# PDNode_Devboard_v0_0_1.net
KiCad netlist of a schematic drawn in EAGLE
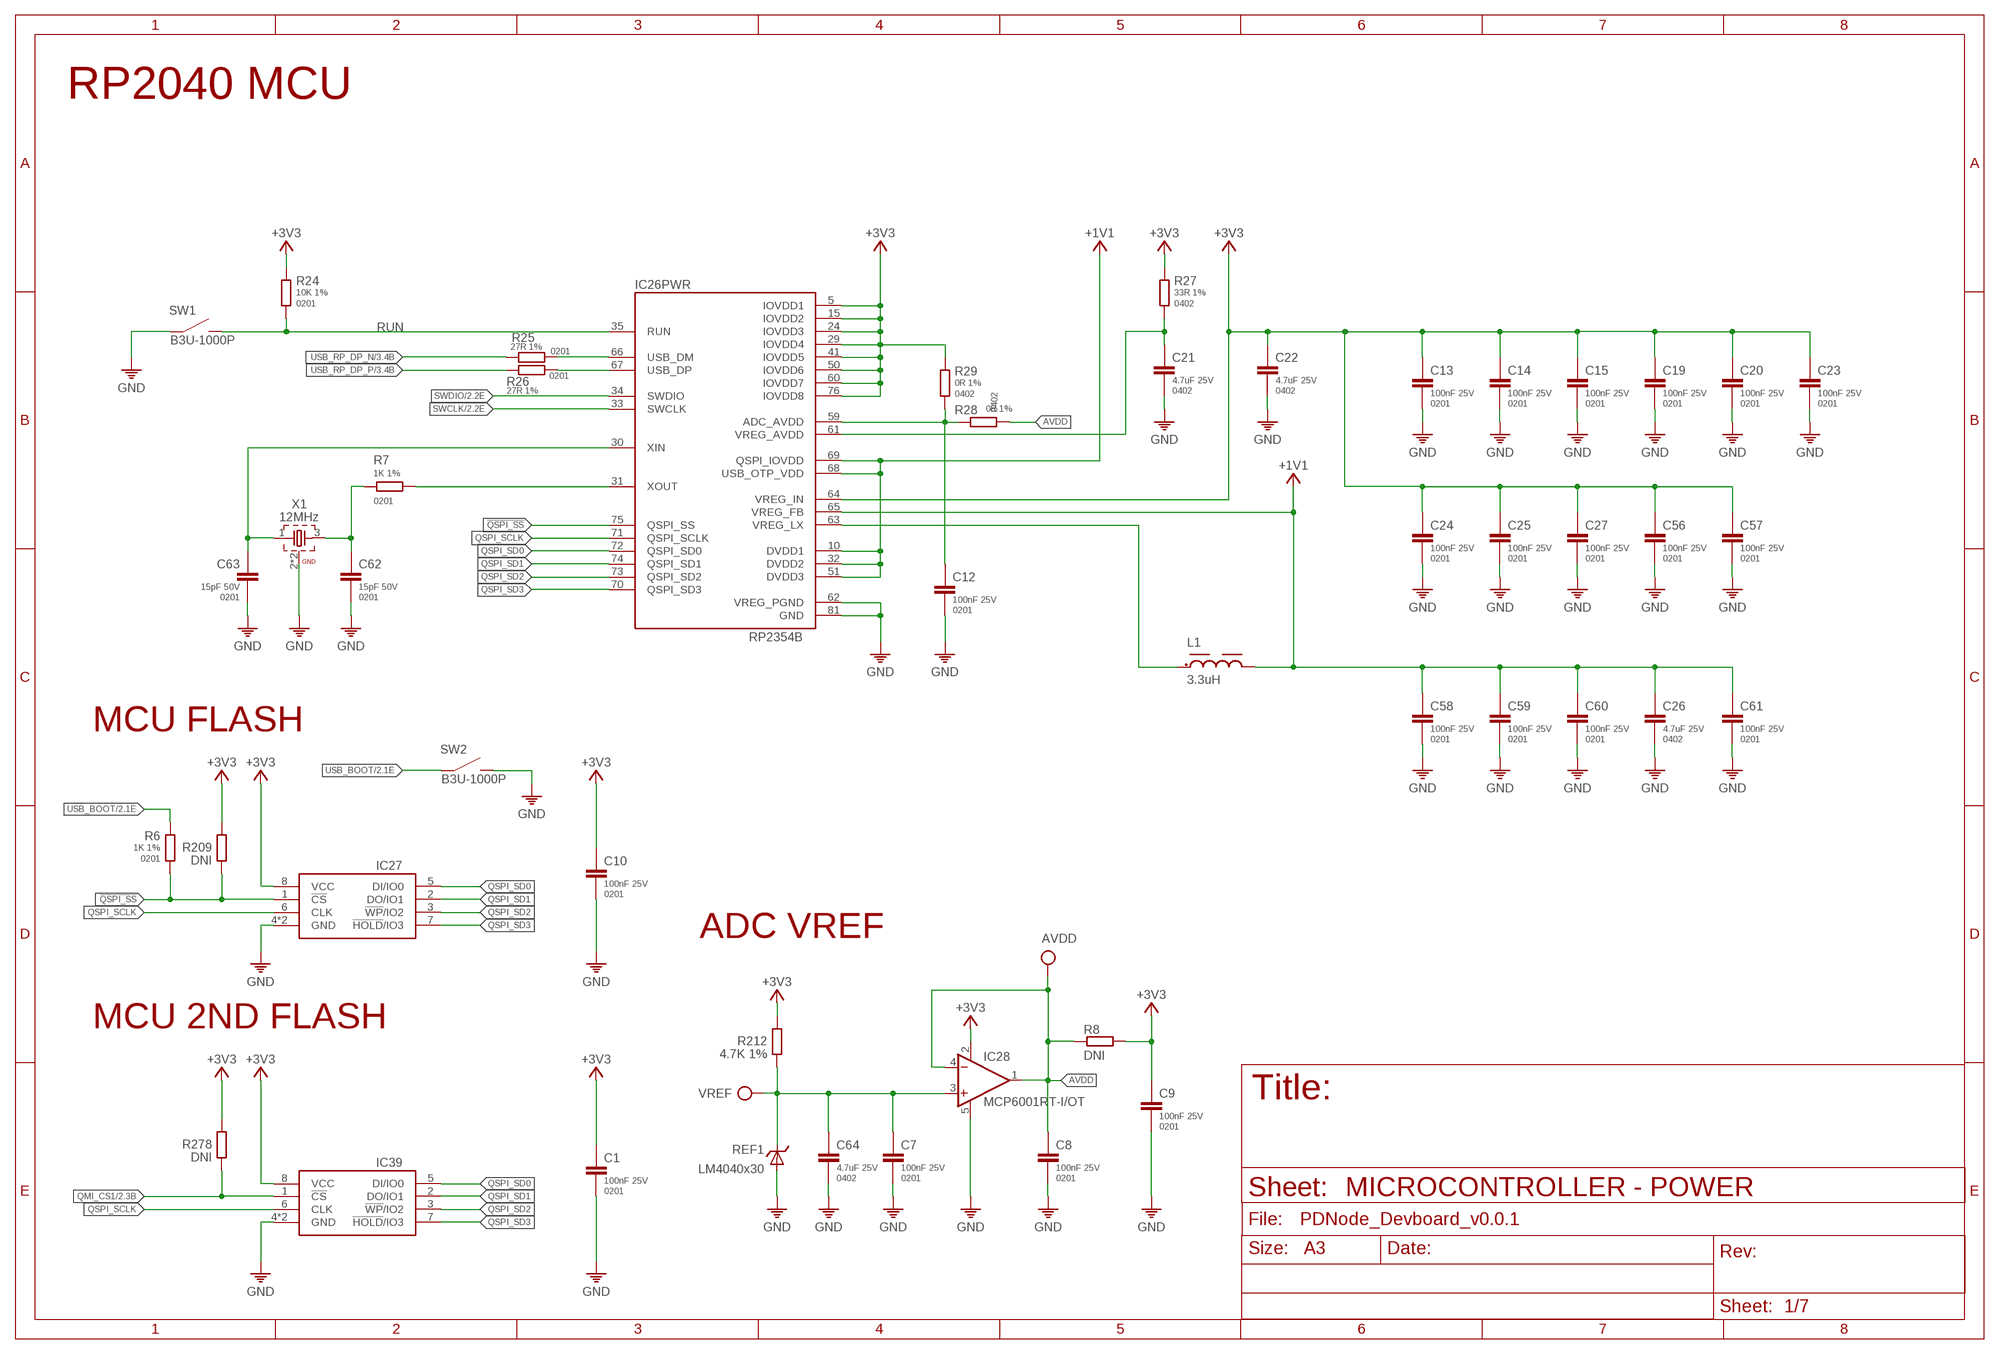
[diagram p0: schematic, sheet 1]
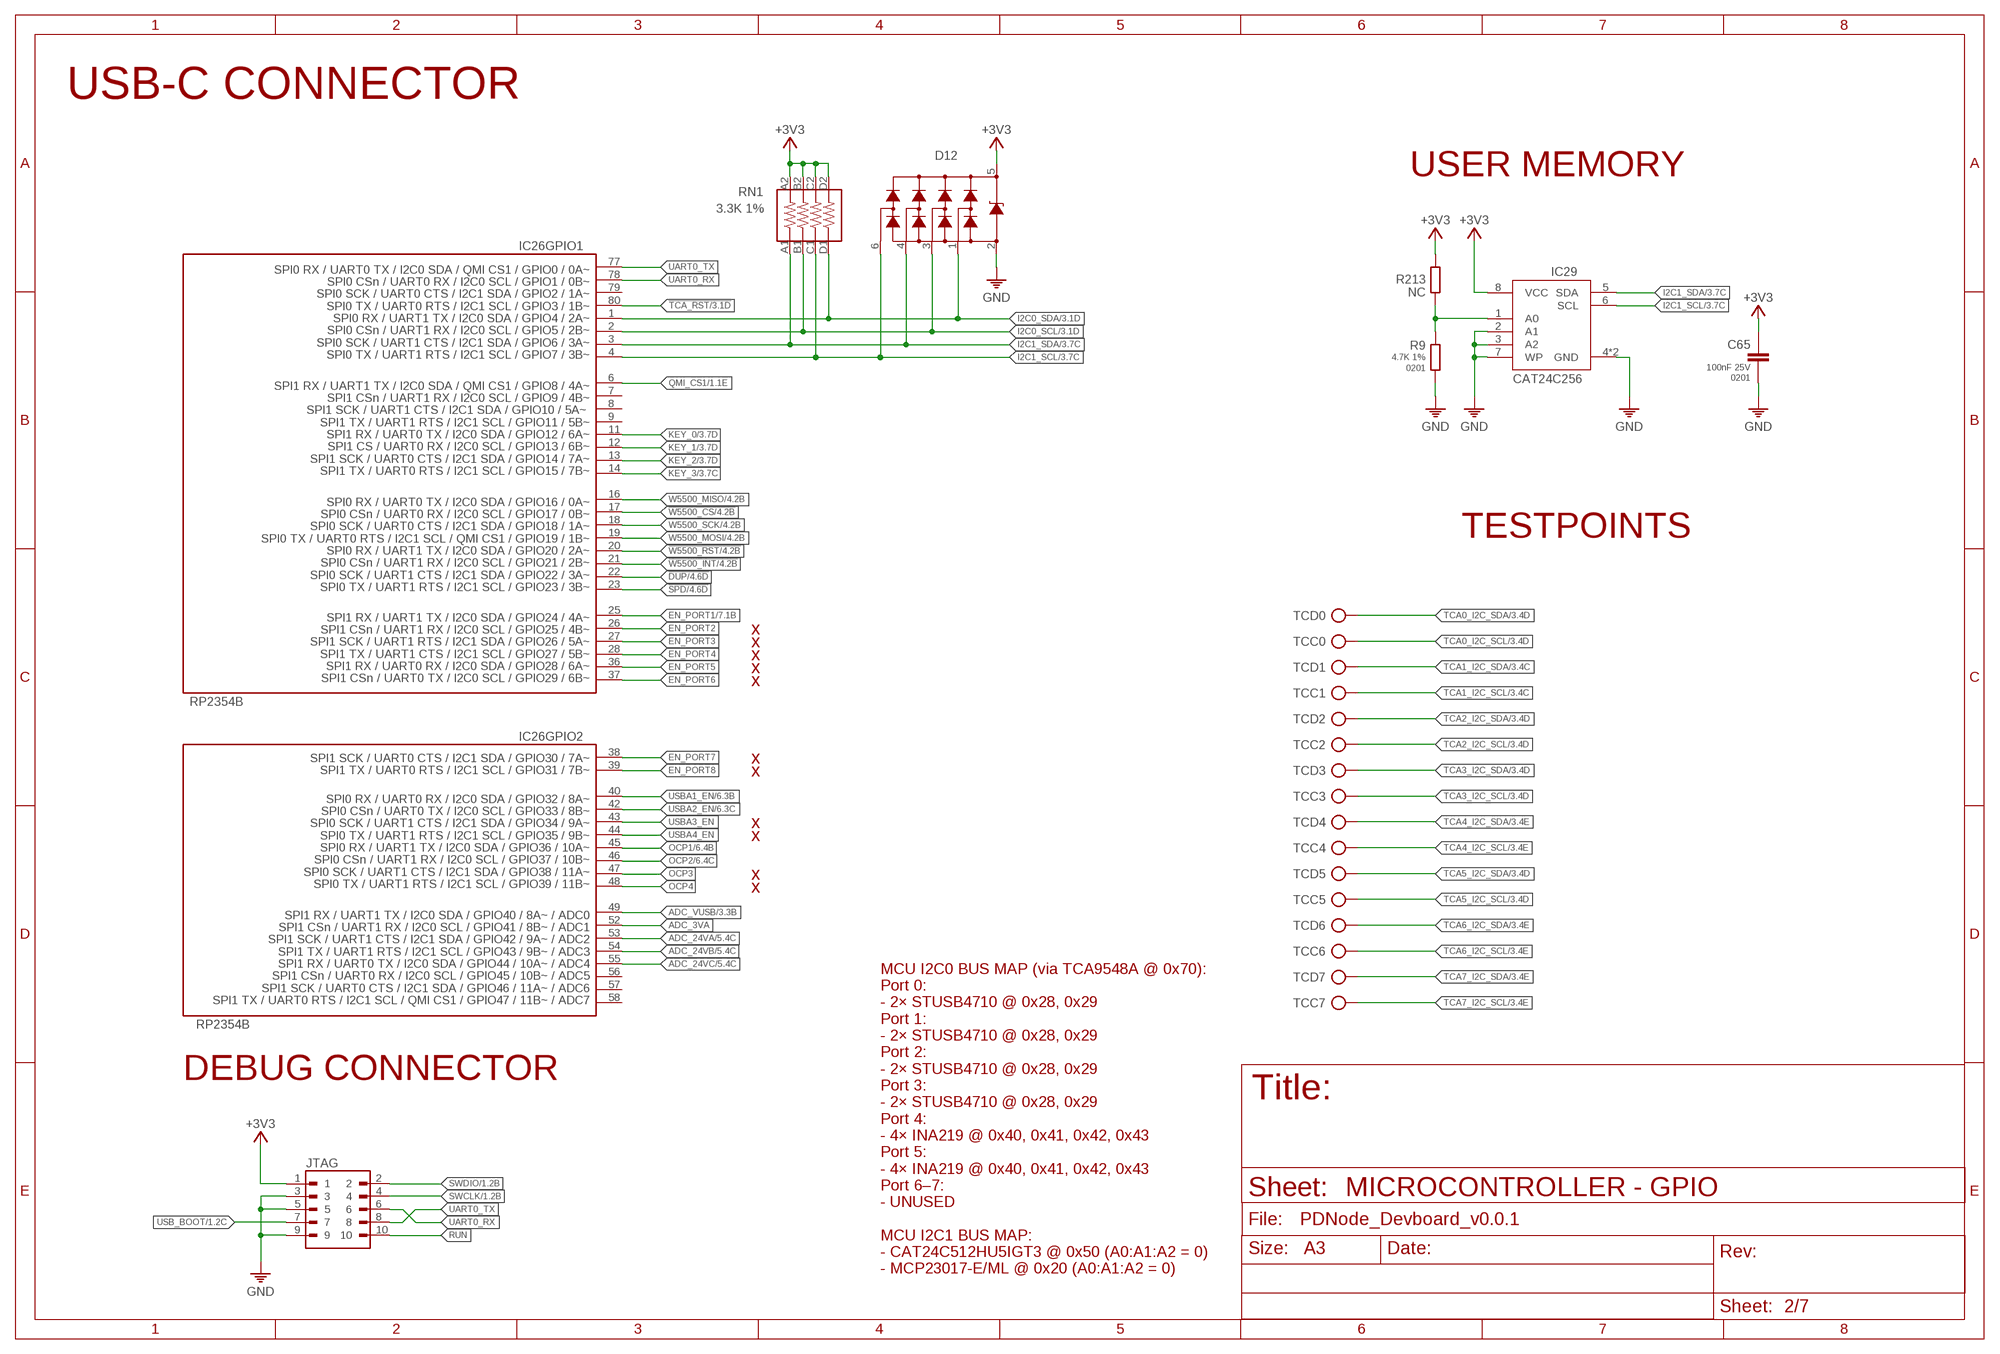
[diagram p1: schematic, sheet 2]
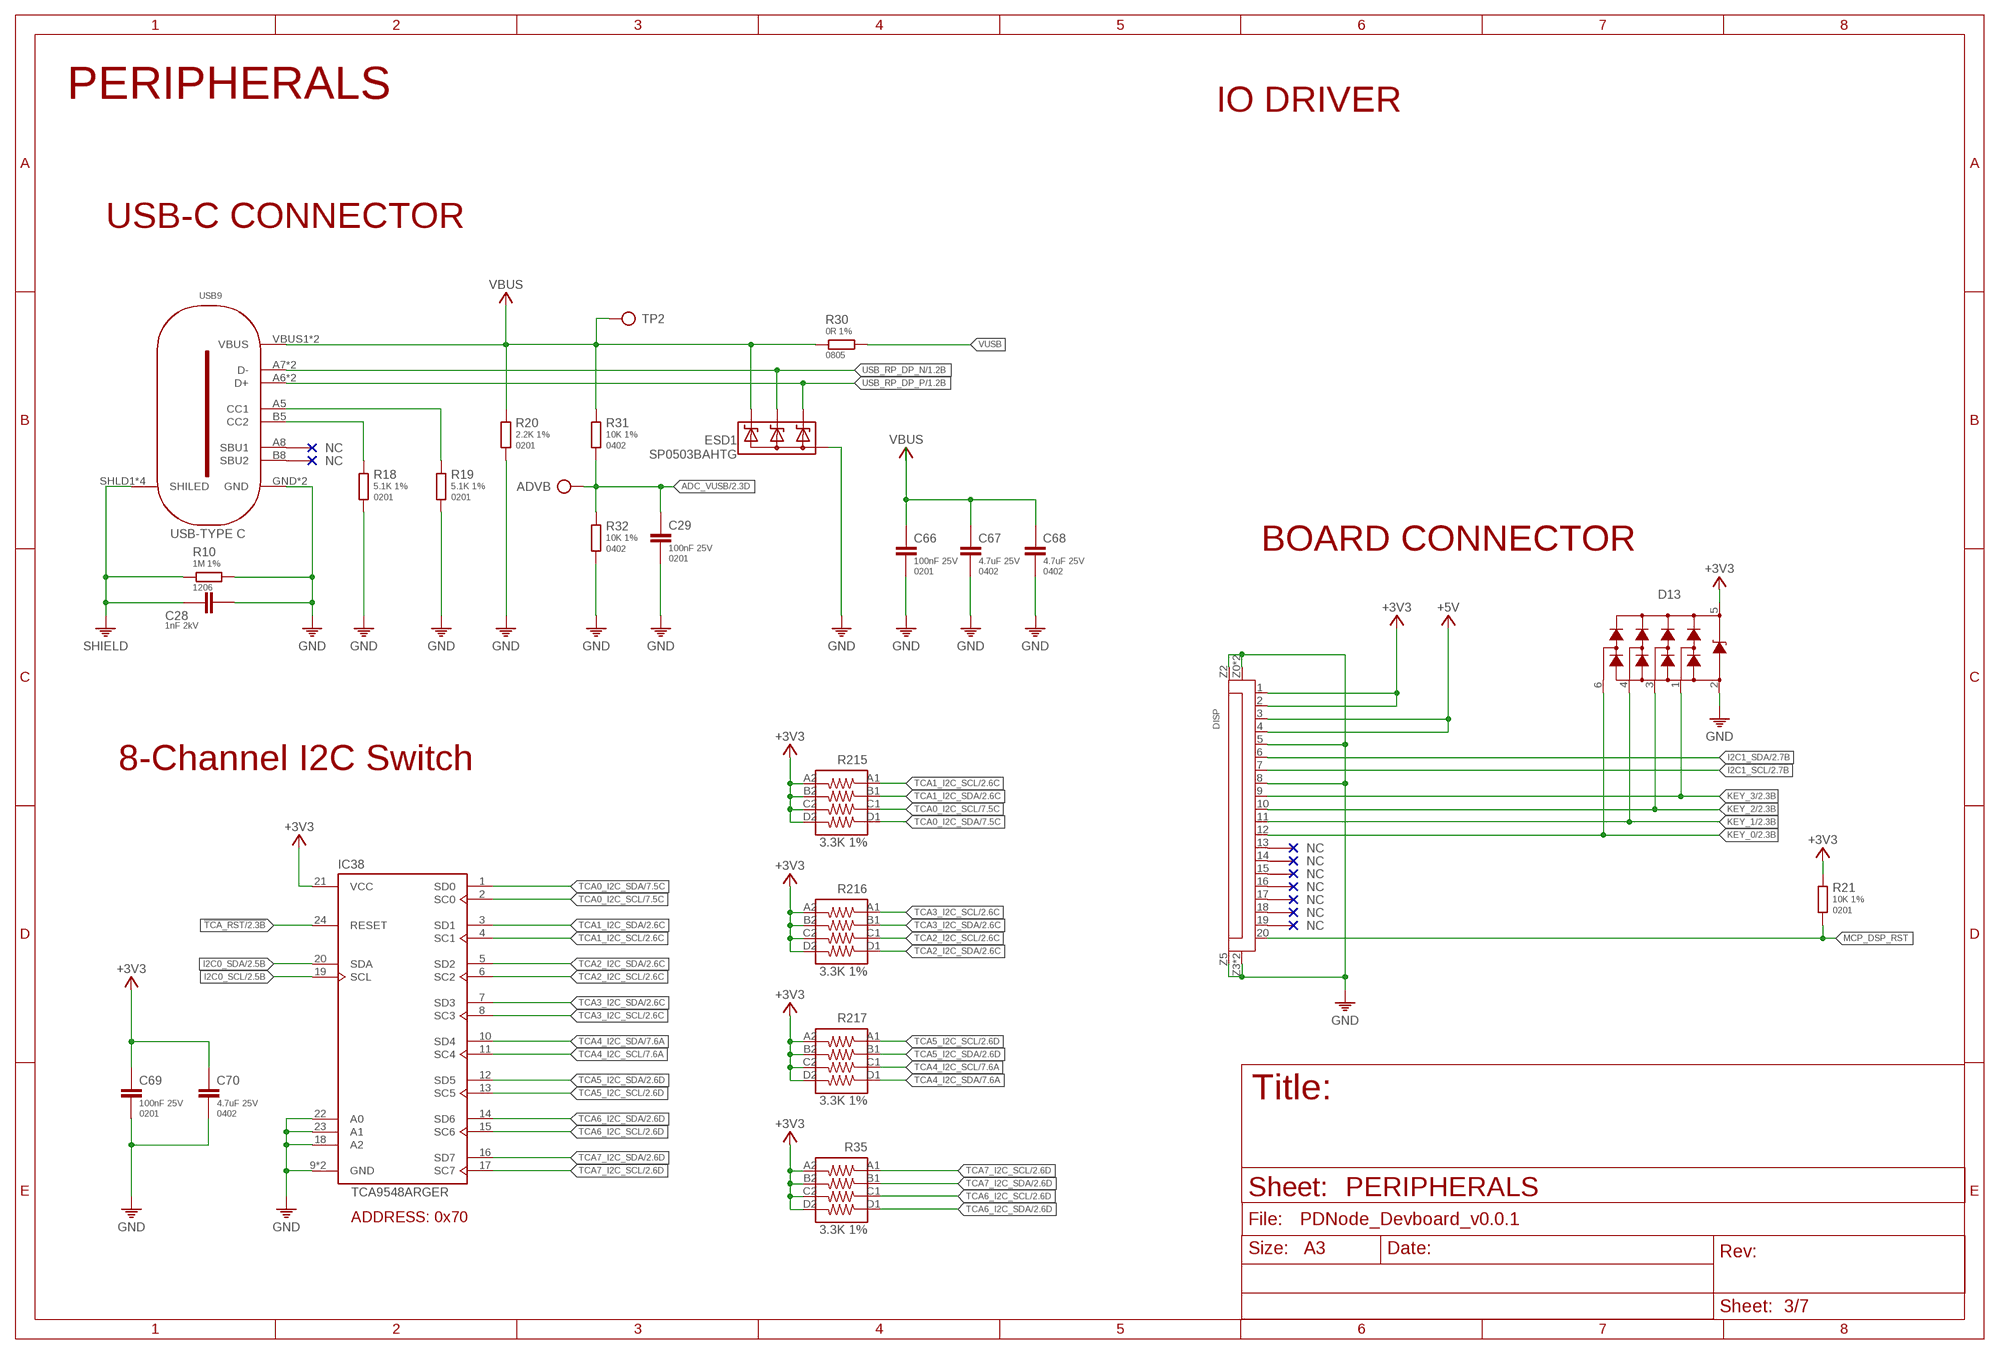
[diagram p2: schematic, sheet 3]
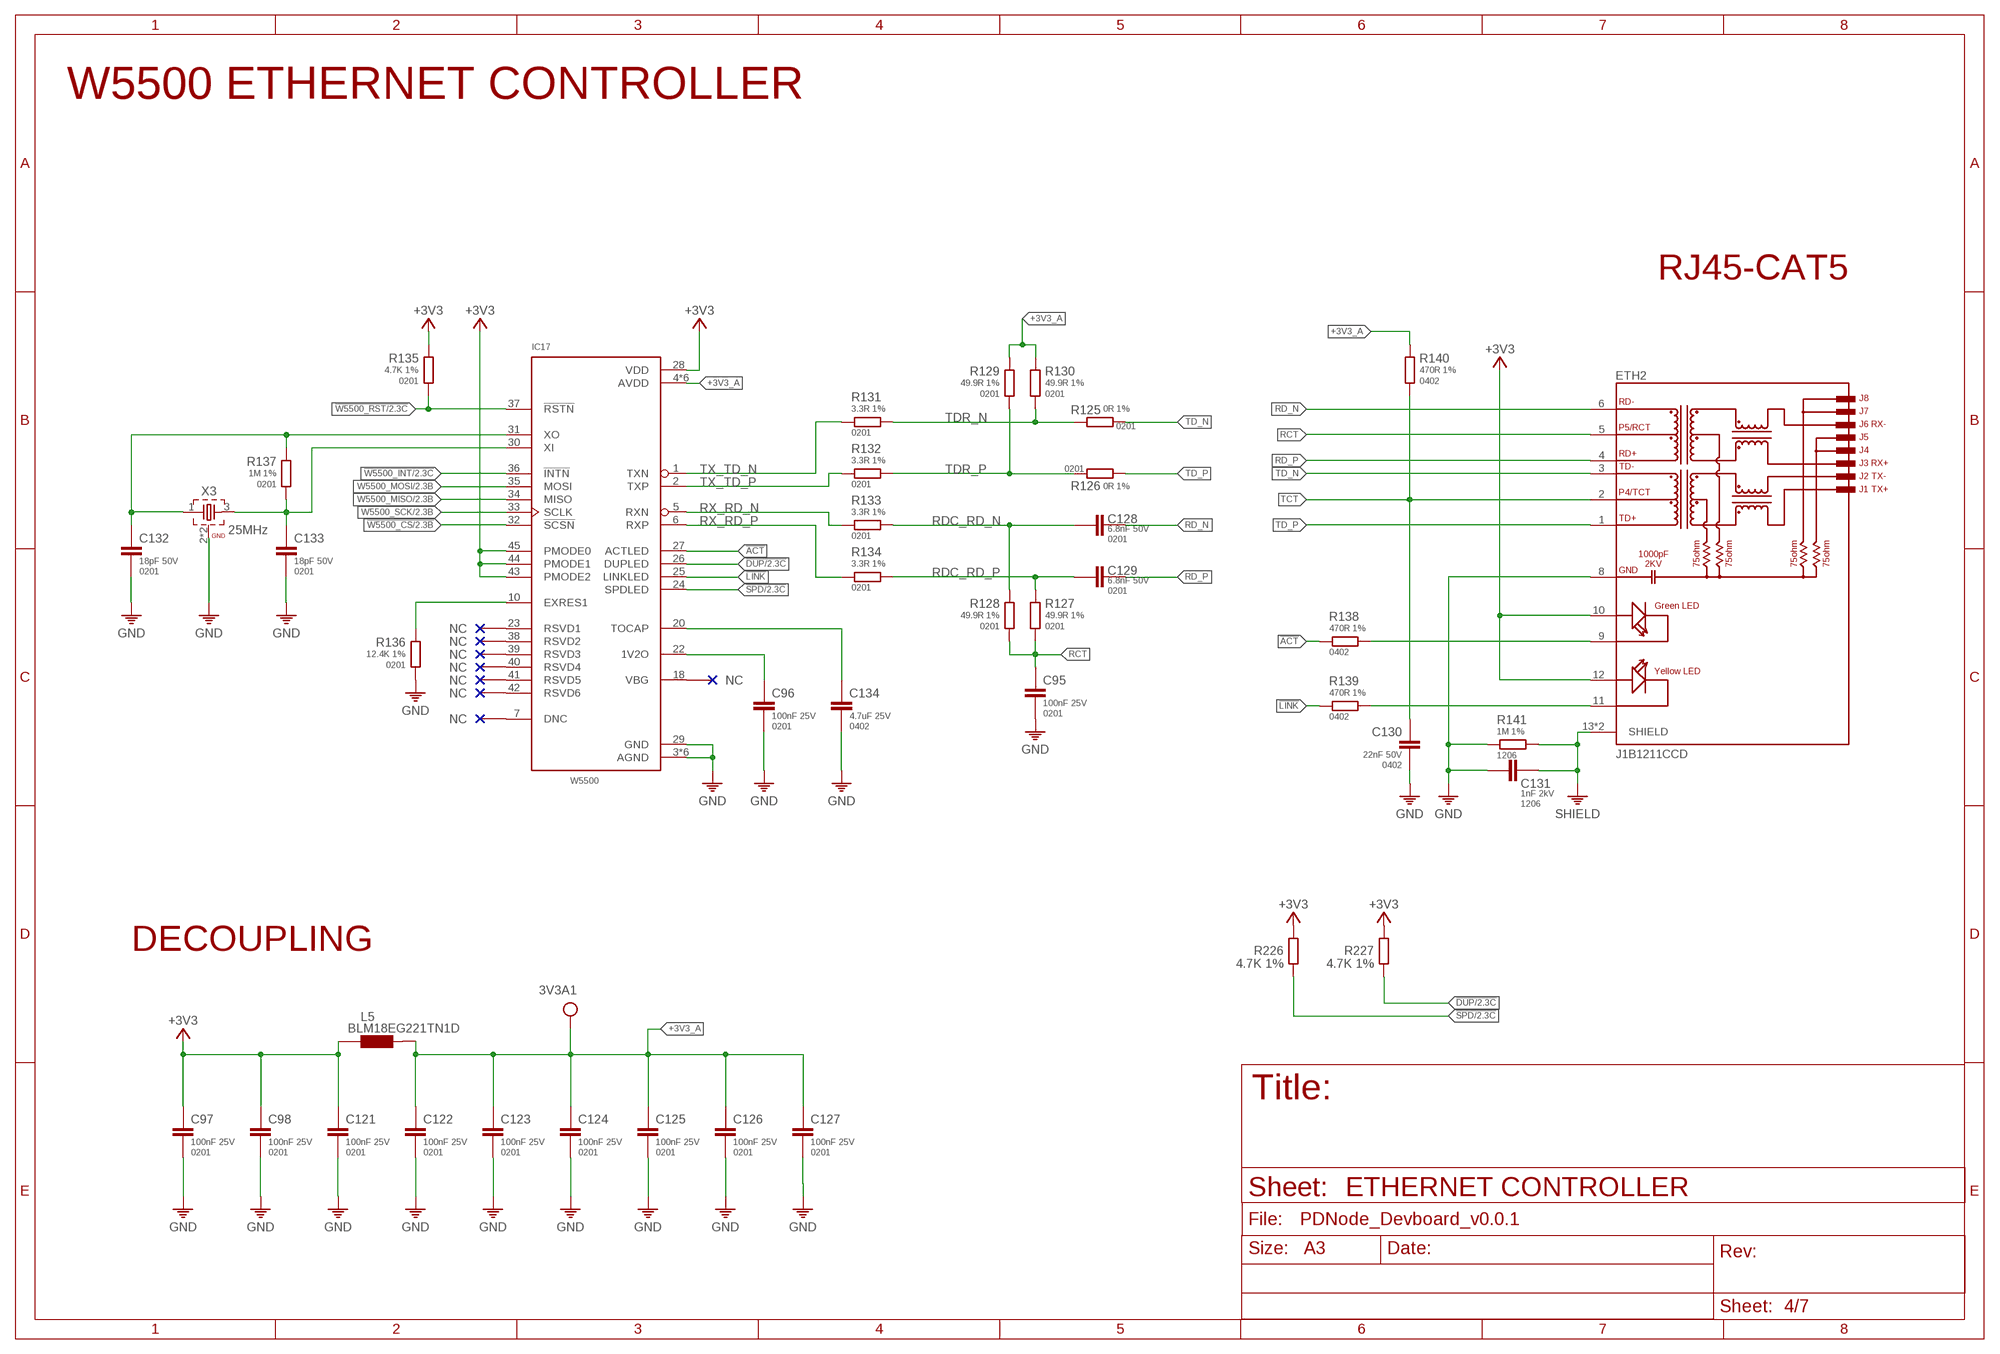
[diagram p3: schematic, sheet 4]
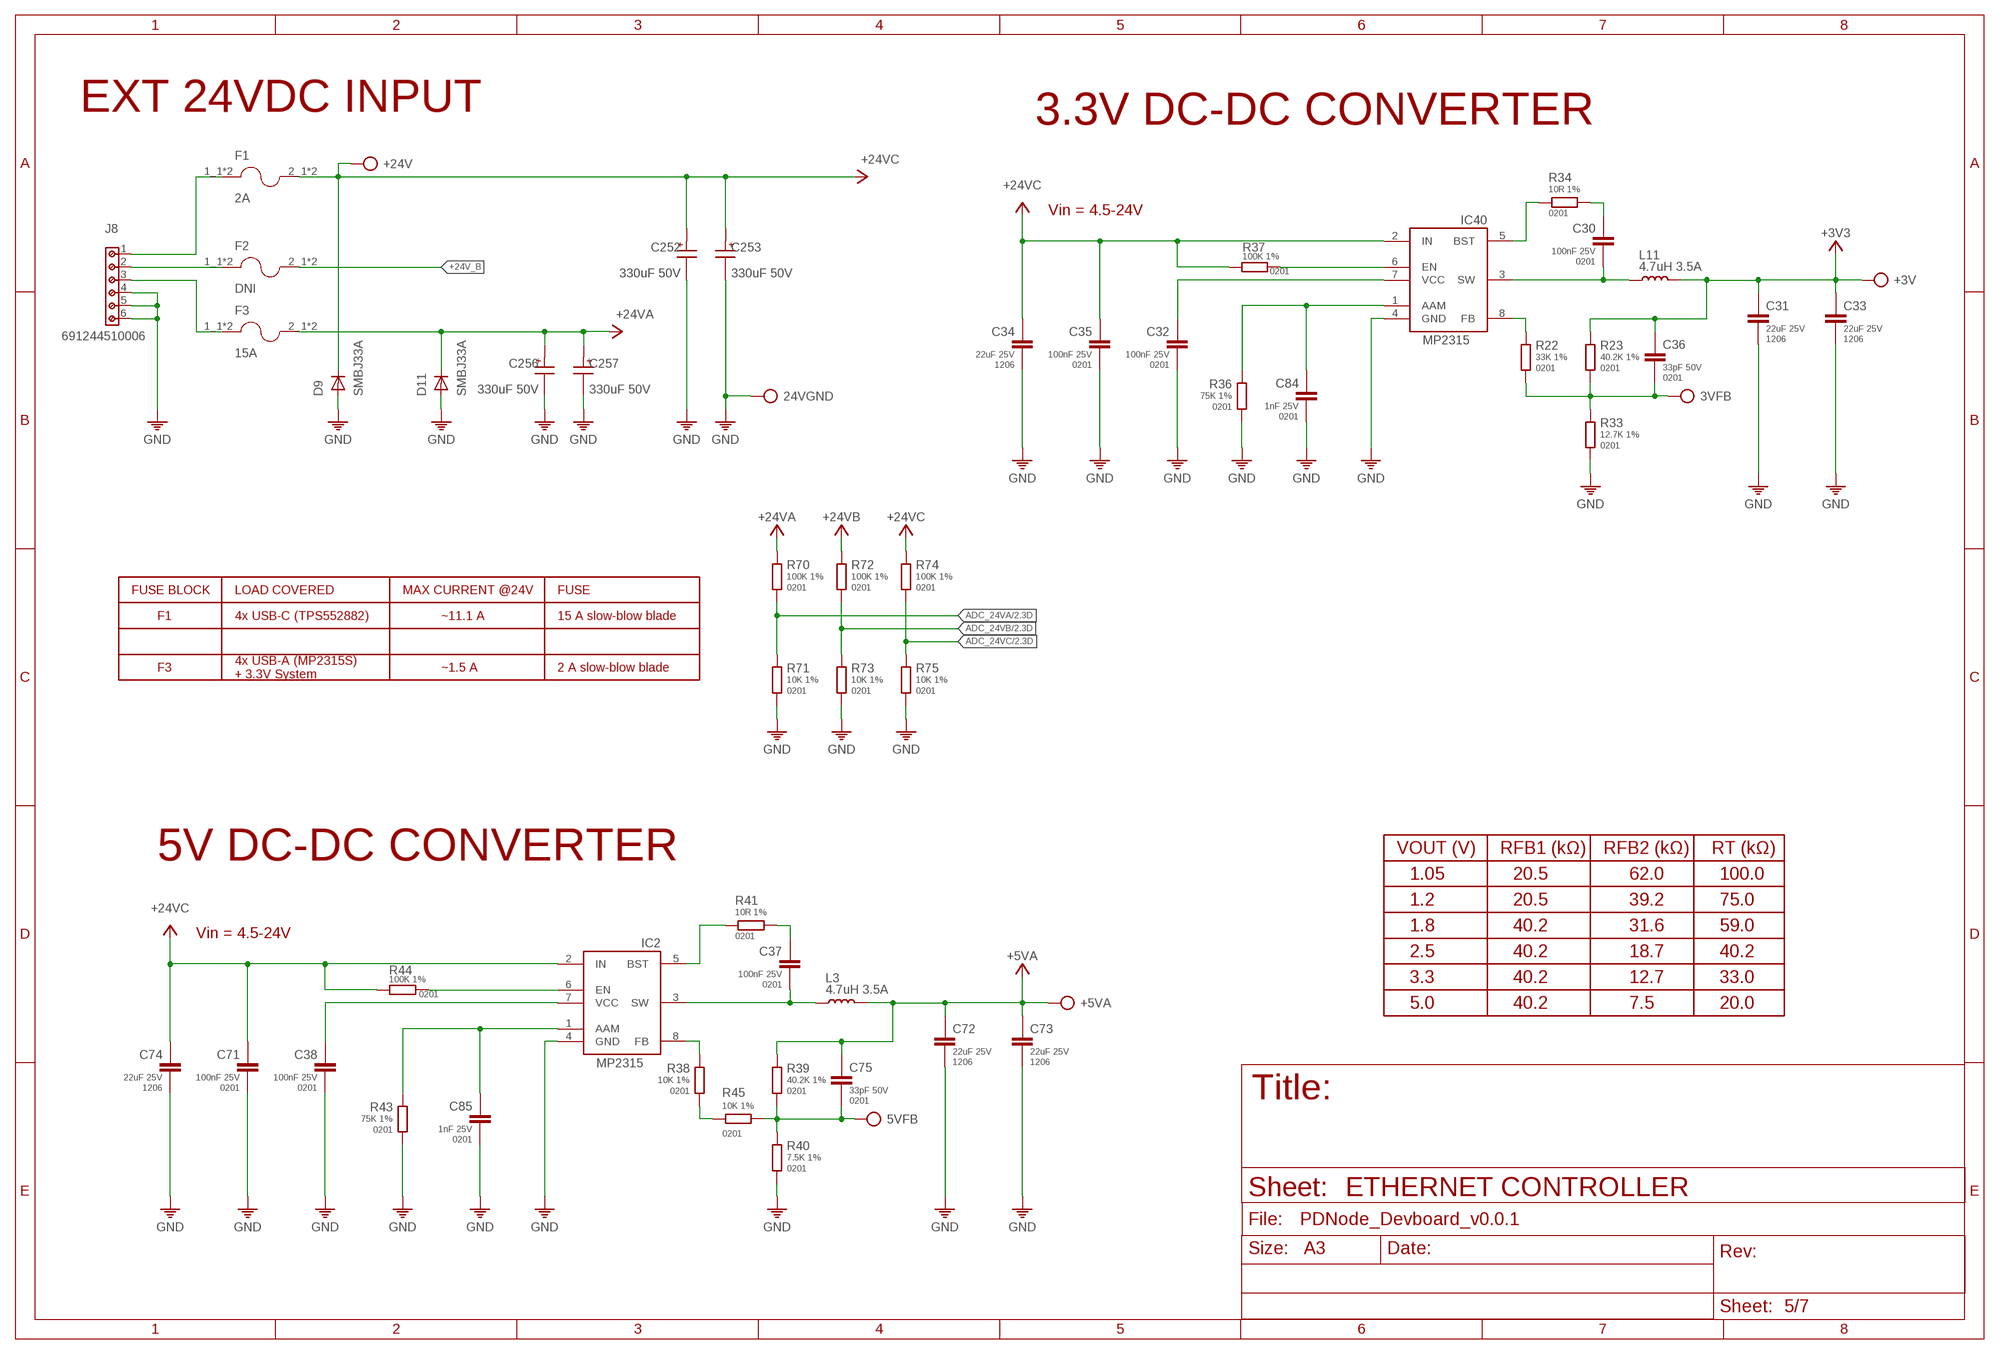
[diagram p4: schematic, sheet 5]
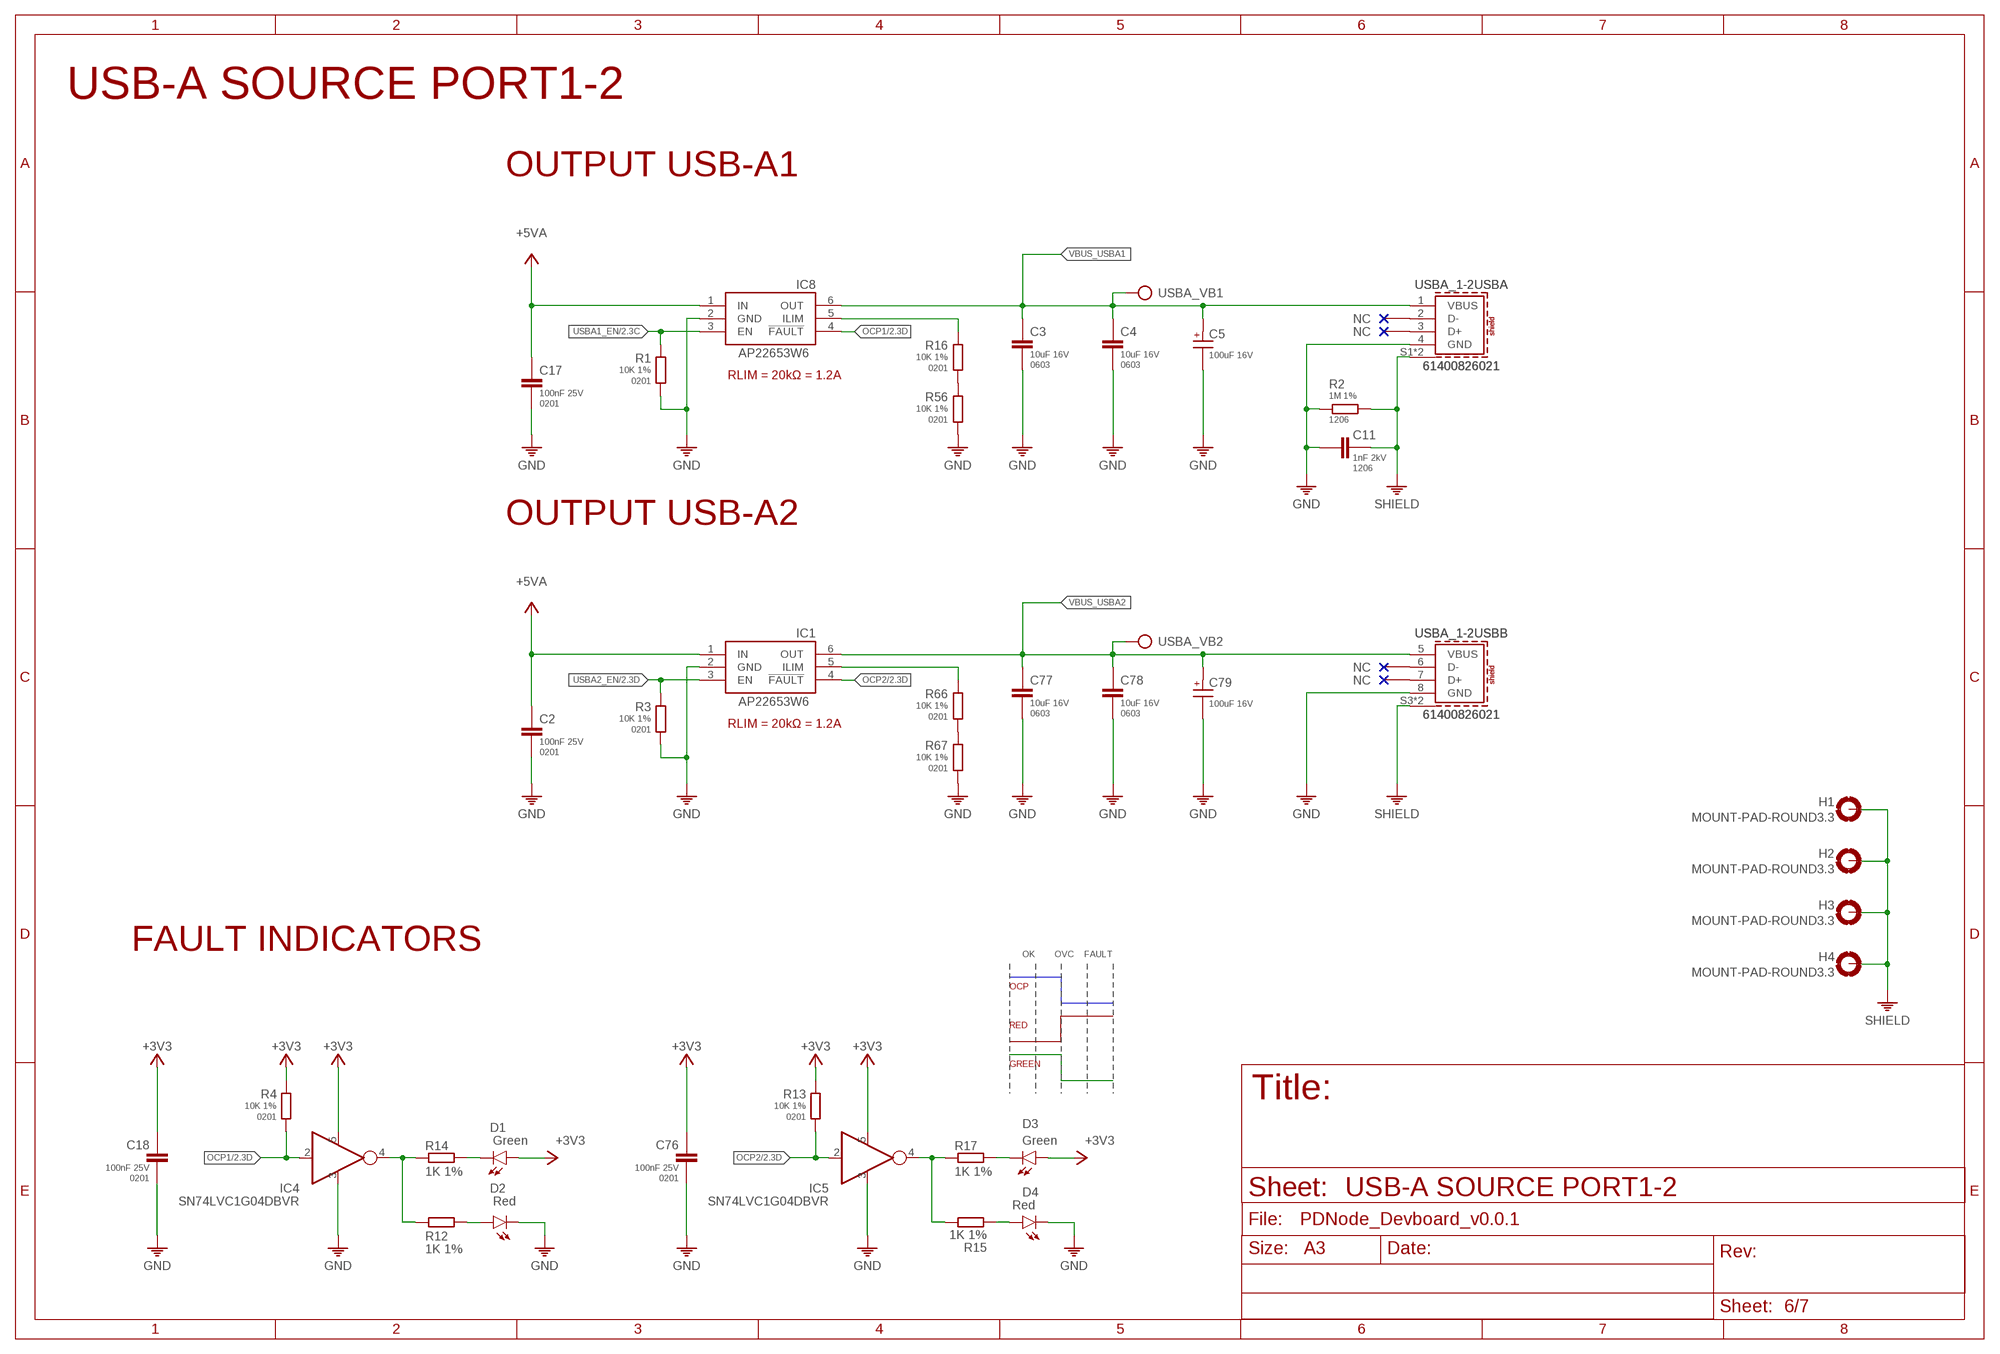
[diagram p5: schematic, sheet 6]
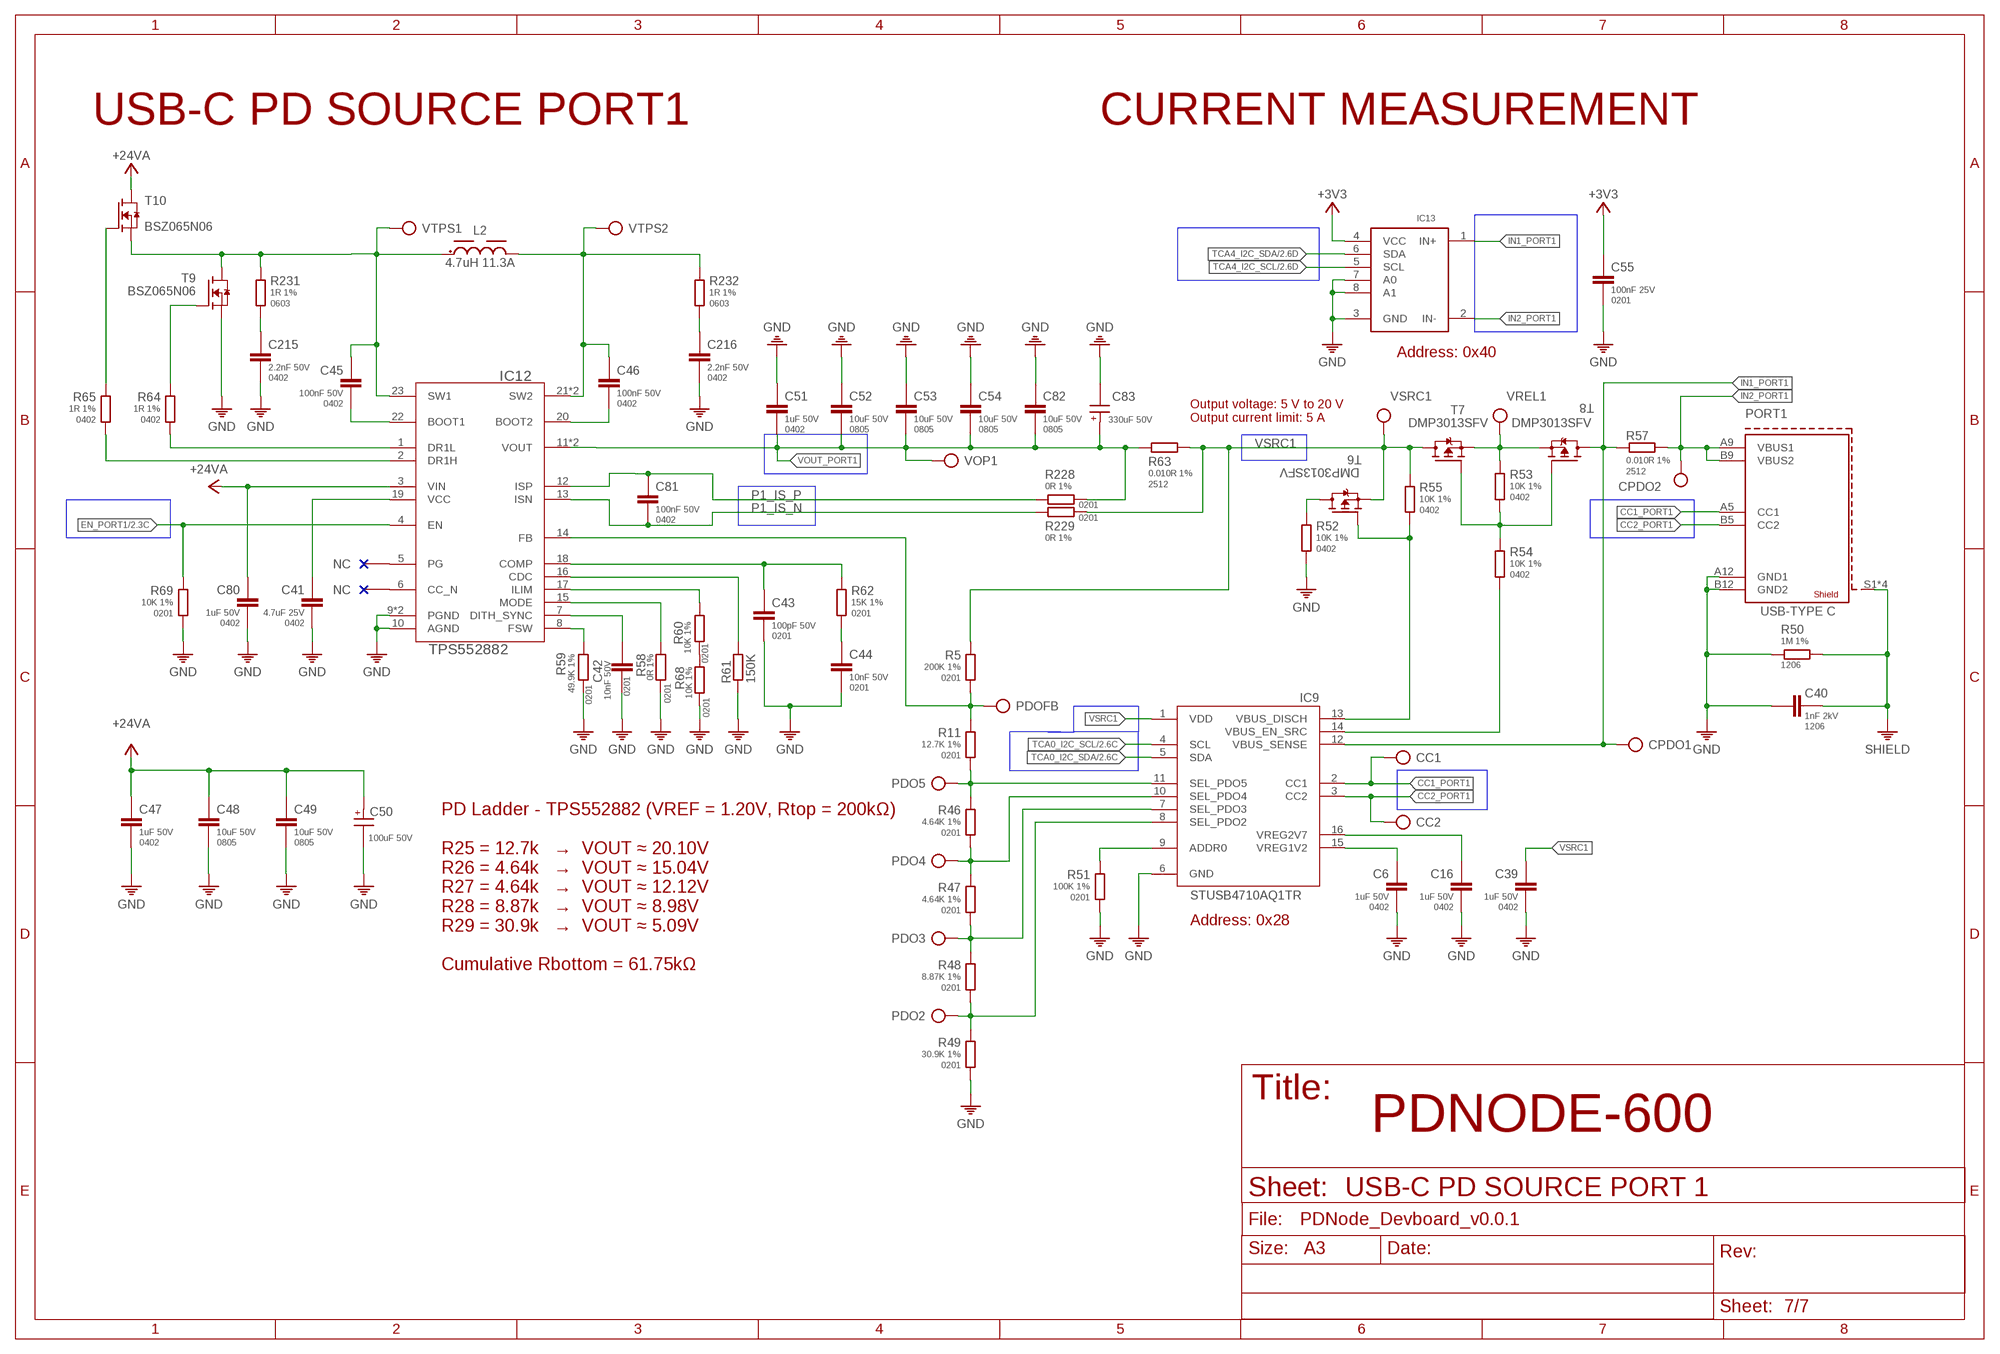
[diagram p6: schematic, sheet 7]

(export (version "E")
  (design (tool "Eeschema 10.0.6"))
  (components
    (comp (ref "C6")
      (value "1uF 50V")
      (footprint "eagle-import:0402")
      (fields (field (name "PACKAGE") "0402") (field (name "LCSC_PART") "C1518208"))
      (libsource (lib "eagle-import") (part "1UF-50V0402"))
    )
    (comp (ref "C16")
      (value "1uF 50V")
      (footprint "eagle-import:0402")
      (fields (field (name "PACKAGE") "0402") (field (name "LCSC_PART") "C1518208"))
      (libsource (lib "eagle-import") (part "1UF-50V0402"))
    )
    (comp (ref "C39")
      (value "1uF 50V")
      (footprint "eagle-import:0402")
      (fields (field (name "PACKAGE") "0402") (field (name "LCSC_PART") "C1518208"))
      (libsource (lib "eagle-import") (part "1UF-50V0402"))
    )
    (comp (ref "C40")
      (value "1nF 2kV")
      (footprint "eagle-import:1206")
      (fields
        (field (name "PACKAGE") "1206")
        (field (name "HQ_PART") "CA0134884")
        (field (name "LCSC_PART") "C173242")
        (field (name "MANUFACTURER") "Johanson Dielectrics ")
      )
      (libsource (lib "eagle-import") (part "1NF-2KV"))
    )
    (comp (ref "C41")
      (value "4.7uF 25V")
      (footprint "eagle-import:0402")
      (fields
        (field (name "PACKAGE") "0402")
        (field (name "HQ_PART") "ZHLM0023346")
        (field (name "LCSC_PART") "C22367824")
        (field (name "MANUFACTURER") "Murata")
      )
      (libsource (lib "eagle-import") (part "4.7UF-25V0402"))
    )
    (comp (ref "C42")
      (value "10nF 50V")
      (footprint "eagle-import:0201")
      (fields (field (name "PACKAGE") "0201") (field (name "LCSC_PART") "C5142551"))
      (libsource (lib "eagle-import") (part "10NF-50V-0201"))
    )
    (comp (ref "C43")
      (value "100pF 50V")
      (footprint "eagle-import:0201")
      (fields
        (field (name "PACKAGE") "0201")
        (field (name "HQ_PART") "CA0177921")
        (field (name "MANUFACTURER") "DARFON")
        (field (name "MPN") "C0603NP0101JGT")
      )
      (libsource (lib "eagle-import") (part "100PF-50V0201"))
    )
    (comp (ref "C44")
      (value "10nF 50V")
      (footprint "eagle-import:0201")
      (fields (field (name "PACKAGE") "0201") (field (name "LCSC_PART") "C5142551"))
      (libsource (lib "eagle-import") (part "10NF-50V-0201"))
    )
    (comp (ref "C45")
      (value "100nF 50V")
      (footprint "eagle-import:0402")
      (fields (field (name "PACKAGE") "0402") (field (name "LCSC_PART") "C307331"))
      (libsource (lib "eagle-import") (part "100NF-50V-0402"))
    )
    (comp (ref "C46")
      (value "100nF 50V")
      (footprint "eagle-import:0402")
      (fields (field (name "PACKAGE") "0402") (field (name "LCSC_PART") "C307331"))
      (libsource (lib "eagle-import") (part "100NF-50V-0402"))
    )
    (comp (ref "C47")
      (value "1uF 50V")
      (footprint "eagle-import:0402")
      (fields (field (name "PACKAGE") "0402") (field (name "LCSC_PART") "C1518208"))
      (libsource (lib "eagle-import") (part "1UF-50V0402"))
    )
    (comp (ref "C48")
      (value "10uF 50V")
      (footprint "eagle-import:0805")
      (fields (field (name "PACKAGE") "0805") (field (name "LCSC_PART") "C440198"))
      (libsource (lib "eagle-import") (part "10UF-50V-0805"))
    )
    (comp (ref "C49")
      (value "10uF 50V")
      (footprint "eagle-import:0805")
      (fields (field (name "PACKAGE") "0805") (field (name "LCSC_PART") "C440198"))
      (libsource (lib "eagle-import") (part "10UF-50V-0805"))
    )
    (comp (ref "C50")
      (value "100uF 50V")
      (footprint "eagle-import:6.3X7.7(DXL)")
      (fields
        (field (name "HQ_PART") "ZHLM0353527")
        (field (name "LCSC_PART") "C3151829")
        (field (name "MANUFACTURER") "ROQANG")
      )
      (libsource (lib "eagle-import") (part "100UF-50V6.3X7.7(DXL)"))
    )
    (comp (ref "C51")
      (value "1uF 50V")
      (footprint "eagle-import:0402")
      (fields (field (name "PACKAGE") "0402") (field (name "LCSC_PART") "C1518208"))
      (libsource (lib "eagle-import") (part "1UF-50V0402"))
    )
    (comp (ref "C52")
      (value "10uF 50V")
      (footprint "eagle-import:0805")
      (fields (field (name "PACKAGE") "0805") (field (name "LCSC_PART") "C440198"))
      (libsource (lib "eagle-import") (part "10UF-50V-0805"))
    )
    (comp (ref "C53")
      (value "10uF 50V")
      (footprint "eagle-import:0805")
      (fields (field (name "PACKAGE") "0805") (field (name "LCSC_PART") "C440198"))
      (libsource (lib "eagle-import") (part "10UF-50V-0805"))
    )
    (comp (ref "C54")
      (value "10uF 50V")
      (footprint "eagle-import:0805")
      (fields (field (name "PACKAGE") "0805") (field (name "LCSC_PART") "C440198"))
      (libsource (lib "eagle-import") (part "10UF-50V-0805"))
    )
    (comp (ref "C55")
      (value "100nF 25V")
      (footprint "eagle-import:0201")
      (fields
        (field (name "PACKAGE") "0201")
        (field (name "HQ_PART") "CA0183221")
        (field (name "LCSC_PART") "C76939")
        (field (name "MANUFACTURER") "Samsung")
      )
      (libsource (lib "eagle-import") (part "100NF-25V-0201"))
    )
    (comp (ref "C80")
      (value "1uF 50V")
      (footprint "eagle-import:0402")
      (fields (field (name "PACKAGE") "0402") (field (name "LCSC_PART") "C1518208"))
      (libsource (lib "eagle-import") (part "1UF-50V0402"))
    )
    (comp (ref "C81")
      (value "100nF 50V")
      (footprint "eagle-import:0402")
      (fields (field (name "PACKAGE") "0402") (field (name "LCSC_PART") "C307331"))
      (libsource (lib "eagle-import") (part "100NF-50V-0402"))
    )
    (comp (ref "C82")
      (value "10uF 50V")
      (footprint "eagle-import:0805")
      (fields (field (name "PACKAGE") "0805") (field (name "LCSC_PART") "C440198"))
      (libsource (lib "eagle-import") (part "10UF-50V-0805"))
    )
    (comp (ref "C83")
      (value "330uF 50V")
      (footprint "eagle-import:10X10.5(DXL)")
      (fields (field (name "LCSC_PART") "C2895745") (field (name "MPN") "EEE-FT1H331AP"))
      (libsource (lib "eagle-import") (part "330UF-50V10X10.5(DXL)"))
    )
    (comp (ref "C215")
      (value "2.2nF 50V")
      (footprint "eagle-import:0402")
      (fields
        (field (name "PACKAGE") "0402")
        (field (name "HQ_PART") "CA0176616")
        (field (name "MANUFACTURER") "WALSIN")
        (field (name "MPN") "0402B222K500CT")
      )
      (libsource (lib "eagle-import") (part "2.2NF-50V-0402"))
    )
    (comp (ref "C216")
      (value "2.2nF 50V")
      (footprint "eagle-import:0402")
      (fields
        (field (name "PACKAGE") "0402")
        (field (name "HQ_PART") "CA0176616")
        (field (name "MANUFACTURER") "WALSIN")
        (field (name "MPN") "0402B222K500CT")
      )
      (libsource (lib "eagle-import") (part "2.2NF-50V-0402"))
    )
    (comp (ref "CC1")
      (value "DNI")
      (footprint "eagle-import:TP-ROUND")
      (libsource (lib "eagle-import") (part "TP-ROUND"))
    )
    (comp (ref "CC2")
      (value "DNI")
      (footprint "eagle-import:TP-ROUND")
      (libsource (lib "eagle-import") (part "TP-ROUND"))
    )
    (comp (ref "CPDO1")
      (value "DNI")
      (footprint "eagle-import:TP-ROUND")
      (libsource (lib "eagle-import") (part "TP-ROUND"))
    )
    (comp (ref "CPDO2")
      (value "DNI")
      (footprint "eagle-import:TP-ROUND")
      (libsource (lib "eagle-import") (part "TP-ROUND"))
    )
    (comp (ref "IC9")
      (value "STUSB4710AQ1TR")
      (footprint "eagle-import:QFN50P300X300X55-16N")
      (libsource (lib "eagle-import") (part "STUSB4710AQ1TR"))
    )
    (comp (ref "IC12")
      (value "TPS552882")
      (footprint "eagle-import:RPM0026A-MFG")
      (fields
        (field (name "MANUFACTURER_PART_NUMBER") "TPS552882QRPMRQ1")
        (field (name "COPYRIGHT") "Copyright (C) 2025 Ultra Librarian. All rights reserved.")
      )
      (libsource (lib "eagle-import") (part "TPS552882"))
    )
    (comp (ref "IC13")
      (value "INA219BIDCNT")
      (footprint "eagle-import:SOT23-8")
      (fields
        (field (name "HQ_PART") "IC0063216")
        (field (name "LCSC_PART") "C2653868")
        (field (name "MANUFACTURER") "Texas Instruments")
      )
      (libsource (lib "eagle-import") (part "INA219BIDCNT"))
    )
    (comp (ref "L2")
      (value "4.7uH 11.3A")
      (footprint "eagle-import:WE-PDHV_1280")
      (fields
        (field (name "LCSC_PART") "C2998768")
        (field (name "MANUFACTURER") "Sumida")
        (field (name "MPN") "CDRH127NP-4R7NC")
      )
      (libsource (lib "eagle-import") (part "4.7UH-PWR"))
    )
    (comp (ref "PDO2")
      (value "DNI")
      (footprint "eagle-import:TP-ROUND")
      (libsource (lib "eagle-import") (part "TP-ROUND"))
    )
    (comp (ref "PDO3")
      (value "DNI")
      (footprint "eagle-import:TP-ROUND")
      (libsource (lib "eagle-import") (part "TP-ROUND"))
    )
    (comp (ref "PDO4")
      (value "DNI")
      (footprint "eagle-import:TP-ROUND")
      (libsource (lib "eagle-import") (part "TP-ROUND"))
    )
    (comp (ref "PDO5")
      (value "DNI")
      (footprint "eagle-import:TP-ROUND")
      (libsource (lib "eagle-import") (part "TP-ROUND"))
    )
    (comp (ref "PDOFB")
      (value "DNI")
      (footprint "eagle-import:TP-ROUND")
      (libsource (lib "eagle-import") (part "TP-ROUND"))
    )
    (comp (ref "PORT1")
      (value "632722100213")
      (footprint "eagle-import:632722100213")
      (fields
        (field (name "LCSC_PART") "C2927029")
        (field (name "MANUFACTURER") "DEALON")
        (field (name "MPN") "USB-TYPE-C-009 ")
      )
      (libsource (lib "eagle-import") (part "USB-C-POWERONLY"))
    )
    (comp (ref "R5")
      (value "200K 1%")
      (footprint "eagle-import:0201")
      (fields (field (name "PACKAGE") "0201") (field (name "LCSC_PART") "C270357"))
      (libsource (lib "eagle-import") (part "200K-1%0201"))
    )
    (comp (ref "R11")
      (value "12.7K 1%")
      (footprint "eagle-import:0201")
      (fields
        (field (name "PACKAGE") "0201")
        (field (name "LCSC_PART") "C423755")
        (field (name "MANUFACTURER") "UNI-ROYAL")
        (field (name "MPN") "0201WMF1272TEE")
      )
      (libsource (lib "eagle-import") (part "12.7K-1%0201"))
    )
    (comp (ref "R46")
      (value "4.64K 1%")
      (footprint "eagle-import:0201")
      (fields
        (field (name "PACKAGE") "0201")
        (field (name "LCSC_PART") "C166186")
        (field (name "MANUFACTURER") " RALEC")
        (field (name "MPN") "RTT014641FTH")
      )
      (libsource (lib "eagle-import") (part "4.64K-1%-0201"))
    )
    (comp (ref "R47")
      (value "4.64K 1%")
      (footprint "eagle-import:0201")
      (fields
        (field (name "PACKAGE") "0201")
        (field (name "LCSC_PART") "C166186")
        (field (name "MANUFACTURER") " RALEC")
        (field (name "MPN") "RTT014641FTH")
      )
      (libsource (lib "eagle-import") (part "4.64K-1%-0201"))
    )
    (comp (ref "R48")
      (value "8.87K 1%")
      (footprint "eagle-import:0201")
      (fields
        (field (name "PACKAGE") "0201")
        (field (name "LCSC_PART") "C423413")
        (field (name "MANUFACTURER") " UNI-ROYAL")
        (field (name "MPN") "0201WMF8871TEE")
      )
      (libsource (lib "eagle-import") (part "8.87K-1%-0201"))
    )
    (comp (ref "R49")
      (value "30.9K 1%")
      (footprint "eagle-import:0201")
      (fields (field (name "PACKAGE") "0201") (field (name "LCSC_PART") "C364366"))
      (libsource (lib "eagle-import") (part "30.9K-1%0201"))
    )
    (comp (ref "R50")
      (value "1M 1%")
      (footprint "eagle-import:1206")
      (fields
        (field (name "PACKAGE") "1206")
        (field (name "HQ_PART") "RE0188103")
        (field (name "LCSC_PART") "C17927")
        (field (name "MANUFACTURER") "Uniohm")
      )
      (libsource (lib "eagle-import") (part "1M-1%1206"))
    )
    (comp (ref "R51")
      (value "100K 1%")
      (footprint "eagle-import:0201")
      (fields (field (name "PACKAGE") "0201") (field (name "LCSC_PART") "C270364"))
      (libsource (lib "eagle-import") (part "100K-1%0201"))
    )
    (comp (ref "R52")
      (value "10K 1%")
      (footprint "eagle-import:0402")
      (fields
        (field (name "PACKAGE") "0402")
        (field (name "HQ_PART") "RE0207399")
        (field (name "LCSC_PART") "C25744")
        (field (name "MANUFACTURER") "ROHM")
      )
      (libsource (lib "eagle-import") (part "10K-1%0402"))
    )
    (comp (ref "R53")
      (value "10K 1%")
      (footprint "eagle-import:0402")
      (fields
        (field (name "PACKAGE") "0402")
        (field (name "HQ_PART") "RE0207399")
        (field (name "LCSC_PART") "C25744")
        (field (name "MANUFACTURER") "ROHM")
      )
      (libsource (lib "eagle-import") (part "10K-1%0402"))
    )
    (comp (ref "R54")
      (value "10K 1%")
      (footprint "eagle-import:0402")
      (fields
        (field (name "PACKAGE") "0402")
        (field (name "HQ_PART") "RE0207399")
        (field (name "LCSC_PART") "C25744")
        (field (name "MANUFACTURER") "ROHM")
      )
      (libsource (lib "eagle-import") (part "10K-1%0402"))
    )
    (comp (ref "R55")
      (value "10K 1%")
      (footprint "eagle-import:0402")
      (fields
        (field (name "PACKAGE") "0402")
        (field (name "HQ_PART") "RE0207399")
        (field (name "LCSC_PART") "C25744")
        (field (name "MANUFACTURER") "ROHM")
      )
      (libsource (lib "eagle-import") (part "10K-1%0402"))
    )
    (comp (ref "R57")
      (value "0.010R 1%")
      (footprint "eagle-import:2512")
      (fields
        (field (name "PACKAGE") "2512")
        (field (name "LCSC_PART") "C127692")
        (field (name "MANUFACTURER") " UNI-ROYAL")
        (field (name "MPN") "25121WF100MT4E")
      )
      (libsource (lib "eagle-import") (part "0.010R-1%-2512"))
    )
    (comp (ref "R58")
      (value "0R 1%")
      (footprint "eagle-import:0201")
      (fields
        (field (name "PACKAGE") "0201")
        (field (name "HA_PART") "RE0015349")
        (field (name "LCSC_PART") "C106227")
        (field (name "MANUFACTURER") "Yageo")
      )
      (libsource (lib "eagle-import") (part "0R0201"))
    )
    (comp (ref "R59")
      (value "49.9K 1%")
      (footprint "eagle-import:0201")
      (fields
        (field (name "PACKAGE") "0201")
        (field (name "HQ_PART") "RE0461584")
        (field (name "LCSC_PART") "C138136")
        (field (name "MANUFACTURER") "Yageo")
      )
      (libsource (lib "eagle-import") (part "49.9K-1%0201"))
    )
    (comp (ref "R60")
      (value "10K 1%")
      (footprint "eagle-import:0201")
      (fields
        (field (name "PACKAGE") "0201")
        (field (name "HQ_PART") "RE0208620")
        (field (name "LCSC_PART") "C473048")
        (field (name "MANUFACTURER") "FH")
      )
      (libsource (lib "eagle-import") (part "10K-1%0201"))
    )
    (comp (ref "R61")
      (value "150K")
      (footprint "eagle-import:R0201")
      (libsource (lib "eagle-import") (part "R0201"))
    )
    (comp (ref "R62")
      (value "15K 1%")
      (footprint "eagle-import:0201")
      (fields (field (name "PACKAGE") "0201") (field (name "LCSC_PART") "C295774"))
      (libsource (lib "eagle-import") (part "15K-1%0201"))
    )
    (comp (ref "R63")
      (value "0.010R 1%")
      (footprint "eagle-import:2512")
      (fields
        (field (name "PACKAGE") "2512")
        (field (name "LCSC_PART") "C127692")
        (field (name "MANUFACTURER") " UNI-ROYAL")
        (field (name "MPN") "25121WF100MT4E")
      )
      (libsource (lib "eagle-import") (part "0.010R-1%-2512"))
    )
    (comp (ref "R64")
      (value "1R 1%")
      (footprint "eagle-import:0402")
      (fields
        (field (name "PACKAGE") "0402")
        (field (name "HQ_PART") "RE0322446")
        (field (name "MANUFACTURER") "RALEC")
        (field (name "MPN") "RTT021R00FTH")
      )
      (libsource (lib "eagle-import") (part "1R-1%0402"))
    )
    (comp (ref "R65")
      (value "1R 1%")
      (footprint "eagle-import:0402")
      (fields
        (field (name "PACKAGE") "0402")
        (field (name "HQ_PART") "RE0322446")
        (field (name "MANUFACTURER") "RALEC")
        (field (name "MPN") "RTT021R00FTH")
      )
      (libsource (lib "eagle-import") (part "1R-1%0402"))
    )
    (comp (ref "R68")
      (value "10K 1%")
      (footprint "eagle-import:0201")
      (fields
        (field (name "PACKAGE") "0201")
        (field (name "HQ_PART") "RE0208620")
        (field (name "LCSC_PART") "C473048")
        (field (name "MANUFACTURER") "FH")
      )
      (libsource (lib "eagle-import") (part "10K-1%0201"))
    )
    (comp (ref "R69")
      (value "10K 1%")
      (footprint "eagle-import:0201")
      (fields
        (field (name "PACKAGE") "0201")
        (field (name "HQ_PART") "RE0208620")
        (field (name "LCSC_PART") "C473048")
        (field (name "MANUFACTURER") "FH")
      )
      (libsource (lib "eagle-import") (part "10K-1%0201"))
    )
    (comp (ref "R228")
      (value "0R 1%")
      (footprint "eagle-import:0201")
      (fields
        (field (name "PACKAGE") "0201")
        (field (name "HA_PART") "RE0015349")
        (field (name "LCSC_PART") "C106227")
        (field (name "MANUFACTURER") "Yageo")
      )
      (libsource (lib "eagle-import") (part "0R0201"))
    )
    (comp (ref "R229")
      (value "0R 1%")
      (footprint "eagle-import:0201")
      (fields
        (field (name "PACKAGE") "0201")
        (field (name "HA_PART") "RE0015349")
        (field (name "LCSC_PART") "C106227")
        (field (name "MANUFACTURER") "Yageo")
      )
      (libsource (lib "eagle-import") (part "0R0201"))
    )
    (comp (ref "R231")
      (value "1R 1%")
      (footprint "eagle-import:0603")
      (fields
        (field (name "PACKAGE") "0603")
        (field (name "HQ_PART") "RE0421839")
        (field (name "MANUFACTURER") "RALEC")
        (field (name "MPN") "RTT031R00FTP")
      )
      (libsource (lib "eagle-import") (part "1R-1%0603"))
    )
    (comp (ref "R232")
      (value "1R 1%")
      (footprint "eagle-import:0603")
      (fields
        (field (name "PACKAGE") "0603")
        (field (name "HQ_PART") "RE0421839")
        (field (name "MANUFACTURER") "RALEC")
        (field (name "MPN") "RTT031R00FTP")
      )
      (libsource (lib "eagle-import") (part "1R-1%0603"))
    )
    (comp (ref "T6")
      (value "DMP3013SFV")
      (footprint "eagle-import:POWERDI3333-8_UX_DIO-L")
      (fields (field (name "MANUFACTURER_PART_NUMBER") "DMP3013SFV-7"))
      (libsource (lib "eagle-import") (part "DMP3013SFV-7UX"))
    )
    (comp (ref "T7")
      (value "DMP3013SFV")
      (footprint "eagle-import:POWERDI3333-8_UX_DIO-L")
      (fields (field (name "MANUFACTURER_PART_NUMBER") "DMP3013SFV-7"))
      (libsource (lib "eagle-import") (part "DMP3013SFV-7UX"))
    )
    (comp (ref "T8")
      (value "DMP3013SFV")
      (footprint "eagle-import:POWERDI3333-8_UX_DIO-L")
      (fields (field (name "MANUFACTURER_PART_NUMBER") "DMP3013SFV-7"))
      (libsource (lib "eagle-import") (part "DMP3013SFV-7UX"))
    )
    (comp (ref "T9")
      (value "BSZ065N06")
      (footprint "eagle-import:POWERDI3333-8_UX_DIO-L")
      (fields
        (field (name "MANUFACTURER_PART_NUMBER") "IPZ40N04S5L7R4ATMA1")
        (field (name "COPYRIGHT") "Copyright (C) 2025 Ultra Librarian. All rights reserved.")
      )
      (libsource (lib "eagle-import") (part "IPZ40N04S5L7R4ATMA1"))
    )
    (comp (ref "T10")
      (value "BSZ065N06")
      (footprint "eagle-import:POWERDI3333-8_UX_DIO-L")
      (fields
        (field (name "MANUFACTURER_PART_NUMBER") "IPZ40N04S5L7R4ATMA1")
        (field (name "COPYRIGHT") "Copyright (C) 2025 Ultra Librarian. All rights reserved.")
      )
      (libsource (lib "eagle-import") (part "IPZ40N04S5L7R4ATMA1"))
    )
    (comp (ref "VOP1")
      (value "DNI")
      (footprint "eagle-import:TP-ROUND")
      (libsource (lib "eagle-import") (part "TP-ROUND"))
    )
    (comp (ref "VREL1")
      (value "DNI")
      (footprint "eagle-import:TP-ROUND")
      (libsource (lib "eagle-import") (part "TP-ROUND"))
    )
    (comp (ref "VSRC1")
      (value "DNI")
      (footprint "eagle-import:TP-ROUND")
      (libsource (lib "eagle-import") (part "TP-ROUND"))
    )
    (comp (ref "VTPS1")
      (value "DNI")
      (footprint "eagle-import:TP-ROUND")
      (libsource (lib "eagle-import") (part "TP-ROUND"))
    )
    (comp (ref "VTPS2")
      (value "DNI")
      (footprint "eagle-import:TP-ROUND")
      (libsource (lib "eagle-import") (part "TP-ROUND"))
    )
    (comp (ref "C2")
      (value "100nF 25V")
      (footprint "eagle-import:0201")
      (fields
        (field (name "PACKAGE") "0201")
        (field (name "HQ_PART") "CA0183221")
        (field (name "LCSC_PART") "C76939")
        (field (name "MANUFACTURER") "Samsung")
      )
      (libsource (lib "eagle-import") (part "100NF-25V-0201"))
    )
    (comp (ref "C3")
      (value "10uF 16V")
      (footprint "eagle-import:0603")
      (fields
        (field (name "PACKAGE") "0603")
        (field (name "HQ_PART") "CA0149236")
        (field (name "LCSC_PART") "C92487")
        (field (name "MANUFACTURER") "Murata")
      )
      (libsource (lib "eagle-import") (part "10UF-16V-0603"))
    )
    (comp (ref "C4")
      (value "10uF 16V")
      (footprint "eagle-import:0603")
      (fields
        (field (name "PACKAGE") "0603")
        (field (name "HQ_PART") "CA0149236")
        (field (name "LCSC_PART") "C92487")
        (field (name "MANUFACTURER") "Murata")
      )
      (libsource (lib "eagle-import") (part "10UF-16V-0603"))
    )
    (comp (ref "C5")
      (value "100uF 16V")
      (footprint "eagle-import:5X5.5(DXL)")
      (fields (field (name "LCSC_PART") "C2977550"))
      (libsource (lib "eagle-import") (part "100UF-16V5X5.5(DXL)"))
    )
    (comp (ref "C11")
      (value "1nF 2kV")
      (footprint "eagle-import:1206")
      (fields
        (field (name "PACKAGE") "1206")
        (field (name "HQ_PART") "CA0134884")
        (field (name "LCSC_PART") "C173242")
        (field (name "MANUFACTURER") "Johanson Dielectrics ")
      )
      (libsource (lib "eagle-import") (part "1NF-2KV"))
    )
    (comp (ref "C17")
      (value "100nF 25V")
      (footprint "eagle-import:0201")
      (fields
        (field (name "PACKAGE") "0201")
        (field (name "HQ_PART") "CA0183221")
        (field (name "LCSC_PART") "C76939")
        (field (name "MANUFACTURER") "Samsung")
      )
      (libsource (lib "eagle-import") (part "100NF-25V-0201"))
    )
    (comp (ref "C18")
      (value "100nF 25V")
      (footprint "eagle-import:0201")
      (fields
        (field (name "PACKAGE") "0201")
        (field (name "HQ_PART") "CA0183221")
        (field (name "LCSC_PART") "C76939")
        (field (name "MANUFACTURER") "Samsung")
      )
      (libsource (lib "eagle-import") (part "100NF-25V-0201"))
    )
    (comp (ref "C76")
      (value "100nF 25V")
      (footprint "eagle-import:0201")
      (fields
        (field (name "PACKAGE") "0201")
        (field (name "HQ_PART") "CA0183221")
        (field (name "LCSC_PART") "C76939")
        (field (name "MANUFACTURER") "Samsung")
      )
      (libsource (lib "eagle-import") (part "100NF-25V-0201"))
    )
    (comp (ref "C77")
      (value "10uF 16V")
      (footprint "eagle-import:0603")
      (fields
        (field (name "PACKAGE") "0603")
        (field (name "HQ_PART") "CA0149236")
        (field (name "LCSC_PART") "C92487")
        (field (name "MANUFACTURER") "Murata")
      )
      (libsource (lib "eagle-import") (part "10UF-16V-0603"))
    )
    (comp (ref "C78")
      (value "10uF 16V")
      (footprint "eagle-import:0603")
      (fields
        (field (name "PACKAGE") "0603")
        (field (name "HQ_PART") "CA0149236")
        (field (name "LCSC_PART") "C92487")
        (field (name "MANUFACTURER") "Murata")
      )
      (libsource (lib "eagle-import") (part "10UF-16V-0603"))
    )
    (comp (ref "C79")
      (value "100uF 16V")
      (footprint "eagle-import:5X5.5(DXL)")
      (fields (field (name "LCSC_PART") "C2977550"))
      (libsource (lib "eagle-import") (part "100UF-16V5X5.5(DXL)"))
    )
    (comp (ref "D1")
      (value "Green")
      (footprint "eagle-import:LED-0603")
      (fields
        (field (name "HQ_PART") "PH0010430")
        (field (name "LCSC_PART") "C965804")
        (field (name "MANUFACTURER") "Wurth")
      )
      (libsource (lib "eagle-import") (part "LED-GREENLED-0603"))
    )
    (comp (ref "D2")
      (value "Red")
      (footprint "eagle-import:LED-0603")
      (fields (field (name "LCSC_PART") "C2286"))
      (libsource (lib "eagle-import") (part "LED-REDLED-0603"))
    )
    (comp (ref "D3")
      (value "Green")
      (footprint "eagle-import:LED-0603")
      (fields
        (field (name "HQ_PART") "PH0010430")
        (field (name "LCSC_PART") "C965804")
        (field (name "MANUFACTURER") "Wurth")
      )
      (libsource (lib "eagle-import") (part "LED-GREENLED-0603"))
    )
    (comp (ref "D4")
      (value "Red")
      (footprint "eagle-import:LED-0603")
      (fields (field (name "LCSC_PART") "C2286"))
      (libsource (lib "eagle-import") (part "LED-REDLED-0603"))
    )
    (comp (ref "H1")
      (value "MOUNT-PAD-ROUND3.3")
      (footprint "eagle-import:3,3-PAD")
      (libsource (lib "eagle-import") (part "MOUNT-PAD-ROUND3.3"))
    )
    (comp (ref "H2")
      (value "MOUNT-PAD-ROUND3.3")
      (footprint "eagle-import:3,3-PAD")
      (libsource (lib "eagle-import") (part "MOUNT-PAD-ROUND3.3"))
    )
    (comp (ref "H3")
      (value "MOUNT-PAD-ROUND3.3")
      (footprint "eagle-import:3,3-PAD")
      (libsource (lib "eagle-import") (part "MOUNT-PAD-ROUND3.3"))
    )
    (comp (ref "H4")
      (value "MOUNT-PAD-ROUND3.3")
      (footprint "eagle-import:3,3-PAD")
      (libsource (lib "eagle-import") (part "MOUNT-PAD-ROUND3.3"))
    )
    (comp (ref "IC1")
      (value "AP22653W6")
      (footprint "eagle-import:SOT23-6")
      (fields
        (field (name "HQ_PART") "PM0174903")
        (field (name "LCSC_PART") "C2158037")
        (field (name "MANUFACTURER") "Diodes Incorporated")
      )
      (libsource (lib "eagle-import") (part "AP22653W6"))
    )
    (comp (ref "IC4")
      (value "SN74LVC1G04DBVR")
      (footprint "eagle-import:SOT95P280X145-5N")
      (libsource (lib "eagle-import") (part "74LVC1G04"))
    )
    (comp (ref "IC5")
      (value "SN74LVC1G04DBVR")
      (footprint "eagle-import:SOT95P280X145-5N")
      (libsource (lib "eagle-import") (part "74LVC1G04"))
    )
    (comp (ref "IC8")
      (value "AP22653W6")
      (footprint "eagle-import:SOT23-6")
      (fields
        (field (name "HQ_PART") "PM0174903")
        (field (name "LCSC_PART") "C2158037")
        (field (name "MANUFACTURER") "Diodes Incorporated")
      )
      (libsource (lib "eagle-import") (part "AP22653W6"))
    )
    (comp (ref "R1")
      (value "10K 1%")
      (footprint "eagle-import:0201")
      (fields
        (field (name "PACKAGE") "0201")
        (field (name "HQ_PART") "RE0208620")
        (field (name "LCSC_PART") "C473048")
        (field (name "MANUFACTURER") "FH")
      )
      (libsource (lib "eagle-import") (part "10K-1%0201"))
    )
    (comp (ref "R2")
      (value "1M 1%")
      (footprint "eagle-import:1206")
      (fields
        (field (name "PACKAGE") "1206")
        (field (name "HQ_PART") "RE0188103")
        (field (name "LCSC_PART") "C17927")
        (field (name "MANUFACTURER") "Uniohm")
      )
      (libsource (lib "eagle-import") (part "1M-1%1206"))
    )
    (comp (ref "R3")
      (value "10K 1%")
      (footprint "eagle-import:0201")
      (fields
        (field (name "PACKAGE") "0201")
        (field (name "HQ_PART") "RE0208620")
        (field (name "LCSC_PART") "C473048")
        (field (name "MANUFACTURER") "FH")
      )
      (libsource (lib "eagle-import") (part "10K-1%0201"))
    )
    (comp (ref "R4")
      (value "10K 1%")
      (footprint "eagle-import:0201")
      (fields
        (field (name "PACKAGE") "0201")
        (field (name "HQ_PART") "RE0208620")
        (field (name "LCSC_PART") "C473048")
        (field (name "MANUFACTURER") "FH")
      )
      (libsource (lib "eagle-import") (part "10K-1%0201"))
    )
    (comp (ref "R12")
      (value "1K 1%")
      (footprint "eagle-import:0402")
      (fields
        (field (name "HQ_PART") "RE0208724")
        (field (name "LCSC_PART") "C11702")
        (field (name "MANUFACTURER") "FH")
      )
      (libsource (lib "eagle-import") (part "1K-1%0402"))
    )
    (comp (ref "R13")
      (value "10K 1%")
      (footprint "eagle-import:0201")
      (fields
        (field (name "PACKAGE") "0201")
        (field (name "HQ_PART") "RE0208620")
        (field (name "LCSC_PART") "C473048")
        (field (name "MANUFACTURER") "FH")
      )
      (libsource (lib "eagle-import") (part "10K-1%0201"))
    )
    (comp (ref "R14")
      (value "1K 1%")
      (footprint "eagle-import:0402")
      (fields
        (field (name "HQ_PART") "RE0208724")
        (field (name "LCSC_PART") "C11702")
        (field (name "MANUFACTURER") "FH")
      )
      (libsource (lib "eagle-import") (part "1K-1%0402"))
    )
    (comp (ref "R15")
      (value "1K 1%")
      (footprint "eagle-import:0402")
      (fields
        (field (name "HQ_PART") "RE0208724")
        (field (name "LCSC_PART") "C11702")
        (field (name "MANUFACTURER") "FH")
      )
      (libsource (lib "eagle-import") (part "1K-1%0402"))
    )
    (comp (ref "R16")
      (value "10K 1%")
      (footprint "eagle-import:0201")
      (fields
        (field (name "PACKAGE") "0201")
        (field (name "HQ_PART") "RE0208620")
        (field (name "LCSC_PART") "C473048")
        (field (name "MANUFACTURER") "FH")
      )
      (libsource (lib "eagle-import") (part "10K-1%0201"))
    )
    (comp (ref "R17")
      (value "1K 1%")
      (footprint "eagle-import:0402")
      (fields
        (field (name "HQ_PART") "RE0208724")
        (field (name "LCSC_PART") "C11702")
        (field (name "MANUFACTURER") "FH")
      )
      (libsource (lib "eagle-import") (part "1K-1%0402"))
    )
    (comp (ref "R56")
      (value "10K 1%")
      (footprint "eagle-import:0201")
      (fields
        (field (name "PACKAGE") "0201")
        (field (name "HQ_PART") "RE0208620")
        (field (name "LCSC_PART") "C473048")
        (field (name "MANUFACTURER") "FH")
      )
      (libsource (lib "eagle-import") (part "10K-1%0201"))
    )
    (comp (ref "R66")
      (value "10K 1%")
      (footprint "eagle-import:0201")
      (fields
        (field (name "PACKAGE") "0201")
        (field (name "HQ_PART") "RE0208620")
        (field (name "LCSC_PART") "C473048")
        (field (name "MANUFACTURER") "FH")
      )
      (libsource (lib "eagle-import") (part "10K-1%0201"))
    )
    (comp (ref "R67")
      (value "10K 1%")
      (footprint "eagle-import:0201")
      (fields
        (field (name "PACKAGE") "0201")
        (field (name "HQ_PART") "RE0208620")
        (field (name "LCSC_PART") "C473048")
        (field (name "MANUFACTURER") "FH")
      )
      (libsource (lib "eagle-import") (part "10K-1%0201"))
    )
    (comp (ref "USBA_1-2")
      (value "61400826021")
      (footprint "eagle-import:61400826021")
      (libsource (lib "eagle-import") (part "61400826021"))
    )
    (comp (ref "USBA_VB1")
      (value "DNI")
      (footprint "eagle-import:TP-ROUND")
      (libsource (lib "eagle-import") (part "TP-ROUND"))
    )
    (comp (ref "USBA_VB2")
      (value "DNI")
      (footprint "eagle-import:TP-ROUND")
      (libsource (lib "eagle-import") (part "TP-ROUND"))
    )
    (comp (ref "3V3A1")
      (value "DNI")
      (footprint "eagle-import:TP-ROUND")
      (libsource (lib "eagle-import") (part "TP-ROUND"))
    )
    (comp (ref "C95")
      (value "100nF 25V")
      (footprint "eagle-import:0201")
      (fields
        (field (name "PACKAGE") "0201")
        (field (name "HQ_PART") "CA0183221")
        (field (name "LCSC_PART") "C76939")
        (field (name "MANUFACTURER") "Samsung")
      )
      (libsource (lib "eagle-import") (part "100NF-25V-0201"))
    )
    (comp (ref "C96")
      (value "100nF 25V")
      (footprint "eagle-import:0201")
      (fields
        (field (name "PACKAGE") "0201")
        (field (name "HQ_PART") "CA0183221")
        (field (name "LCSC_PART") "C76939")
        (field (name "MANUFACTURER") "Samsung")
      )
      (libsource (lib "eagle-import") (part "100NF-25V-0201"))
    )
    (comp (ref "C97")
      (value "100nF 25V")
      (footprint "eagle-import:0201")
      (fields
        (field (name "PACKAGE") "0201")
        (field (name "HQ_PART") "CA0183221")
        (field (name "LCSC_PART") "C76939")
        (field (name "MANUFACTURER") "Samsung")
      )
      (libsource (lib "eagle-import") (part "100NF-25V-0201"))
    )
    (comp (ref "C98")
      (value "100nF 25V")
      (footprint "eagle-import:0201")
      (fields
        (field (name "PACKAGE") "0201")
        (field (name "HQ_PART") "CA0183221")
        (field (name "LCSC_PART") "C76939")
        (field (name "MANUFACTURER") "Samsung")
      )
      (libsource (lib "eagle-import") (part "100NF-25V-0201"))
    )
    (comp (ref "C121")
      (value "100nF 25V")
      (footprint "eagle-import:0201")
      (fields
        (field (name "PACKAGE") "0201")
        (field (name "HQ_PART") "CA0183221")
        (field (name "LCSC_PART") "C76939")
        (field (name "MANUFACTURER") "Samsung")
      )
      (libsource (lib "eagle-import") (part "100NF-25V-0201"))
    )
    (comp (ref "C122")
      (value "100nF 25V")
      (footprint "eagle-import:0201")
      (fields
        (field (name "PACKAGE") "0201")
        (field (name "HQ_PART") "CA0183221")
        (field (name "LCSC_PART") "C76939")
        (field (name "MANUFACTURER") "Samsung")
      )
      (libsource (lib "eagle-import") (part "100NF-25V-0201"))
    )
    (comp (ref "C123")
      (value "100nF 25V")
      (footprint "eagle-import:0201")
      (fields
        (field (name "PACKAGE") "0201")
        (field (name "HQ_PART") "CA0183221")
        (field (name "LCSC_PART") "C76939")
        (field (name "MANUFACTURER") "Samsung")
      )
      (libsource (lib "eagle-import") (part "100NF-25V-0201"))
    )
    (comp (ref "C124")
      (value "100nF 25V")
      (footprint "eagle-import:0201")
      (fields
        (field (name "PACKAGE") "0201")
        (field (name "HQ_PART") "CA0183221")
        (field (name "LCSC_PART") "C76939")
        (field (name "MANUFACTURER") "Samsung")
      )
      (libsource (lib "eagle-import") (part "100NF-25V-0201"))
    )
    (comp (ref "C125")
      (value "100nF 25V")
      (footprint "eagle-import:0201")
      (fields
        (field (name "PACKAGE") "0201")
        (field (name "HQ_PART") "CA0183221")
        (field (name "LCSC_PART") "C76939")
        (field (name "MANUFACTURER") "Samsung")
      )
      (libsource (lib "eagle-import") (part "100NF-25V-0201"))
    )
    (comp (ref "C126")
      (value "100nF 25V")
      (footprint "eagle-import:0201")
      (fields
        (field (name "PACKAGE") "0201")
        (field (name "HQ_PART") "CA0183221")
        (field (name "LCSC_PART") "C76939")
        (field (name "MANUFACTURER") "Samsung")
      )
      (libsource (lib "eagle-import") (part "100NF-25V-0201"))
    )
    (comp (ref "C127")
      (value "100nF 25V")
      (footprint "eagle-import:0201")
      (fields
        (field (name "PACKAGE") "0201")
        (field (name "HQ_PART") "CA0183221")
        (field (name "LCSC_PART") "C76939")
        (field (name "MANUFACTURER") "Samsung")
      )
      (libsource (lib "eagle-import") (part "100NF-25V-0201"))
    )
    (comp (ref "C128")
      (value "6.8nF 50V")
      (footprint "eagle-import:0201")
      (fields
        (field (name "PACKAGE") "0201")
        (field (name "HQ_PART") "CA0363038")
        (field (name "LCSC_PART") "C285015")
        (field (name "MANUFACTURER") "FH")
      )
      (libsource (lib "eagle-import") (part "6.8NF-50V0201"))
    )
    (comp (ref "C129")
      (value "6.8nF 50V")
      (footprint "eagle-import:0201")
      (fields
        (field (name "PACKAGE") "0201")
        (field (name "HQ_PART") "CA0363038")
        (field (name "LCSC_PART") "C285015")
        (field (name "MANUFACTURER") "FH")
      )
      (libsource (lib "eagle-import") (part "6.8NF-50V0201"))
    )
    (comp (ref "C130")
      (value "22nF 50V")
      (footprint "eagle-import:0402")
      (fields
        (field (name "PACKAGE") "0402")
        (field (name "HQ_PART") "CA0171190")
        (field (name "LCSC_PART") "C1532")
        (field (name "MANUFACTURER") "Samsung")
      )
      (libsource (lib "eagle-import") (part "22NF-50V0402"))
    )
    (comp (ref "C131")
      (value "1nF 2kV")
      (footprint "eagle-import:1206")
      (fields
        (field (name "PACKAGE") "1206")
        (field (name "HQ_PART") "CA0134884")
        (field (name "LCSC_PART") "C173242")
        (field (name "MANUFACTURER") "Johanson Dielectrics ")
      )
      (libsource (lib "eagle-import") (part "1NF-2KV"))
    )
    (comp (ref "C132")
      (value "18pF 50V")
      (footprint "eagle-import:0201")
      (fields
        (field (name "PACKAGE") "0201")
        (field (name "HQ_PART") "CA0486739")
        (field (name "LCSC_PART") "C62164")
        (field (name "MANUFACTURER") "Yageo")
      )
      (libsource (lib "eagle-import") (part "18PF-50V-0201"))
    )
    (comp (ref "C133")
      (value "18pF 50V")
      (footprint "eagle-import:0201")
      (fields
        (field (name "PACKAGE") "0201")
        (field (name "HQ_PART") "CA0486739")
        (field (name "LCSC_PART") "C62164")
        (field (name "MANUFACTURER") "Yageo")
      )
      (libsource (lib "eagle-import") (part "18PF-50V-0201"))
    )
    (comp (ref "C134")
      (value "4.7uF 25V")
      (footprint "eagle-import:0402")
      (fields
        (field (name "PACKAGE") "0402")
        (field (name "HQ_PART") "ZHLM0023346")
        (field (name "LCSC_PART") "C22367824")
        (field (name "MANUFACTURER") "Murata")
      )
      (libsource (lib "eagle-import") (part "4.7UF-25V0402"))
    )
    (comp (ref "ETH2")
      (value "J1B1211CCD")
      (footprint "eagle-import:J1B1211CCD")
      (fields
        (field (name "HQ_PART") "UN0002907")
        (field (name "LCSC_PART") "C910371")
        (field (name "MANUFACTURER") "WIZnet")
      )
      (libsource (lib "eagle-import") (part "J1B1211CCD"))
    )
    (comp (ref "IC17")
      (value "W5500")
      (footprint "eagle-import:LQFP48")
      (fields
        (field (name "HQ_PART") "IC0084426")
        (field (name "LCSC_PART") "C32843")
        (field (name "MANUFACTURER") "WIZNET")
      )
      (libsource (lib "eagle-import") (part "W5500"))
    )
    (comp (ref "L5")
      (value "BLM18EG221TN1D")
      (footprint "eagle-import:0603")
      (fields
        (field (name "HQ_PART") "WF0012312")
        (field (name "LCSC_PART") "C113025")
        (field (name "MANUFACTURER") "Murata")
      )
      (libsource (lib "eagle-import") (part "BLM18EG221TN1D"))
    )
    (comp (ref "R125")
      (value "0R 1%")
      (footprint "eagle-import:0201")
      (fields
        (field (name "PACKAGE") "0201")
        (field (name "HA_PART") "RE0015349")
        (field (name "LCSC_PART") "C106227")
        (field (name "MANUFACTURER") "Yageo")
      )
      (libsource (lib "eagle-import") (part "0R0201"))
    )
    (comp (ref "R126")
      (value "0R 1%")
      (footprint "eagle-import:0201")
      (fields
        (field (name "PACKAGE") "0201")
        (field (name "HA_PART") "RE0015349")
        (field (name "LCSC_PART") "C106227")
        (field (name "MANUFACTURER") "Yageo")
      )
      (libsource (lib "eagle-import") (part "0R0201"))
    )
    (comp (ref "R127")
      (value "49.9R 1%")
      (footprint "eagle-import:0201")
      (fields
        (field (name "PACKAGE") "0201")
        (field (name "HQ_PART") "RE0721921")
        (field (name "LCSC_PART") "C155744")
        (field (name "MANUFACTURER") "FH")
      )
      (libsource (lib "eagle-import") (part "49.9R-1%0201"))
    )
    (comp (ref "R128")
      (value "49.9R 1%")
      (footprint "eagle-import:0201")
      (fields
        (field (name "PACKAGE") "0201")
        (field (name "HQ_PART") "RE0721921")
        (field (name "LCSC_PART") "C155744")
        (field (name "MANUFACTURER") "FH")
      )
      (libsource (lib "eagle-import") (part "49.9R-1%0201"))
    )
    (comp (ref "R129")
      (value "49.9R 1%")
      (footprint "eagle-import:0201")
      (fields
        (field (name "PACKAGE") "0201")
        (field (name "HQ_PART") "RE0721921")
        (field (name "LCSC_PART") "C155744")
        (field (name "MANUFACTURER") "FH")
      )
      (libsource (lib "eagle-import") (part "49.9R-1%0201"))
    )
    (comp (ref "R130")
      (value "49.9R 1%")
      (footprint "eagle-import:0201")
      (fields
        (field (name "PACKAGE") "0201")
        (field (name "HQ_PART") "RE0721921")
        (field (name "LCSC_PART") "C155744")
        (field (name "MANUFACTURER") "FH")
      )
      (libsource (lib "eagle-import") (part "49.9R-1%0201"))
    )
    (comp (ref "R131")
      (value "3.3R 1%")
      (footprint "eagle-import:0201")
      (fields
        (field (name "PACKAGE") "0201")
        (field (name "HQ_PART") "RE0422979")
        (field (name "LCSC_PART") "C158547")
        (field (name "MANUFACTURER") "Uniohm")
      )
      (libsource (lib "eagle-import") (part "3.3R-1%0201"))
    )
    (comp (ref "R132")
      (value "3.3R 1%")
      (footprint "eagle-import:0201")
      (fields
        (field (name "PACKAGE") "0201")
        (field (name "HQ_PART") "RE0422979")
        (field (name "LCSC_PART") "C158547")
        (field (name "MANUFACTURER") "Uniohm")
      )
      (libsource (lib "eagle-import") (part "3.3R-1%0201"))
    )
    (comp (ref "R133")
      (value "3.3R 1%")
      (footprint "eagle-import:0201")
      (fields
        (field (name "PACKAGE") "0201")
        (field (name "HQ_PART") "RE0422979")
        (field (name "LCSC_PART") "C158547")
        (field (name "MANUFACTURER") "Uniohm")
      )
      (libsource (lib "eagle-import") (part "3.3R-1%0201"))
    )
    (comp (ref "R134")
      (value "3.3R 1%")
      (footprint "eagle-import:0201")
      (fields
        (field (name "PACKAGE") "0201")
        (field (name "HQ_PART") "RE0422979")
        (field (name "LCSC_PART") "C158547")
        (field (name "MANUFACTURER") "Uniohm")
      )
      (libsource (lib "eagle-import") (part "3.3R-1%0201"))
    )
    (comp (ref "R135")
      (value "4.7K 1%")
      (footprint "eagle-import:0201")
      (fields
        (field (name "PACKAGE") "0201")
        (field (name "HQ_PART") "RE0208670")
        (field (name "LCSC_PART") "C270346")
        (field (name "MANUFACTURER") "RALEC")
      )
      (libsource (lib "eagle-import") (part "4.7K-1%0201"))
    )
    (comp (ref "R136")
      (value "12.4K 1%")
      (footprint "eagle-import:0201")
      (fields
        (field (name "PACKAGE") "0201")
        (field (name "HQ_PART") "RE0186667")
        (field (name "LCSC_PART") "C423760")
        (field (name "MANUFACTURER") "Yageo")
      )
      (libsource (lib "eagle-import") (part "12.4K-1%0201"))
    )
    (comp (ref "R137")
      (value "1M 1%")
      (footprint "eagle-import:0201")
      (fields
        (field (name "PACKAGE") "0201")
        (field (name "HQ_PART") "RE0422946")
        (field (name "LCSC_PART") "C295786")
        (field (name "MANUFACTURER") "Yageo")
      )
      (libsource (lib "eagle-import") (part "1M-1%0201"))
    )
    (comp (ref "R138")
      (value "470R 1%")
      (footprint "eagle-import:0402")
      (fields
        (field (name "PACKAGE") "0402")
        (field (name "HQ_PART") "RE0205922")
        (field (name "LCSC_PART") "C25117")
        (field (name "MANUFACTURER") "Panasonic")
      )
      (libsource (lib "eagle-import") (part "470R-1%0402"))
    )
    (comp (ref "R139")
      (value "470R 1%")
      (footprint "eagle-import:0402")
      (fields
        (field (name "PACKAGE") "0402")
        (field (name "HQ_PART") "RE0205922")
        (field (name "LCSC_PART") "C25117")
        (field (name "MANUFACTURER") "Panasonic")
      )
      (libsource (lib "eagle-import") (part "470R-1%0402"))
    )
    (comp (ref "R140")
      (value "470R 1%")
      (footprint "eagle-import:0402")
      (fields
        (field (name "PACKAGE") "0402")
        (field (name "HQ_PART") "RE0205922")
        (field (name "LCSC_PART") "C25117")
        (field (name "MANUFACTURER") "Panasonic")
      )
      (libsource (lib "eagle-import") (part "470R-1%0402"))
    )
    (comp (ref "R141")
      (value "1M 1%")
      (footprint "eagle-import:1206")
      (fields
        (field (name "PACKAGE") "1206")
        (field (name "HQ_PART") "RE0188103")
        (field (name "LCSC_PART") "C17927")
        (field (name "MANUFACTURER") "Uniohm")
      )
      (libsource (lib "eagle-import") (part "1M-1%1206"))
    )
    (comp (ref "R226")
      (value "4.7K 1%")
      (footprint "eagle-import:0201")
      (fields
        (field (name "HQ_PART") "RE0208670")
        (field (name "LCSC_PART") "C270346")
        (field (name "MANUFACTURER") "RALEC")
      )
      (libsource (lib "eagle-import") (part "4.7K-1%0201"))
    )
    (comp (ref "R227")
      (value "4.7K 1%")
      (footprint "eagle-import:0201")
      (fields
        (field (name "HQ_PART") "RE0208670")
        (field (name "LCSC_PART") "C270346")
        (field (name "MANUFACTURER") "RALEC")
      )
      (libsource (lib "eagle-import") (part "4.7K-1%0201"))
    )
    (comp (ref "X3")
      (value "25MHz")
      (footprint "eagle-import:WE-XTAL_CFPX-180")
      (fields
        (field (name "HQ_PART") "CR0250343")
        (field (name "LCSC_PART") "C13740")
        (field (name "MANUFACTURER") "Epson")
      )
      (libsource (lib "eagle-import") (part "CRYSTAL-3225X322525MOB4SI"))
    )
    (comp (ref "+3V")
      (value "DNI")
      (footprint "eagle-import:TP-ROUND")
      (libsource (lib "eagle-import") (part "TP-ROUND"))
    )
    (comp (ref "+5VA")
      (value "DNI")
      (footprint "eagle-import:TP-ROUND")
      (libsource (lib "eagle-import") (part "TP-ROUND"))
    )
    (comp (ref "+24V")
      (value "DNI")
      (footprint "eagle-import:TP-ROUND")
      (libsource (lib "eagle-import") (part "TP-ROUND"))
    )
    (comp (ref "3VFB")
      (value "DNI")
      (footprint "eagle-import:TP-ROUND")
      (libsource (lib "eagle-import") (part "TP-ROUND"))
    )
    (comp (ref "5VFB")
      (value "DNI")
      (footprint "eagle-import:TP-ROUND")
      (libsource (lib "eagle-import") (part "TP-ROUND"))
    )
    (comp (ref "24VGND")
      (value "DNI")
      (footprint "eagle-import:TP-ROUND")
      (libsource (lib "eagle-import") (part "TP-ROUND"))
    )
    (comp (ref "C30")
      (value "100nF 25V")
      (footprint "eagle-import:0201")
      (fields
        (field (name "PACKAGE") "0201")
        (field (name "HQ_PART") "CA0183221")
        (field (name "LCSC_PART") "C76939")
        (field (name "MANUFACTURER") "Samsung")
      )
      (libsource (lib "eagle-import") (part "100NF-25V-0201"))
    )
    (comp (ref "C31")
      (value "22uF 25V")
      (footprint "eagle-import:1206")
      (fields
        (field (name "PACKAGE") "1206")
        (field (name "HQ_PART") "CA0182777")
        (field (name "LCSC_PART") "C12891")
        (field (name "MANUFACTURER") "FH")
      )
      (libsource (lib "eagle-import") (part "22UF-25V-1206"))
    )
    (comp (ref "C32")
      (value "100nF 25V")
      (footprint "eagle-import:0201")
      (fields
        (field (name "PACKAGE") "0201")
        (field (name "HQ_PART") "CA0183221")
        (field (name "LCSC_PART") "C76939")
        (field (name "MANUFACTURER") "Samsung")
      )
      (libsource (lib "eagle-import") (part "100NF-25V-0201"))
    )
    (comp (ref "C33")
      (value "22uF 25V")
      (footprint "eagle-import:1206")
      (fields
        (field (name "PACKAGE") "1206")
        (field (name "HQ_PART") "CA0182777")
        (field (name "LCSC_PART") "C12891")
        (field (name "MANUFACTURER") "FH")
      )
      (libsource (lib "eagle-import") (part "22UF-25V-1206"))
    )
    (comp (ref "C34")
      (value "22uF 25V")
      (footprint "eagle-import:1206")
      (fields
        (field (name "PACKAGE") "1206")
        (field (name "HQ_PART") "CA0182777")
        (field (name "LCSC_PART") "C12891")
        (field (name "MANUFACTURER") "FH")
      )
      (libsource (lib "eagle-import") (part "22UF-25V-1206"))
    )
    (comp (ref "C35")
      (value "100nF 25V")
      (footprint "eagle-import:0201")
      (fields
        (field (name "PACKAGE") "0201")
        (field (name "HQ_PART") "CA0183221")
        (field (name "LCSC_PART") "C76939")
        (field (name "MANUFACTURER") "Samsung")
      )
      (libsource (lib "eagle-import") (part "100NF-25V-0201"))
    )
    (comp (ref "C36")
      (value "33pF 50V")
      (footprint "eagle-import:0201")
      (fields (field (name "PACKAGE") "0201") (field (name "LCSC_PART") "C56903"))
      (libsource (lib "eagle-import") (part "33PF-50V0201"))
    )
    (comp (ref "C37")
      (value "100nF 25V")
      (footprint "eagle-import:0201")
      (fields
        (field (name "PACKAGE") "0201")
        (field (name "HQ_PART") "CA0183221")
        (field (name "LCSC_PART") "C76939")
        (field (name "MANUFACTURER") "Samsung")
      )
      (libsource (lib "eagle-import") (part "100NF-25V-0201"))
    )
    (comp (ref "C38")
      (value "100nF 25V")
      (footprint "eagle-import:0201")
      (fields
        (field (name "PACKAGE") "0201")
        (field (name "HQ_PART") "CA0183221")
        (field (name "LCSC_PART") "C76939")
        (field (name "MANUFACTURER") "Samsung")
      )
      (libsource (lib "eagle-import") (part "100NF-25V-0201"))
    )
    (comp (ref "C71")
      (value "100nF 25V")
      (footprint "eagle-import:0201")
      (fields
        (field (name "PACKAGE") "0201")
        (field (name "HQ_PART") "CA0183221")
        (field (name "LCSC_PART") "C76939")
        (field (name "MANUFACTURER") "Samsung")
      )
      (libsource (lib "eagle-import") (part "100NF-25V-0201"))
    )
    (comp (ref "C72")
      (value "22uF 25V")
      (footprint "eagle-import:1206")
      (fields
        (field (name "PACKAGE") "1206")
        (field (name "HQ_PART") "CA0182777")
        (field (name "LCSC_PART") "C12891")
        (field (name "MANUFACTURER") "FH")
      )
      (libsource (lib "eagle-import") (part "22UF-25V-1206"))
    )
    (comp (ref "C73")
      (value "22uF 25V")
      (footprint "eagle-import:1206")
      (fields
        (field (name "PACKAGE") "1206")
        (field (name "HQ_PART") "CA0182777")
        (field (name "LCSC_PART") "C12891")
        (field (name "MANUFACTURER") "FH")
      )
      (libsource (lib "eagle-import") (part "22UF-25V-1206"))
    )
    (comp (ref "C74")
      (value "22uF 25V")
      (footprint "eagle-import:1206")
      (fields
        (field (name "PACKAGE") "1206")
        (field (name "HQ_PART") "CA0182777")
        (field (name "LCSC_PART") "C12891")
        (field (name "MANUFACTURER") "FH")
      )
      (libsource (lib "eagle-import") (part "22UF-25V-1206"))
    )
    (comp (ref "C75")
      (value "33pF 50V")
      (footprint "eagle-import:0201")
      (fields (field (name "PACKAGE") "0201") (field (name "LCSC_PART") "C56903"))
      (libsource (lib "eagle-import") (part "33PF-50V0201"))
    )
    (comp (ref "C84")
      (value "1nF 25V")
      (footprint "eagle-import:0201")
      (fields
        (field (name "PACKAGE") "0201")
        (field (name "HQ_PART") "CA0136821")
        (field (name "LCSC_PART") "C7694325V")
        (field (name "MANUFACTURER") "Samsung")
      )
      (libsource (lib "eagle-import") (part "1NF-25V-0201"))
    )
    (comp (ref "C85")
      (value "1nF 25V")
      (footprint "eagle-import:0201")
      (fields
        (field (name "PACKAGE") "0201")
        (field (name "HQ_PART") "CA0136821")
        (field (name "LCSC_PART") "C7694325V")
        (field (name "MANUFACTURER") "Samsung")
      )
      (libsource (lib "eagle-import") (part "1NF-25V-0201"))
    )
    (comp (ref "C252")
      (value "330uF 50V")
      (footprint "eagle-import:10X10.5(DXL)")
      (fields (field (name "LCSC_PART") "C2895745") (field (name "MPN") "EEE-FT1H331AP"))
      (libsource (lib "eagle-import") (part "330UF-50V10X10.5(DXL)"))
    )
    (comp (ref "C253")
      (value "330uF 50V")
      (footprint "eagle-import:10X10.5(DXL)")
      (fields (field (name "LCSC_PART") "C2895745") (field (name "MPN") "EEE-FT1H331AP"))
      (libsource (lib "eagle-import") (part "330UF-50V10X10.5(DXL)"))
    )
    (comp (ref "C256")
      (value "330uF 50V")
      (footprint "eagle-import:10X10.5(DXL)")
      (fields (field (name "LCSC_PART") "C2895745") (field (name "MPN") "EEE-FT1H331AP"))
      (libsource (lib "eagle-import") (part "330UF-50V10X10.5(DXL)"))
    )
    (comp (ref "C257")
      (value "330uF 50V")
      (footprint "eagle-import:10X10.5(DXL)")
      (fields (field (name "LCSC_PART") "C2895745") (field (name "MPN") "EEE-FT1H331AP"))
      (libsource (lib "eagle-import") (part "330UF-50V10X10.5(DXL)"))
    )
    (comp (ref "D9")
      (value "SMBJ33A")
      (footprint "eagle-import:SMB")
      (libsource (lib "eagle-import") (part "DIODE-SMB"))
    )
    (comp (ref "D11")
      (value "SMBJ33A")
      (footprint "eagle-import:SMB")
      (libsource (lib "eagle-import") (part "DIODE-SMB"))
    )
    (comp (ref "F1")
      (value "2A")
      (footprint "eagle-import:FUSE_3544-2")
      (fields (field (name "MANUFACTURER") "Keystone") (field (name "MPN") "3544-2"))
      (libsource (lib "eagle-import") (part "BLADE-FUSE"))
    )
    (comp (ref "F2")
      (value "DNI")
      (footprint "eagle-import:FUSE_3544-2")
      (fields (field (name "MANUFACTURER") "Keystone") (field (name "MPN") "3544-2"))
      (libsource (lib "eagle-import") (part "BLADE-FUSE"))
    )
    (comp (ref "F3")
      (value "15A")
      (footprint "eagle-import:FUSE_3544-2")
      (fields (field (name "MANUFACTURER") "Keystone") (field (name "MPN") "3544-2"))
      (libsource (lib "eagle-import") (part "BLADE-FUSE"))
    )
    (comp (ref "IC2")
      (value "MP2315GJ-Z")
      (footprint "eagle-import:SOT65P280X110-8N")
      (fields
        (field (name "HQ_PART") "IC0339027")
        (field (name "LCSC_PART") "C45889")
        (field (name "MANUFACTURER") "MPS")
      )
      (libsource (lib "eagle-import") (part "MP2315TSOT23-8"))
    )
    (comp (ref "IC40")
      (value "MP2315GJ-Z")
      (footprint "eagle-import:SOT65P280X110-8N")
      (fields
        (field (name "HQ_PART") "IC0339027")
        (field (name "LCSC_PART") "C45889")
        (field (name "MANUFACTURER") "MPS")
      )
      (libsource (lib "eagle-import") (part "MP2315TSOT23-8"))
    )
    (comp (ref "J8")
      (value "691244510006")
      (footprint "eagle-import:691244510006")
      (libsource (lib "eagle-import") (part "691244510006"))
    )
    (comp (ref "L3")
      (value "4.7uH 3.5A")
      (footprint "eagle-import:SRR5228A")
      (fields
        (field (name "LCSC_PART") "C14258")
        (field (name "MANUFACTURER") "SXN")
        (field (name "MPN") "YP0503-4R7M")
      )
      (libsource (lib "eagle-import") (part "4.2UH"))
    )
    (comp (ref "L11")
      (value "4.7uH 3.5A")
      (footprint "eagle-import:SRR5228A")
      (fields
        (field (name "LCSC_PART") "C14258")
        (field (name "MANUFACTURER") "SXN")
        (field (name "MPN") "YP0503-4R7M")
      )
      (libsource (lib "eagle-import") (part "4.2UH"))
    )
    (comp (ref "R22")
      (value "33K 1%")
      (footprint "eagle-import:0201")
      (fields (field (name "PACKAGE") "0201") (field (name "LCSC_PART") "C473534"))
      (libsource (lib "eagle-import") (part "33K-1%0201"))
    )
    (comp (ref "R23")
      (value "40.2K 1%")
      (footprint "eagle-import:0201")
      (fields (field (name "PACKAGE") "0201") (field (name "LCSC_PART") "C274875"))
      (libsource (lib "eagle-import") (part "40.2K-1%0201"))
    )
    (comp (ref "R33")
      (value "12.7K 1%")
      (footprint "eagle-import:0201")
      (fields
        (field (name "PACKAGE") "0201")
        (field (name "LCSC_PART") "C423755")
        (field (name "MANUFACTURER") "UNI-ROYAL")
        (field (name "MPN") "0201WMF1272TEE")
      )
      (libsource (lib "eagle-import") (part "12.7K-1%0201"))
    )
    (comp (ref "R34")
      (value "10R 1%")
      (footprint "eagle-import:0201")
      (fields
        (field (name "PACKAGE") "0201")
        (field (name "HQ_PART") "RE0210247")
        (field (name "LCSC_PART") "C270817")
        (field (name "MANUFACTURER") "Yageo")
      )
      (libsource (lib "eagle-import") (part "10R-1%0201"))
    )
    (comp (ref "R36")
      (value "75K 1%")
      (footprint "eagle-import:0201")
      (fields
        (field (name "PACKAGE") "0201")
        (field (name "LCSC_PART") "C270339")
        (field (name "MANUFACTURER") "UNI-ROYAL")
        (field (name "MPN") "0201WMF7502TEE")
      )
      (libsource (lib "eagle-import") (part "75K-1%-0201"))
    )
    (comp (ref "R37")
      (value "100K 1%")
      (footprint "eagle-import:0201")
      (fields (field (name "PACKAGE") "0201") (field (name "LCSC_PART") "C270364"))
      (libsource (lib "eagle-import") (part "100K-1%0201"))
    )
    (comp (ref "R38")
      (value "10K 1%")
      (footprint "eagle-import:0201")
      (fields
        (field (name "PACKAGE") "0201")
        (field (name "HQ_PART") "RE0208620")
        (field (name "LCSC_PART") "C473048")
        (field (name "MANUFACTURER") "FH")
      )
      (libsource (lib "eagle-import") (part "10K-1%0201"))
    )
    (comp (ref "R39")
      (value "40.2K 1%")
      (footprint "eagle-import:0201")
      (fields (field (name "PACKAGE") "0201") (field (name "LCSC_PART") "C274875"))
      (libsource (lib "eagle-import") (part "40.2K-1%0201"))
    )
    (comp (ref "R40")
      (value "7.5K 1%")
      (footprint "eagle-import:0201")
      (fields (field (name "PACKAGE") "0201") (field (name "LCSC_PART") "C473504"))
      (libsource (lib "eagle-import") (part "7.5K-1%0201"))
    )
    (comp (ref "R41")
      (value "10R 1%")
      (footprint "eagle-import:0201")
      (fields
        (field (name "PACKAGE") "0201")
        (field (name "HQ_PART") "RE0210247")
        (field (name "LCSC_PART") "C270817")
        (field (name "MANUFACTURER") "Yageo")
      )
      (libsource (lib "eagle-import") (part "10R-1%0201"))
    )
    (comp (ref "R43")
      (value "75K 1%")
      (footprint "eagle-import:0201")
      (fields
        (field (name "PACKAGE") "0201")
        (field (name "LCSC_PART") "C270339")
        (field (name "MANUFACTURER") "UNI-ROYAL")
        (field (name "MPN") "0201WMF7502TEE")
      )
      (libsource (lib "eagle-import") (part "75K-1%-0201"))
    )
    (comp (ref "R44")
      (value "100K 1%")
      (footprint "eagle-import:0201")
      (fields (field (name "PACKAGE") "0201") (field (name "LCSC_PART") "C270364"))
      (libsource (lib "eagle-import") (part "100K-1%0201"))
    )
    (comp (ref "R45")
      (value "10K 1%")
      (footprint "eagle-import:0201")
      (fields
        (field (name "PACKAGE") "0201")
        (field (name "HQ_PART") "RE0208620")
        (field (name "LCSC_PART") "C473048")
        (field (name "MANUFACTURER") "FH")
      )
      (libsource (lib "eagle-import") (part "10K-1%0201"))
    )
    (comp (ref "R70")
      (value "100K 1%")
      (footprint "eagle-import:0201")
      (fields (field (name "PACKAGE") "0201") (field (name "LCSC_PART") "C270364"))
      (libsource (lib "eagle-import") (part "100K-1%0201"))
    )
    (comp (ref "R71")
      (value "10K 1%")
      (footprint "eagle-import:0201")
      (fields
        (field (name "PACKAGE") "0201")
        (field (name "HQ_PART") "RE0208620")
        (field (name "LCSC_PART") "C473048")
        (field (name "MANUFACTURER") "FH")
      )
      (libsource (lib "eagle-import") (part "10K-1%0201"))
    )
    (comp (ref "R72")
      (value "100K 1%")
      (footprint "eagle-import:0201")
      (fields (field (name "PACKAGE") "0201") (field (name "LCSC_PART") "C270364"))
      (libsource (lib "eagle-import") (part "100K-1%0201"))
    )
    (comp (ref "R73")
      (value "10K 1%")
      (footprint "eagle-import:0201")
      (fields
        (field (name "PACKAGE") "0201")
        (field (name "HQ_PART") "RE0208620")
        (field (name "LCSC_PART") "C473048")
        (field (name "MANUFACTURER") "FH")
      )
      (libsource (lib "eagle-import") (part "10K-1%0201"))
    )
    (comp (ref "R74")
      (value "100K 1%")
      (footprint "eagle-import:0201")
      (fields (field (name "PACKAGE") "0201") (field (name "LCSC_PART") "C270364"))
      (libsource (lib "eagle-import") (part "100K-1%0201"))
    )
    (comp (ref "R75")
      (value "10K 1%")
      (footprint "eagle-import:0201")
      (fields
        (field (name "PACKAGE") "0201")
        (field (name "HQ_PART") "RE0208620")
        (field (name "LCSC_PART") "C473048")
        (field (name "MANUFACTURER") "FH")
      )
      (libsource (lib "eagle-import") (part "10K-1%0201"))
    )
    (comp (ref "AVDD")
      (value "DNI")
      (footprint "eagle-import:TP-ROUND")
      (libsource (lib "eagle-import") (part "TP-ROUND"))
    )
    (comp (ref "C1")
      (value "100nF 25V")
      (footprint "eagle-import:0201")
      (fields
        (field (name "PACKAGE") "0201")
        (field (name "HQ_PART") "CA0183221")
        (field (name "LCSC_PART") "C76939")
        (field (name "MANUFACTURER") "Samsung")
      )
      (libsource (lib "eagle-import") (part "100NF-25V-0201"))
    )
    (comp (ref "C7")
      (value "100nF 25V")
      (footprint "eagle-import:0201")
      (fields
        (field (name "PACKAGE") "0201")
        (field (name "HQ_PART") "CA0183221")
        (field (name "LCSC_PART") "C76939")
        (field (name "MANUFACTURER") "Samsung")
      )
      (libsource (lib "eagle-import") (part "100NF-25V-0201"))
    )
    (comp (ref "C8")
      (value "100nF 25V")
      (footprint "eagle-import:0201")
      (fields
        (field (name "PACKAGE") "0201")
        (field (name "HQ_PART") "CA0183221")
        (field (name "LCSC_PART") "C76939")
        (field (name "MANUFACTURER") "Samsung")
      )
      (libsource (lib "eagle-import") (part "100NF-25V-0201"))
    )
    (comp (ref "C9")
      (value "100nF 25V")
      (footprint "eagle-import:0201")
      (fields
        (field (name "PACKAGE") "0201")
        (field (name "HQ_PART") "CA0183221")
        (field (name "LCSC_PART") "C76939")
        (field (name "MANUFACTURER") "Samsung")
      )
      (libsource (lib "eagle-import") (part "100NF-25V-0201"))
    )
    (comp (ref "C10")
      (value "100nF 25V")
      (footprint "eagle-import:0201")
      (fields
        (field (name "PACKAGE") "0201")
        (field (name "HQ_PART") "CA0183221")
        (field (name "LCSC_PART") "C76939")
        (field (name "MANUFACTURER") "Samsung")
      )
      (libsource (lib "eagle-import") (part "100NF-25V-0201"))
    )
    (comp (ref "C12")
      (value "100nF 25V")
      (footprint "eagle-import:0201")
      (fields
        (field (name "PACKAGE") "0201")
        (field (name "HQ_PART") "CA0183221")
        (field (name "LCSC_PART") "C76939")
        (field (name "MANUFACTURER") "Samsung")
      )
      (libsource (lib "eagle-import") (part "100NF-25V-0201"))
    )
    (comp (ref "C13")
      (value "100nF 25V")
      (footprint "eagle-import:0201")
      (fields
        (field (name "PACKAGE") "0201")
        (field (name "HQ_PART") "CA0183221")
        (field (name "LCSC_PART") "C76939")
        (field (name "MANUFACTURER") "Samsung")
      )
      (libsource (lib "eagle-import") (part "100NF-25V-0201"))
    )
    (comp (ref "C14")
      (value "100nF 25V")
      (footprint "eagle-import:0201")
      (fields
        (field (name "PACKAGE") "0201")
        (field (name "HQ_PART") "CA0183221")
        (field (name "LCSC_PART") "C76939")
        (field (name "MANUFACTURER") "Samsung")
      )
      (libsource (lib "eagle-import") (part "100NF-25V-0201"))
    )
    (comp (ref "C15")
      (value "100nF 25V")
      (footprint "eagle-import:0201")
      (fields
        (field (name "PACKAGE") "0201")
        (field (name "HQ_PART") "CA0183221")
        (field (name "LCSC_PART") "C76939")
        (field (name "MANUFACTURER") "Samsung")
      )
      (libsource (lib "eagle-import") (part "100NF-25V-0201"))
    )
    (comp (ref "C19")
      (value "100nF 25V")
      (footprint "eagle-import:0201")
      (fields
        (field (name "PACKAGE") "0201")
        (field (name "HQ_PART") "CA0183221")
        (field (name "LCSC_PART") "C76939")
        (field (name "MANUFACTURER") "Samsung")
      )
      (libsource (lib "eagle-import") (part "100NF-25V-0201"))
    )
    (comp (ref "C20")
      (value "100nF 25V")
      (footprint "eagle-import:0201")
      (fields
        (field (name "PACKAGE") "0201")
        (field (name "HQ_PART") "CA0183221")
        (field (name "LCSC_PART") "C76939")
        (field (name "MANUFACTURER") "Samsung")
      )
      (libsource (lib "eagle-import") (part "100NF-25V-0201"))
    )
    (comp (ref "C21")
      (value "4.7uF 25V")
      (footprint "eagle-import:0402")
      (fields
        (field (name "PACKAGE") "0402")
        (field (name "HQ_PART") "ZHLM0023346")
        (field (name "LCSC_PART") "C22367824")
        (field (name "MANUFACTURER") "Murata")
      )
      (libsource (lib "eagle-import") (part "4.7UF-25V0402"))
    )
    (comp (ref "C22")
      (value "4.7uF 25V")
      (footprint "eagle-import:0402")
      (fields
        (field (name "PACKAGE") "0402")
        (field (name "HQ_PART") "ZHLM0023346")
        (field (name "LCSC_PART") "C22367824")
        (field (name "MANUFACTURER") "Murata")
      )
      (libsource (lib "eagle-import") (part "4.7UF-25V0402"))
    )
    (comp (ref "C23")
      (value "100nF 25V")
      (footprint "eagle-import:0201")
      (fields
        (field (name "PACKAGE") "0201")
        (field (name "HQ_PART") "CA0183221")
        (field (name "LCSC_PART") "C76939")
        (field (name "MANUFACTURER") "Samsung")
      )
      (libsource (lib "eagle-import") (part "100NF-25V-0201"))
    )
    (comp (ref "C24")
      (value "100nF 25V")
      (footprint "eagle-import:0201")
      (fields
        (field (name "PACKAGE") "0201")
        (field (name "HQ_PART") "CA0183221")
        (field (name "LCSC_PART") "C76939")
        (field (name "MANUFACTURER") "Samsung")
      )
      (libsource (lib "eagle-import") (part "100NF-25V-0201"))
    )
    (comp (ref "C25")
      (value "100nF 25V")
      (footprint "eagle-import:0201")
      (fields
        (field (name "PACKAGE") "0201")
        (field (name "HQ_PART") "CA0183221")
        (field (name "LCSC_PART") "C76939")
        (field (name "MANUFACTURER") "Samsung")
      )
      (libsource (lib "eagle-import") (part "100NF-25V-0201"))
    )
    (comp (ref "C26")
      (value "4.7uF 25V")
      (footprint "eagle-import:0402")
      (fields
        (field (name "PACKAGE") "0402")
        (field (name "HQ_PART") "ZHLM0023346")
        (field (name "LCSC_PART") "C22367824")
        (field (name "MANUFACTURER") "Murata")
      )
      (libsource (lib "eagle-import") (part "4.7UF-25V0402"))
    )
    (comp (ref "C27")
      (value "100nF 25V")
      (footprint "eagle-import:0201")
      (fields
        (field (name "PACKAGE") "0201")
        (field (name "HQ_PART") "CA0183221")
        (field (name "LCSC_PART") "C76939")
        (field (name "MANUFACTURER") "Samsung")
      )
      (libsource (lib "eagle-import") (part "100NF-25V-0201"))
    )
    (comp (ref "C56")
      (value "100nF 25V")
      (footprint "eagle-import:0201")
      (fields
        (field (name "PACKAGE") "0201")
        (field (name "HQ_PART") "CA0183221")
        (field (name "LCSC_PART") "C76939")
        (field (name "MANUFACTURER") "Samsung")
      )
      (libsource (lib "eagle-import") (part "100NF-25V-0201"))
    )
    (comp (ref "C57")
      (value "100nF 25V")
      (footprint "eagle-import:0201")
      (fields
        (field (name "PACKAGE") "0201")
        (field (name "HQ_PART") "CA0183221")
        (field (name "LCSC_PART") "C76939")
        (field (name "MANUFACTURER") "Samsung")
      )
      (libsource (lib "eagle-import") (part "100NF-25V-0201"))
    )
    (comp (ref "C58")
      (value "100nF 25V")
      (footprint "eagle-import:0201")
      (fields
        (field (name "PACKAGE") "0201")
        (field (name "HQ_PART") "CA0183221")
        (field (name "LCSC_PART") "C76939")
        (field (name "MANUFACTURER") "Samsung")
      )
      (libsource (lib "eagle-import") (part "100NF-25V-0201"))
    )
    (comp (ref "C59")
      (value "100nF 25V")
      (footprint "eagle-import:0201")
      (fields
        (field (name "PACKAGE") "0201")
        (field (name "HQ_PART") "CA0183221")
        (field (name "LCSC_PART") "C76939")
        (field (name "MANUFACTURER") "Samsung")
      )
      (libsource (lib "eagle-import") (part "100NF-25V-0201"))
    )
    (comp (ref "C60")
      (value "100nF 25V")
      (footprint "eagle-import:0201")
      (fields
        (field (name "PACKAGE") "0201")
        (field (name "HQ_PART") "CA0183221")
        (field (name "LCSC_PART") "C76939")
        (field (name "MANUFACTURER") "Samsung")
      )
      (libsource (lib "eagle-import") (part "100NF-25V-0201"))
    )
    (comp (ref "C61")
      (value "100nF 25V")
      (footprint "eagle-import:0201")
      (fields
        (field (name "PACKAGE") "0201")
        (field (name "HQ_PART") "CA0183221")
        (field (name "LCSC_PART") "C76939")
        (field (name "MANUFACTURER") "Samsung")
      )
      (libsource (lib "eagle-import") (part "100NF-25V-0201"))
    )
    (comp (ref "C62")
      (value "15pF 50V")
      (footprint "eagle-import:0201")
      (fields
        (field (name "PACKAGE") "0201")
        (field (name "HQ_PART") "CA0136888")
        (field (name "LCSC_PART") "C22374851")
        (field (name "MANUFACTURER") "Yageo")
      )
      (libsource (lib "eagle-import") (part "15PF-50V0201"))
    )
    (comp (ref "C63")
      (value "15pF 50V")
      (footprint "eagle-import:0201")
      (fields
        (field (name "PACKAGE") "0201")
        (field (name "HQ_PART") "CA0136888")
        (field (name "LCSC_PART") "C22374851")
        (field (name "MANUFACTURER") "Yageo")
      )
      (libsource (lib "eagle-import") (part "15PF-50V0201"))
    )
    (comp (ref "C64")
      (value "4.7uF 25V")
      (footprint "eagle-import:0402")
      (fields
        (field (name "PACKAGE") "0402")
        (field (name "HQ_PART") "ZHLM0023346")
        (field (name "LCSC_PART") "C22367824")
        (field (name "MANUFACTURER") "Murata")
      )
      (libsource (lib "eagle-import") (part "4.7UF-25V0402"))
    )
    (comp (ref "IC26")
      (value "RP2354B")
      (footprint "eagle-import:QFN80-10X10")
      (fields (field (name "LCSC_PART") "C39843328") (field (name "MANUFACTURER") "Raspberry Pi "))
      (libsource (lib "eagle-import") (part "RP235XB"))
    )
    (comp (ref "IC27")
      (value "W25Q128JVPIQ")
      (footprint "eagle-import:SON127P600X500X75-8N")
      (fields
        (field (name "HQ_PART") "IC0150933")
        (field (name "LCSC_PART") "C190862")
        (field (name "MANUFACTURER") "Winbond")
      )
      (libsource (lib "eagle-import") (part "W25Q128JVP"))
    )
    (comp (ref "IC28")
      (value "MCP6001RT-I/OT")
      (footprint "eagle-import:SOT23-5")
      (fields
        (field (name "HQ_PART") "IC0119727")
        (field (name "LCSC_PART") "C154973")
        (field (name "MANUFACTURER") "MICROCHIP")
      )
      (libsource (lib "eagle-import") (part "MCP6001RT"))
    )
    (comp (ref "IC39")
      (value "W25Q128JVPIQ")
      (footprint "eagle-import:SON127P600X500X75-8N")
      (fields
        (field (name "HQ_PART") "IC0150933")
        (field (name "LCSC_PART") "C190862")
        (field (name "MANUFACTURER") "Winbond")
      )
      (libsource (lib "eagle-import") (part "W25Q128JVP"))
    )
    (comp (ref "L1")
      (value "3.3uH")
      (footprint "eagle-import:0805")
      (fields
        (field (name "HQ_PART") "IN47489734")
        (field (name "LCSC_PART") "C42411119")
        (field (name "MANUFACTURER") "Abracon LLC")
      )
      (libsource (lib "eagle-import") (part "3.3UH0805"))
    )
    (comp (ref "R6")
      (value "1K 1%")
      (footprint "eagle-import:0201")
      (fields
        (field (name "PACKAGE") "0201")
        (field (name "HQ_PART") "RE0015967")
        (field (name "LCSC_PART") "C270365")
        (field (name "MANUFACTURER") "Yageo")
      )
      (libsource (lib "eagle-import") (part "1K-1%0201"))
    )
    (comp (ref "R7")
      (value "1K 1%")
      (footprint "eagle-import:0201")
      (fields
        (field (name "PACKAGE") "0201")
        (field (name "HQ_PART") "RE0015967")
        (field (name "LCSC_PART") "C270365")
        (field (name "MANUFACTURER") "Yageo")
      )
      (libsource (lib "eagle-import") (part "1K-1%0201"))
    )
    (comp (ref "R8")
      (value "DNI")
      (footprint "eagle-import:R0201")
      (libsource (lib "eagle-import") (part "R0201"))
    )
    (comp (ref "R24")
      (value "10K 1%")
      (footprint "eagle-import:0201")
      (fields
        (field (name "PACKAGE") "0201")
        (field (name "HQ_PART") "RE0208620")
        (field (name "LCSC_PART") "C473048")
        (field (name "MANUFACTURER") "FH")
      )
      (libsource (lib "eagle-import") (part "10K-1%0201"))
    )
    (comp (ref "R25")
      (value "27R 1%")
      (footprint "eagle-import:0201")
      (fields
        (field (name "PACKAGE") "0201")
        (field (name "HQ_PART") "RE0209327 ")
        (field (name "LCSC_PART") "C473051")
        (field (name "MANUFACTURER") "FH")
      )
      (libsource (lib "eagle-import") (part "27R-1%0201"))
    )
    (comp (ref "R26")
      (value "27R 1%")
      (footprint "eagle-import:0201")
      (fields
        (field (name "PACKAGE") "0201")
        (field (name "HQ_PART") "RE0209327 ")
        (field (name "LCSC_PART") "C473051")
        (field (name "MANUFACTURER") "FH")
      )
      (libsource (lib "eagle-import") (part "27R-1%0201"))
    )
    (comp (ref "R27")
      (value "33R 1%")
      (footprint "eagle-import:0402")
      (fields
        (field (name "PACKAGE") "0402")
        (field (name "HQ_PART") "RE0368295")
        (field (name "LCSC_PART") "C25105")
        (field (name "MANUFACTURER") "ROHM")
      )
      (libsource (lib "eagle-import") (part "33R-1%0402"))
    )
    (comp (ref "R28")
      (value "0R 1%")
      (footprint "eagle-import:0402")
      (fields
        (field (name "PACKAGE") "0402")
        (field (name "HQ_PART") "RE0250181")
        (field (name "LCSC_PART") "C17168")
        (field (name "MANUFACTURER") "YAGEO")
      )
      (libsource (lib "eagle-import") (part "0R0402"))
    )
    (comp (ref "R29")
      (value "0R 1%")
      (footprint "eagle-import:0402")
      (fields
        (field (name "PACKAGE") "0402")
        (field (name "HQ_PART") "RE0250181")
        (field (name "LCSC_PART") "C17168")
        (field (name "MANUFACTURER") "YAGEO")
      )
      (libsource (lib "eagle-import") (part "0R0402"))
    )
    (comp (ref "R209")
      (value "DNI")
      (footprint "eagle-import:R0201")
      (libsource (lib "eagle-import") (part "R0201"))
    )
    (comp (ref "R212")
      (value "4.7K 1%")
      (footprint "eagle-import:0201")
      (fields
        (field (name "HQ_PART") "RE0208670")
        (field (name "LCSC_PART") "C270346")
        (field (name "MANUFACTURER") "RALEC")
      )
      (libsource (lib "eagle-import") (part "4.7K-1%0201"))
    )
    (comp (ref "R278")
      (value "DNI")
      (footprint "eagle-import:R0201")
      (libsource (lib "eagle-import") (part "R0201"))
    )
    (comp (ref "REF1")
      (value "LM4040x30")
      (footprint "eagle-import:SOT23")
      (fields
        (field (name "HQ_PART") "IC0022950")
        (field (name "LCSC_PART") "C460604")
        (field (name "MANUFACTURER") "DIODES")
      )
      (libsource (lib "eagle-import") (part "LM4040BXX"))
    )
    (comp (ref "SW1")
      (value "B3U-1000P")
      (footprint "eagle-import:B3U-1000P")
      (fields
        (field (name "HQ_PART") "SW0036094 ")
        (field (name "LCSC_PART") "C231329")
        (field (name "MANUFACTURER") "Omron")
      )
      (libsource (lib "eagle-import") (part "B3U-1000P"))
    )
    (comp (ref "SW2")
      (value "B3U-1000P")
      (footprint "eagle-import:B3U-1000P")
      (fields
        (field (name "HQ_PART") "SW0036094 ")
        (field (name "LCSC_PART") "C231329")
        (field (name "MANUFACTURER") "Omron")
      )
      (libsource (lib "eagle-import") (part "B3U-1000P"))
    )
    (comp (ref "VREF")
      (value "DNI")
      (footprint "eagle-import:TP-ROUND")
      (libsource (lib "eagle-import") (part "TP-ROUND"))
    )
    (comp (ref "X1")
      (value "12MHz")
      (footprint "eagle-import:WE-XTAL_CFPX-180")
      (fields
        (field (name "HQ_PART") "CR0250194")
        (field (name "LCSC_PART") "C20625731")
        (field (name "MANUFACTURER") "TKD")
      )
      (libsource (lib "eagle-import") (part "CRYSTAL-3225X322512MSB4SI"))
    )
    (comp (ref "ADVB")
      (value "DNI")
      (footprint "eagle-import:TP-ROUND")
      (libsource (lib "eagle-import") (part "TP-ROUND"))
    )
    (comp (ref "C28")
      (value "1nF 2kV")
      (footprint "eagle-import:1206")
      (fields
        (field (name "HQ_PART") "CA0134884")
        (field (name "LCSC_PART") "C173242")
        (field (name "MANUFACTURER") "Johanson Dielectrics ")
      )
      (libsource (lib "eagle-import") (part "1NF-2KV"))
    )
    (comp (ref "C29")
      (value "100nF 25V")
      (footprint "eagle-import:0201")
      (fields
        (field (name "PACKAGE") "0201")
        (field (name "HQ_PART") "CA0183221")
        (field (name "LCSC_PART") "C76939")
        (field (name "MANUFACTURER") "Samsung")
      )
      (libsource (lib "eagle-import") (part "100NF-25V-0201"))
    )
    (comp (ref "C66")
      (value "100nF 25V")
      (footprint "eagle-import:0201")
      (fields
        (field (name "PACKAGE") "0201")
        (field (name "HQ_PART") "CA0183221")
        (field (name "LCSC_PART") "C76939")
        (field (name "MANUFACTURER") "Samsung")
      )
      (libsource (lib "eagle-import") (part "100NF-25V-0201"))
    )
    (comp (ref "C67")
      (value "4.7uF 25V")
      (footprint "eagle-import:0402")
      (fields
        (field (name "PACKAGE") "0402")
        (field (name "HQ_PART") "ZHLM0023346")
        (field (name "LCSC_PART") "C22367824")
        (field (name "MANUFACTURER") "Murata")
      )
      (libsource (lib "eagle-import") (part "4.7UF-25V0402"))
    )
    (comp (ref "C68")
      (value "4.7uF 25V")
      (footprint "eagle-import:0402")
      (fields
        (field (name "PACKAGE") "0402")
        (field (name "HQ_PART") "ZHLM0023346")
        (field (name "LCSC_PART") "C22367824")
        (field (name "MANUFACTURER") "Murata")
      )
      (libsource (lib "eagle-import") (part "4.7UF-25V0402"))
    )
    (comp (ref "C69")
      (value "100nF 25V")
      (footprint "eagle-import:0201")
      (fields
        (field (name "PACKAGE") "0201")
        (field (name "HQ_PART") "CA0183221")
        (field (name "LCSC_PART") "C76939")
        (field (name "MANUFACTURER") "Samsung")
      )
      (libsource (lib "eagle-import") (part "100NF-25V-0201"))
    )
    (comp (ref "C70")
      (value "4.7uF 25V")
      (footprint "eagle-import:0402")
      (fields
        (field (name "PACKAGE") "0402")
        (field (name "HQ_PART") "ZHLM0023346")
        (field (name "LCSC_PART") "C22367824")
        (field (name "MANUFACTURER") "Murata")
      )
      (libsource (lib "eagle-import") (part "4.7UF-25V0402"))
    )
    (comp (ref "D13")
      (value "HDMIULC6-4SC6Y")
      (footprint "eagle-import:SOT23-6")
      (libsource (lib "eagle-import") (part "HDMIULC6-4SC6Y"))
    )
    (comp (ref "DISP")
      (value "AFC11-S20ICC-00")
      (footprint "eagle-import:FPC20")
      (fields
        (field (name "HQ_PART") "CO0889517")
        (field (name "LCSC_PART") "C466537")
        (field (name "MANUFACTURER") "JS")
      )
      (libsource (lib "eagle-import") (part "AFC11-S20ICC-00"))
    )
    (comp (ref "ESD1")
      (value "SP0503BAHTG")
      (footprint "eagle-import:SOT143")
      (fields
        (field (name "HQ_PART") "CP0003989")
        (field (name "LCSC_PART") "C3040626")
        (field (name "MANUFACTURER") "Littelfuse")
      )
      (libsource (lib "eagle-import") (part "SP0503BAHT"))
    )
    (comp (ref "IC38")
      (value "TCA9548ARGER")
      (footprint "eagle-import:QFN50P400X400X100-25T210N")
      (libsource (lib "eagle-import") (part "TCA9548ARGER"))
    )
    (comp (ref "R10")
      (value "1M 1%")
      (footprint "eagle-import:1206")
      (fields
        (field (name "PACKAGE") "1206")
        (field (name "HQ_PART") "RE0188103")
        (field (name "LCSC_PART") "C17927")
        (field (name "MANUFACTURER") "Uniohm")
      )
      (libsource (lib "eagle-import") (part "1M-1%1206"))
    )
    (comp (ref "R18")
      (value "5.1K 1%")
      (footprint "eagle-import:0201")
      (fields
        (field (name "PACKAGE") "0201")
        (field (name "HQ_PART") "RE0185972")
        (field (name "LCSC_PART") "C274341")
        (field (name "MANUFACTURER") "Yageo")
      )
      (libsource (lib "eagle-import") (part "5.1K-1%0201"))
    )
    (comp (ref "R19")
      (value "5.1K 1%")
      (footprint "eagle-import:0201")
      (fields
        (field (name "PACKAGE") "0201")
        (field (name "HQ_PART") "RE0185972")
        (field (name "LCSC_PART") "C274341")
        (field (name "MANUFACTURER") "Yageo")
      )
      (libsource (lib "eagle-import") (part "5.1K-1%0201"))
    )
    (comp (ref "R20")
      (value "2.2K 1%")
      (footprint "eagle-import:0201")
      (fields
        (field (name "PACKAGE") "0201")
        (field (name "HQ_PART") "RE0209901")
        (field (name "LCSC_PART") "C473508")
        (field (name "MANUFACTURER") "FH")
      )
      (libsource (lib "eagle-import") (part "2.2K-1%0201"))
    )
    (comp (ref "R21")
      (value "10K 1%")
      (footprint "eagle-import:0201")
      (fields
        (field (name "PACKAGE") "0201")
        (field (name "HQ_PART") "RE0208620")
        (field (name "LCSC_PART") "C473048")
        (field (name "MANUFACTURER") "FH")
      )
      (libsource (lib "eagle-import") (part "10K-1%0201"))
    )
    (comp (ref "R30")
      (value "0R 1%")
      (footprint "eagle-import:0805")
      (fields
        (field (name "PACKAGE") "0805")
        (field (name "HQ_PART") "RE0013023")
        (field (name "LCSC_PART") "C17477")
        (field (name "MANUFACTURER") "Vishay")
      )
      (libsource (lib "eagle-import") (part "0R0805"))
    )
    (comp (ref "R31")
      (value "10K 1%")
      (footprint "eagle-import:0402")
      (fields
        (field (name "PACKAGE") "0402")
        (field (name "HQ_PART") "RE0207399")
        (field (name "LCSC_PART") "C25744")
        (field (name "MANUFACTURER") "ROHM")
      )
      (libsource (lib "eagle-import") (part "10K-1%0402"))
    )
    (comp (ref "R32")
      (value "10K 1%")
      (footprint "eagle-import:0402")
      (fields
        (field (name "PACKAGE") "0402")
        (field (name "HQ_PART") "RE0207399")
        (field (name "LCSC_PART") "C25744")
        (field (name "MANUFACTURER") "ROHM")
      )
      (libsource (lib "eagle-import") (part "10K-1%0402"))
    )
    (comp (ref "R35")
      (value "3.3K 1%")
      (footprint "eagle-import:_0603X4-1206")
      (fields
        (field (name "HQ_PART") "RE0093863")
        (field (name "LCSC_PART") "C1734380")
        (field (name "MANUFACTURER") "Yageo")
      )
      (libsource (lib "eagle-import") (part "3.3K-1%_ARRAY0603X4-1206"))
    )
    (comp (ref "R215")
      (value "3.3K 1%")
      (footprint "eagle-import:_0603X4-1206")
      (fields
        (field (name "HQ_PART") "RE0093863")
        (field (name "LCSC_PART") "C1734380")
        (field (name "MANUFACTURER") "Yageo")
      )
      (libsource (lib "eagle-import") (part "3.3K-1%_ARRAY0603X4-1206"))
    )
    (comp (ref "R216")
      (value "3.3K 1%")
      (footprint "eagle-import:_0603X4-1206")
      (fields
        (field (name "HQ_PART") "RE0093863")
        (field (name "LCSC_PART") "C1734380")
        (field (name "MANUFACTURER") "Yageo")
      )
      (libsource (lib "eagle-import") (part "3.3K-1%_ARRAY0603X4-1206"))
    )
    (comp (ref "R217")
      (value "3.3K 1%")
      (footprint "eagle-import:_0603X4-1206")
      (fields
        (field (name "HQ_PART") "RE0093863")
        (field (name "LCSC_PART") "C1734380")
        (field (name "MANUFACTURER") "Yageo")
      )
      (libsource (lib "eagle-import") (part "3.3K-1%_ARRAY0603X4-1206"))
    )
    (comp (ref "TP2")
      (value "DNI")
      (footprint "eagle-import:TP-ROUND")
      (libsource (lib "eagle-import") (part "TP-ROUND"))
    )
    (comp (ref "USB9")
      (value "USB-TYPE-C-018")
      (footprint "eagle-import:USB-C")
      (fields
        (field (name "HQ_PART") "ZHLM0322915")
        (field (name "LCSC_PART") "C2927038")
        (field (name "MANUFACTURER") "DEALON")
      )
      (libsource (lib "eagle-import") (part "USB_C-THT"))
    )
    (comp (ref "C65")
      (value "100nF 25V")
      (footprint "eagle-import:0201")
      (fields
        (field (name "PACKAGE") "0201")
        (field (name "HQ_PART") "CA0183221")
        (field (name "LCSC_PART") "C76939")
        (field (name "MANUFACTURER") "Samsung")
      )
      (libsource (lib "eagle-import") (part "100NF-25V-0201"))
    )
    (comp (ref "D12")
      (value "HDMIULC6-4SC6Y")
      (footprint "eagle-import:SOT23-6")
      (libsource (lib "eagle-import") (part "HDMIULC6-4SC6Y"))
    )
    (comp (ref "IC29")
      (value "CAT24C256HU4IGT3")
      (footprint "eagle-import:SON50P300X200X50-9T130X140N")
      (fields
        (field (name "HQ_PART") "IC0066897")
        (field (name "LCSC_PART") "C233771")
        (field (name "MANUFACTURER") "ON")
      )
      (libsource (lib "eagle-import") (part "CAT24C256-HU4"))
    )
    (comp (ref "JTAG")
      (value "3220_10_0300_00")
      (footprint "eagle-import:3220_10_0300_00")
      (fields
        (field (name "LCSC_PART") "C598547")
        (field (name "MANUFACTURER") "Amphenol ICC ")
        (field (name "MPN") "20021521-00010C1LF")
      )
      (libsource (lib "eagle-import") (part "3220_10_0300_00"))
    )
    (comp (ref "R9")
      (value "4.7K 1%")
      (footprint "eagle-import:0201")
      (fields
        (field (name "PACKAGE") "0201")
        (field (name "HQ_PART") "RE0208670")
        (field (name "LCSC_PART") "C270346")
        (field (name "MANUFACTURER") "RALEC")
      )
      (libsource (lib "eagle-import") (part "4.7K-1%0201"))
    )
    (comp (ref "R213")
      (value "NC")
      (footprint "eagle-import:R0201")
      (libsource (lib "eagle-import") (part "R0201"))
    )
    (comp (ref "RN1")
      (value "3.3K 1%")
      (footprint "eagle-import:_0603X4-1206")
      (fields
        (field (name "HQ_PART") "RE0093863")
        (field (name "LCSC_PART") "C1734380")
        (field (name "MANUFACTURER") "Yageo")
      )
      (libsource (lib "eagle-import") (part "3.3K-1%_ARRAY0603X4-1206"))
    )
    (comp (ref "TCC0")
      (value "DNI")
      (footprint "eagle-import:TP-ROUND")
      (libsource (lib "eagle-import") (part "TP-ROUND"))
    )
    (comp (ref "TCC1")
      (value "DNI")
      (footprint "eagle-import:TP-ROUND")
      (libsource (lib "eagle-import") (part "TP-ROUND"))
    )
    (comp (ref "TCC2")
      (value "DNI")
      (footprint "eagle-import:TP-ROUND")
      (libsource (lib "eagle-import") (part "TP-ROUND"))
    )
    (comp (ref "TCC3")
      (value "DNI")
      (footprint "eagle-import:TP-ROUND")
      (libsource (lib "eagle-import") (part "TP-ROUND"))
    )
    (comp (ref "TCC4")
      (value "DNI")
      (footprint "eagle-import:TP-ROUND")
      (libsource (lib "eagle-import") (part "TP-ROUND"))
    )
    (comp (ref "TCC5")
      (value "DNI")
      (footprint "eagle-import:TP-ROUND")
      (libsource (lib "eagle-import") (part "TP-ROUND"))
    )
    (comp (ref "TCC6")
      (value "DNI")
      (footprint "eagle-import:TP-ROUND")
      (libsource (lib "eagle-import") (part "TP-ROUND"))
    )
    (comp (ref "TCC7")
      (value "DNI")
      (footprint "eagle-import:TP-ROUND")
      (libsource (lib "eagle-import") (part "TP-ROUND"))
    )
    (comp (ref "TCD0")
      (value "DNI")
      (footprint "eagle-import:TP-ROUND")
      (libsource (lib "eagle-import") (part "TP-ROUND"))
    )
    (comp (ref "TCD1")
      (value "DNI")
      (footprint "eagle-import:TP-ROUND")
      (libsource (lib "eagle-import") (part "TP-ROUND"))
    )
    (comp (ref "TCD2")
      (value "DNI")
      (footprint "eagle-import:TP-ROUND")
      (libsource (lib "eagle-import") (part "TP-ROUND"))
    )
    (comp (ref "TCD3")
      (value "DNI")
      (footprint "eagle-import:TP-ROUND")
      (libsource (lib "eagle-import") (part "TP-ROUND"))
    )
    (comp (ref "TCD4")
      (value "DNI")
      (footprint "eagle-import:TP-ROUND")
      (libsource (lib "eagle-import") (part "TP-ROUND"))
    )
    (comp (ref "TCD5")
      (value "DNI")
      (footprint "eagle-import:TP-ROUND")
      (libsource (lib "eagle-import") (part "TP-ROUND"))
    )
    (comp (ref "TCD6")
      (value "DNI")
      (footprint "eagle-import:TP-ROUND")
      (libsource (lib "eagle-import") (part "TP-ROUND"))
    )
    (comp (ref "TCD7")
      (value "DNI")
      (footprint "eagle-import:TP-ROUND")
      (libsource (lib "eagle-import") (part "TP-ROUND"))
    )
  )
  (nets
    (net (code "1") (name "+1V1") (class "Default")
      (node (ref "C26") (pin "1") (pinfunction "1_1") (pintype "passive"))
      (node (ref "C58") (pin "1") (pinfunction "1_1") (pintype "passive"))
      (node (ref "C59") (pin "1") (pinfunction "1_1") (pintype "passive"))
      (node (ref "C60") (pin "1") (pinfunction "1_1") (pintype "passive"))
      (node (ref "C61") (pin "1") (pinfunction "1_1") (pintype "passive"))
      (node (ref "IC26") (pin "10") (pinfunction "DVDD1_10") (pintype "power_in"))
      (node (ref "IC26") (pin "32") (pinfunction "DVDD2_32") (pintype "power_in"))
      (node (ref "IC26") (pin "51") (pinfunction "DVDD3_51") (pintype "power_in"))
      (node (ref "IC26") (pin "65") (pinfunction "VREG_FB_65") (pintype "input"))
      (node (ref "IC26") (pin "68") (pinfunction "USB_OTP_VDD_68") (pintype "power_in"))
      (node (ref "IC26") (pin "69") (pinfunction "QSPI_IOVDD_69") (pintype "power_in"))
      (node (ref "L1") (pin "2") (pinfunction "2_2") (pintype "passive"))
    )
    (net (code "2") (name "+3V3") (class "Default")
      (node (ref "+3V") (pin "TP") (pinfunction "P$1_TP") (pintype "bidirectional"))
      (node (ref "C1") (pin "1") (pinfunction "1_1") (pintype "passive"))
      (node (ref "C10") (pin "1") (pinfunction "1_1") (pintype "passive"))
      (node (ref "C121") (pin "1") (pinfunction "1_1") (pintype "passive"))
      (node (ref "C13") (pin "1") (pinfunction "1_1") (pintype "passive"))
      (node (ref "C14") (pin "1") (pinfunction "1_1") (pintype "passive"))
      (node (ref "C15") (pin "1") (pinfunction "1_1") (pintype "passive"))
      (node (ref "C18") (pin "1") (pinfunction "1_1") (pintype "passive"))
      (node (ref "C19") (pin "1") (pinfunction "1_1") (pintype "passive"))
      (node (ref "C20") (pin "1") (pinfunction "1_1") (pintype "passive"))
      (node (ref "C22") (pin "1") (pinfunction "1_1") (pintype "passive"))
      (node (ref "C23") (pin "1") (pinfunction "1_1") (pintype "passive"))
      (node (ref "C24") (pin "1") (pinfunction "1_1") (pintype "passive"))
      (node (ref "C25") (pin "1") (pinfunction "1_1") (pintype "passive"))
      (node (ref "C27") (pin "1") (pinfunction "1_1") (pintype "passive"))
      (node (ref "C31") (pin "1") (pinfunction "1_1") (pintype "passive"))
      (node (ref "C33") (pin "1") (pinfunction "1_1") (pintype "passive"))
      (node (ref "C36") (pin "1") (pinfunction "1_1") (pintype "passive"))
      (node (ref "C55") (pin "1") (pinfunction "1_1") (pintype "passive"))
      (node (ref "C56") (pin "1") (pinfunction "1_1") (pintype "passive"))
      (node (ref "C57") (pin "1") (pinfunction "1_1") (pintype "passive"))
      (node (ref "C65") (pin "1") (pinfunction "1_1") (pintype "passive"))
      (node (ref "C69") (pin "1") (pinfunction "1_1") (pintype "passive"))
      (node (ref "C70") (pin "1") (pinfunction "1_1") (pintype "passive"))
      (node (ref "C76") (pin "1") (pinfunction "1_1") (pintype "passive"))
      (node (ref "C9") (pin "1") (pinfunction "1_1") (pintype "passive"))
      (node (ref "C97") (pin "1") (pinfunction "1_1") (pintype "passive"))
      (node (ref "C98") (pin "1") (pinfunction "1_1") (pintype "passive"))
      (node (ref "D1") (pin "A") (pinfunction "A_A") (pintype "passive"))
      (node (ref "D12") (pin "5") (pinfunction "5_5") (pintype "power_in"))
      (node (ref "D13") (pin "5") (pinfunction "5_5") (pintype "power_in"))
      (node (ref "D3") (pin "A") (pinfunction "A_A") (pintype "passive"))
      (node (ref "DISP") (pin "1") (pinfunction "1_1") (pintype "bidirectional"))
      (node (ref "DISP") (pin "2") (pinfunction "2_2") (pintype "bidirectional"))
      (node (ref "ETH2") (pin "10") (pinfunction "GREEN+_10") (pintype "passive"))
      (node (ref "ETH2") (pin "12") (pinfunction "YELLOW+_12") (pintype "passive"))
      (node (ref "IC13") (pin "4") (pinfunction "VCC_4") (pintype "bidirectional"))
      (node (ref "IC17") (pin "28") (pinfunction "VDD_28") (pintype "power_in"))
      (node (ref "IC17") (pin "43") (pinfunction "PMODE2_43") (pintype "input"))
      (node (ref "IC17") (pin "44") (pinfunction "PMODE1_44") (pintype "input"))
      (node (ref "IC17") (pin "45") (pinfunction "PMODE0_45") (pintype "input"))
      (node (ref "IC26") (pin "15") (pinfunction "IOVDD2_15") (pintype "power_in"))
      (node (ref "IC26") (pin "24") (pinfunction "IOVDD3_24") (pintype "power_in"))
      (node (ref "IC26") (pin "29") (pinfunction "IOVDD4_29") (pintype "power_in"))
      (node (ref "IC26") (pin "41") (pinfunction "IOVDD5_41") (pintype "power_in"))
      (node (ref "IC26") (pin "5") (pinfunction "IOVDD1_5") (pintype "power_in"))
      (node (ref "IC26") (pin "50") (pinfunction "IOVDD6_50") (pintype "power_in"))
      (node (ref "IC26") (pin "60") (pinfunction "IOVDD7_60") (pintype "power_in"))
      (node (ref "IC26") (pin "64") (pinfunction "VREG_IN_64") (pintype "power_in"))
      (node (ref "IC26") (pin "76") (pinfunction "IOVDD8_76") (pintype "power_in"))
      (node (ref "IC27") (pin "8") (pinfunction "VCC_8") (pintype "power_in"))
      (node (ref "IC28") (pin "2") (pinfunction "V+_2") (pintype "power_in"))
      (node (ref "IC29") (pin "8") (pinfunction "VCC_8") (pintype "power_in"))
      (node (ref "IC38") (pin "21") (pinfunction "VCC_21") (pintype "power_in"))
      (node (ref "IC39") (pin "8") (pinfunction "VCC_8") (pintype "power_in"))
      (node (ref "IC4") (pin "5") (pinfunction "V+_5") (pintype "bidirectional"))
      (node (ref "IC5") (pin "5") (pinfunction "V+_5") (pintype "bidirectional"))
      (node (ref "JTAG") (pin "1") (pinfunction "1_1") (pintype "passive"))
      (node (ref "L11") (pin "2") (pinfunction "2_2") (pintype "passive"))
      (node (ref "L5") (pin "1") (pinfunction "1_1") (pintype "passive"))
      (node (ref "R13") (pin "1") (pinfunction "1_1") (pintype "passive"))
      (node (ref "R135") (pin "1") (pinfunction "1_1") (pintype "passive"))
      (node (ref "R209") (pin "2") (pinfunction "2_2") (pintype "passive"))
      (node (ref "R21") (pin "1") (pinfunction "1_1") (pintype "passive"))
      (node (ref "R212") (pin "2") (pinfunction "2_2") (pintype "passive"))
      (node (ref "R213") (pin "2") (pinfunction "2_2") (pintype "passive"))
      (node (ref "R215") (pin "A2") (pinfunction "8_A2") (pintype "passive"))
      (node (ref "R215") (pin "B2") (pinfunction "7_B2") (pintype "passive"))
      (node (ref "R215") (pin "C2") (pinfunction "6_C2") (pintype "passive"))
      (node (ref "R215") (pin "D2") (pinfunction "5_D2") (pintype "passive"))
      (node (ref "R216") (pin "A2") (pinfunction "8_A2") (pintype "passive"))
      (node (ref "R216") (pin "B2") (pinfunction "7_B2") (pintype "passive"))
      (node (ref "R216") (pin "C2") (pinfunction "6_C2") (pintype "passive"))
      (node (ref "R216") (pin "D2") (pinfunction "5_D2") (pintype "passive"))
      (node (ref "R217") (pin "A2") (pinfunction "8_A2") (pintype "passive"))
      (node (ref "R217") (pin "B2") (pinfunction "7_B2") (pintype "passive"))
      (node (ref "R217") (pin "C2") (pinfunction "6_C2") (pintype "passive"))
      (node (ref "R217") (pin "D2") (pinfunction "5_D2") (pintype "passive"))
      (node (ref "R226") (pin "2") (pinfunction "2_2") (pintype "passive"))
      (node (ref "R227") (pin "2") (pinfunction "2_2") (pintype "passive"))
      (node (ref "R23") (pin "1") (pinfunction "1_1") (pintype "passive"))
      (node (ref "R24") (pin "1") (pinfunction "1_1") (pintype "passive"))
      (node (ref "R27") (pin "1") (pinfunction "1_1") (pintype "passive"))
      (node (ref "R278") (pin "2") (pinfunction "2_2") (pintype "passive"))
      (node (ref "R29") (pin "1") (pinfunction "1_1") (pintype "passive"))
      (node (ref "R35") (pin "A2") (pinfunction "8_A2") (pintype "passive"))
      (node (ref "R35") (pin "B2") (pinfunction "7_B2") (pintype "passive"))
      (node (ref "R35") (pin "C2") (pinfunction "6_C2") (pintype "passive"))
      (node (ref "R35") (pin "D2") (pinfunction "5_D2") (pintype "passive"))
      (node (ref "R4") (pin "1") (pinfunction "1_1") (pintype "passive"))
      (node (ref "R8") (pin "2") (pinfunction "2_2") (pintype "passive"))
      (node (ref "RN1") (pin "A2") (pinfunction "8_A2") (pintype "passive"))
      (node (ref "RN1") (pin "B2") (pinfunction "7_B2") (pintype "passive"))
      (node (ref "RN1") (pin "C2") (pinfunction "6_C2") (pintype "passive"))
      (node (ref "RN1") (pin "D2") (pinfunction "5_D2") (pintype "passive"))
    )
    (net (code "3") (name "+3V3_A") (class "Default")
      (node (ref "3V3A1") (pin "TP") (pinfunction "P$1_TP") (pintype "bidirectional"))
      (node (ref "C122") (pin "1") (pinfunction "1_1") (pintype "passive"))
      (node (ref "C123") (pin "1") (pinfunction "1_1") (pintype "passive"))
      (node (ref "C124") (pin "1") (pinfunction "1_1") (pintype "passive"))
      (node (ref "C125") (pin "1") (pinfunction "1_1") (pintype "passive"))
      (node (ref "C126") (pin "1") (pinfunction "1_1") (pintype "passive"))
      (node (ref "C127") (pin "1") (pinfunction "1_1") (pintype "passive"))
      (node (ref "IC17") (pin "11") (pinfunction "AVDD_11") (pintype "power_in"))
      (node (ref "IC17") (pin "15") (pinfunction "AVDD_15") (pintype "power_in"))
      (node (ref "IC17") (pin "17") (pinfunction "AVDD_17") (pintype "power_in"))
      (node (ref "IC17") (pin "21") (pinfunction "AVDD_21") (pintype "power_in"))
      (node (ref "IC17") (pin "4") (pinfunction "AVDD_4") (pintype "power_in"))
      (node (ref "IC17") (pin "8") (pinfunction "AVDD_8") (pintype "power_in"))
      (node (ref "L5") (pin "2") (pinfunction "2_2") (pintype "passive"))
      (node (ref "R129") (pin "1") (pinfunction "1_1") (pintype "passive"))
      (node (ref "R130") (pin "1") (pinfunction "1_1") (pintype "passive"))
      (node (ref "R140") (pin "1") (pinfunction "1_1") (pintype "passive"))
    )
    (net (code "4") (name "+5V") (class "Default")
      (node (ref "DISP") (pin "3") (pinfunction "3_3") (pintype "bidirectional"))
      (node (ref "DISP") (pin "4") (pinfunction "4_4") (pintype "bidirectional"))
    )
    (net (code "5") (name "+5VA") (class "Default")
      (node (ref "+5VA") (pin "TP") (pinfunction "P$1_TP") (pintype "bidirectional"))
      (node (ref "C17") (pin "1") (pinfunction "1_1") (pintype "passive"))
      (node (ref "C2") (pin "1") (pinfunction "1_1") (pintype "passive"))
      (node (ref "C72") (pin "1") (pinfunction "1_1") (pintype "passive"))
      (node (ref "C73") (pin "1") (pinfunction "1_1") (pintype "passive"))
      (node (ref "C75") (pin "1") (pinfunction "1_1") (pintype "passive"))
      (node (ref "IC1") (pin "1") (pinfunction "IN_1") (pintype "bidirectional"))
      (node (ref "IC8") (pin "1") (pinfunction "IN_1") (pintype "bidirectional"))
      (node (ref "L3") (pin "2") (pinfunction "2_2") (pintype "passive"))
      (node (ref "R39") (pin "1") (pinfunction "1_1") (pintype "passive"))
    )
    (net (code "6") (name "+24V_A") (class "Default")
      (node (ref "C256") (pin "1") (pinfunction "+_1") (pintype "passive"))
      (node (ref "C257") (pin "1") (pinfunction "+_1") (pintype "passive"))
      (node (ref "C47") (pin "1") (pinfunction "1_1") (pintype "passive"))
      (node (ref "C48") (pin "1") (pinfunction "1_1") (pintype "passive"))
      (node (ref "C49") (pin "1") (pinfunction "1_1") (pintype "passive"))
      (node (ref "C50") (pin "1") (pinfunction "+_1") (pintype "passive"))
      (node (ref "C80") (pin "1") (pinfunction "1_1") (pintype "passive"))
      (node (ref "D11") (pin "C") (pinfunction "C_C") (pintype "passive"))
      (node (ref "F3") (pin "2_1") (pinfunction "2_2_1") (pintype "passive"))
      (node (ref "F3") (pin "2_2") (pinfunction "2_2_2") (pintype "passive"))
      (node (ref "IC12") (pin "3") (pinfunction "VIN_3") (pintype "power_in"))
      (node (ref "R70") (pin "1") (pinfunction "1_1") (pintype "passive"))
      (node (ref "T10") (pin "5") (pinfunction "D_5") (pintype "passive"))
      (node (ref "T10") (pin "6") (pinfunction "D_6") (pintype "passive"))
      (node (ref "T10") (pin "7") (pinfunction "D_7") (pintype "passive"))
      (node (ref "T10") (pin "8") (pinfunction "D_8") (pintype "passive"))
      (node (ref "T10") (pin "9") (pinfunction "D_9") (pintype "passive"))
    )
    (net (code "7") (name "+24V_B") (class "Default")
      (node (ref "F2") (pin "2_1") (pinfunction "2_2_1") (pintype "passive"))
      (node (ref "F2") (pin "2_2") (pinfunction "2_2_2") (pintype "passive"))
      (node (ref "R72") (pin "1") (pinfunction "1_1") (pintype "passive"))
    )
    (net (code "8") (name "+24V_C") (class "Default")
      (node (ref "+24V") (pin "TP") (pinfunction "P$1_TP") (pintype "bidirectional"))
      (node (ref "C252") (pin "1") (pinfunction "+_1") (pintype "passive"))
      (node (ref "C253") (pin "1") (pinfunction "+_1") (pintype "passive"))
      (node (ref "C34") (pin "1") (pinfunction "1_1") (pintype "passive"))
      (node (ref "C35") (pin "1") (pinfunction "1_1") (pintype "passive"))
      (node (ref "C71") (pin "1") (pinfunction "1_1") (pintype "passive"))
      (node (ref "C74") (pin "1") (pinfunction "1_1") (pintype "passive"))
      (node (ref "D9") (pin "C") (pinfunction "C_C") (pintype "passive"))
      (node (ref "F1") (pin "2_1") (pinfunction "2_2_1") (pintype "passive"))
      (node (ref "F1") (pin "2_2") (pinfunction "2_2_2") (pintype "passive"))
      (node (ref "IC2") (pin "2") (pinfunction "IN_2") (pintype "bidirectional"))
      (node (ref "IC40") (pin "2") (pinfunction "IN_2") (pintype "bidirectional"))
      (node (ref "R37") (pin "1") (pinfunction "1_1") (pintype "passive"))
      (node (ref "R44") (pin "1") (pinfunction "1_1") (pintype "passive"))
      (node (ref "R74") (pin "1") (pinfunction "1_1") (pintype "passive"))
    )
    (net (code "9") (name "ADC_3VA") (class "Default")
      (node (ref "IC26") (pin "52") (pinfunction "GPIO41_ADC1_52") (pintype "bidirectional"))
    )
    (net (code "10") (name "ADC_24VA") (class "Default")
      (node (ref "IC26") (pin "53") (pinfunction "GPIO42_ADC2_53") (pintype "bidirectional"))
      (node (ref "R70") (pin "2") (pinfunction "2_2") (pintype "passive"))
      (node (ref "R71") (pin "1") (pinfunction "1_1") (pintype "passive"))
    )
    (net (code "11") (name "ADC_24VB") (class "Default")
      (node (ref "IC26") (pin "54") (pinfunction "GPIO43_ADC3_54") (pintype "bidirectional"))
      (node (ref "R72") (pin "2") (pinfunction "2_2") (pintype "passive"))
      (node (ref "R73") (pin "1") (pinfunction "1_1") (pintype "passive"))
    )
    (net (code "12") (name "ADC_24VC") (class "Default")
      (node (ref "IC26") (pin "55") (pinfunction "GPIO44_ADC4_55") (pintype "bidirectional"))
      (node (ref "R74") (pin "2") (pinfunction "2_2") (pintype "passive"))
      (node (ref "R75") (pin "1") (pinfunction "1_1") (pintype "passive"))
    )
    (net (code "13") (name "ADC_VUSB") (class "Default")
      (node (ref "ADVB") (pin "TP") (pinfunction "P$1_TP") (pintype "bidirectional"))
      (node (ref "C29") (pin "1") (pinfunction "1_1") (pintype "passive"))
      (node (ref "IC26") (pin "49") (pinfunction "GPIO40_ADC0_49") (pintype "bidirectional"))
      (node (ref "R31") (pin "2") (pinfunction "2_2") (pintype "passive"))
      (node (ref "R32") (pin "1") (pinfunction "1_1") (pintype "passive"))
    )
    (net (code "14") (name "AVDD") (class "Default")
      (node (ref "AVDD") (pin "TP") (pinfunction "P$1_TP") (pintype "bidirectional"))
      (node (ref "C8") (pin "1") (pinfunction "1_1") (pintype "passive"))
      (node (ref "IC28") (pin "1") (pinfunction "OUT_1") (pintype "output"))
      (node (ref "IC28") (pin "4") (pinfunction "-IN_4") (pintype "input"))
      (node (ref "R28") (pin "2") (pinfunction "2_2") (pintype "passive"))
      (node (ref "R8") (pin "1") (pinfunction "1_1") (pintype "passive"))
    )
    (net (code "15") (name "CC1_PORT1") (class "Default")
      (node (ref "CC1") (pin "TP") (pinfunction "P$1_TP") (pintype "bidirectional"))
      (node (ref "IC9") (pin "2") (pinfunction "CC1_2") (pintype "bidirectional"))
      (node (ref "PORT1") (pin "A5") (pinfunction "CC1_A5") (pintype "passive"))
    )
    (net (code "16") (name "CC2_PORT1") (class "Default")
      (node (ref "CC2") (pin "TP") (pinfunction "P$1_TP") (pintype "bidirectional"))
      (node (ref "IC9") (pin "3") (pinfunction "CC2_3") (pintype "bidirectional"))
      (node (ref "PORT1") (pin "B5") (pinfunction "CC2_B5") (pintype "passive"))
    )
    (net (code "17") (name "EN_PORT1") (class "Default")
      (node (ref "IC12") (pin "4") (pinfunction "EN_4") (pintype "input"))
      (node (ref "IC26") (pin "25") (pinfunction "GPIO24_25") (pintype "bidirectional"))
      (node (ref "R69") (pin "1") (pinfunction "1_1") (pintype "passive"))
    )
    (net (code "18") (name "EN_PORT2") (class "Default")
      (node (ref "IC26") (pin "26") (pinfunction "GPIO25_26") (pintype "bidirectional"))
    )
    (net (code "19") (name "EN_PORT3") (class "Default")
      (node (ref "IC26") (pin "27") (pinfunction "GPIO26_27") (pintype "bidirectional"))
    )
    (net (code "20") (name "EN_PORT4") (class "Default")
      (node (ref "IC26") (pin "28") (pinfunction "GPIO27_28") (pintype "bidirectional"))
    )
    (net (code "21") (name "EN_PORT5") (class "Default")
      (node (ref "IC26") (pin "36") (pinfunction "GPIO28_36") (pintype "bidirectional"))
    )
    (net (code "22") (name "EN_PORT6") (class "Default")
      (node (ref "IC26") (pin "37") (pinfunction "GPIO29_37") (pintype "bidirectional"))
    )
    (net (code "23") (name "EN_PORT7") (class "Default")
      (node (ref "IC26") (pin "38") (pinfunction "GPIO30_38") (pintype "bidirectional"))
    )
    (net (code "24") (name "EN_PORT8") (class "Default")
      (node (ref "IC26") (pin "39") (pinfunction "GPIO31_39") (pintype "bidirectional"))
    )
    (net (code "25") (name "GND") (class "Default")
      (node (ref "24VGND") (pin "TP") (pinfunction "P$1_TP") (pintype "bidirectional"))
      (node (ref "C1") (pin "2") (pinfunction "2_2") (pintype "passive"))
      (node (ref "C10") (pin "2") (pinfunction "2_2") (pintype "passive"))
      (node (ref "C11") (pin "2") (pinfunction "2_2") (pintype "passive"))
      (node (ref "C12") (pin "2") (pinfunction "2_2") (pintype "passive"))
      (node (ref "C121") (pin "2") (pinfunction "2_2") (pintype "passive"))
      (node (ref "C122") (pin "2") (pinfunction "2_2") (pintype "passive"))
      (node (ref "C123") (pin "2") (pinfunction "2_2") (pintype "passive"))
      (node (ref "C124") (pin "2") (pinfunction "2_2") (pintype "passive"))
      (node (ref "C125") (pin "2") (pinfunction "2_2") (pintype "passive"))
      (node (ref "C126") (pin "2") (pinfunction "2_2") (pintype "passive"))
      (node (ref "C127") (pin "2") (pinfunction "2_2") (pintype "passive"))
      (node (ref "C13") (pin "2") (pinfunction "2_2") (pintype "passive"))
      (node (ref "C130") (pin "2") (pinfunction "2_2") (pintype "passive"))
      (node (ref "C131") (pin "2") (pinfunction "2_2") (pintype "passive"))
      (node (ref "C132") (pin "2") (pinfunction "2_2") (pintype "passive"))
      (node (ref "C133") (pin "2") (pinfunction "2_2") (pintype "passive"))
      (node (ref "C134") (pin "2") (pinfunction "2_2") (pintype "passive"))
      (node (ref "C14") (pin "2") (pinfunction "2_2") (pintype "passive"))
      (node (ref "C15") (pin "2") (pinfunction "2_2") (pintype "passive"))
      (node (ref "C16") (pin "2") (pinfunction "2_2") (pintype "passive"))
      (node (ref "C17") (pin "2") (pinfunction "2_2") (pintype "passive"))
      (node (ref "C18") (pin "2") (pinfunction "2_2") (pintype "passive"))
      (node (ref "C19") (pin "2") (pinfunction "2_2") (pintype "passive"))
      (node (ref "C2") (pin "2") (pinfunction "2_2") (pintype "passive"))
      (node (ref "C20") (pin "2") (pinfunction "2_2") (pintype "passive"))
      (node (ref "C21") (pin "2") (pinfunction "2_2") (pintype "passive"))
      (node (ref "C215") (pin "2") (pinfunction "2_2") (pintype "passive"))
      (node (ref "C216") (pin "2") (pinfunction "2_2") (pintype "passive"))
      (node (ref "C22") (pin "2") (pinfunction "2_2") (pintype "passive"))
      (node (ref "C23") (pin "2") (pinfunction "2_2") (pintype "passive"))
      (node (ref "C24") (pin "2") (pinfunction "2_2") (pintype "passive"))
      (node (ref "C25") (pin "2") (pinfunction "2_2") (pintype "passive"))
      (node (ref "C252") (pin "2") (pinfunction "-_2") (pintype "passive"))
      (node (ref "C253") (pin "2") (pinfunction "-_2") (pintype "passive"))
      (node (ref "C256") (pin "2") (pinfunction "-_2") (pintype "passive"))
      (node (ref "C257") (pin "2") (pinfunction "-_2") (pintype "passive"))
      (node (ref "C26") (pin "2") (pinfunction "2_2") (pintype "passive"))
      (node (ref "C27") (pin "2") (pinfunction "2_2") (pintype "passive"))
      (node (ref "C28") (pin "2") (pinfunction "2_2") (pintype "passive"))
      (node (ref "C29") (pin "2") (pinfunction "2_2") (pintype "passive"))
      (node (ref "C3") (pin "2") (pinfunction "2_2") (pintype "passive"))
      (node (ref "C31") (pin "2") (pinfunction "2_2") (pintype "passive"))
      (node (ref "C32") (pin "2") (pinfunction "2_2") (pintype "passive"))
      (node (ref "C33") (pin "2") (pinfunction "2_2") (pintype "passive"))
      (node (ref "C34") (pin "2") (pinfunction "2_2") (pintype "passive"))
      (node (ref "C35") (pin "2") (pinfunction "2_2") (pintype "passive"))
      (node (ref "C38") (pin "2") (pinfunction "2_2") (pintype "passive"))
      (node (ref "C39") (pin "2") (pinfunction "2_2") (pintype "passive"))
      (node (ref "C4") (pin "2") (pinfunction "2_2") (pintype "passive"))
      (node (ref "C40") (pin "1") (pinfunction "1_1") (pintype "passive"))
      (node (ref "C41") (pin "2") (pinfunction "2_2") (pintype "passive"))
      (node (ref "C42") (pin "2") (pinfunction "2_2") (pintype "passive"))
      (node (ref "C43") (pin "2") (pinfunction "2_2") (pintype "passive"))
      (node (ref "C44") (pin "2") (pinfunction "2_2") (pintype "passive"))
      (node (ref "C47") (pin "2") (pinfunction "2_2") (pintype "passive"))
      (node (ref "C48") (pin "2") (pinfunction "2_2") (pintype "passive"))
      (node (ref "C49") (pin "2") (pinfunction "2_2") (pintype "passive"))
      (node (ref "C5") (pin "2") (pinfunction "-_2") (pintype "passive"))
      (node (ref "C50") (pin "2") (pinfunction "-_2") (pintype "passive"))
      (node (ref "C51") (pin "1") (pinfunction "1_1") (pintype "passive"))
      (node (ref "C52") (pin "1") (pinfunction "1_1") (pintype "passive"))
      (node (ref "C53") (pin "1") (pinfunction "1_1") (pintype "passive"))
      (node (ref "C54") (pin "1") (pinfunction "1_1") (pintype "passive"))
      (node (ref "C55") (pin "2") (pinfunction "2_2") (pintype "passive"))
      (node (ref "C56") (pin "2") (pinfunction "2_2") (pintype "passive"))
      (node (ref "C57") (pin "2") (pinfunction "2_2") (pintype "passive"))
      (node (ref "C58") (pin "2") (pinfunction "2_2") (pintype "passive"))
      (node (ref "C59") (pin "2") (pinfunction "2_2") (pintype "passive"))
      (node (ref "C6") (pin "2") (pinfunction "2_2") (pintype "passive"))
      (node (ref "C60") (pin "2") (pinfunction "2_2") (pintype "passive"))
      (node (ref "C61") (pin "2") (pinfunction "2_2") (pintype "passive"))
      (node (ref "C62") (pin "2") (pinfunction "2_2") (pintype "passive"))
      (node (ref "C63") (pin "2") (pinfunction "2_2") (pintype "passive"))
      (node (ref "C64") (pin "2") (pinfunction "2_2") (pintype "passive"))
      (node (ref "C65") (pin "2") (pinfunction "2_2") (pintype "passive"))
      (node (ref "C66") (pin "2") (pinfunction "2_2") (pintype "passive"))
      (node (ref "C67") (pin "2") (pinfunction "2_2") (pintype "passive"))
      (node (ref "C68") (pin "2") (pinfunction "2_2") (pintype "passive"))
      (node (ref "C69") (pin "2") (pinfunction "2_2") (pintype "passive"))
      (node (ref "C7") (pin "2") (pinfunction "2_2") (pintype "passive"))
      (node (ref "C70") (pin "2") (pinfunction "2_2") (pintype "passive"))
      (node (ref "C71") (pin "2") (pinfunction "2_2") (pintype "passive"))
      (node (ref "C72") (pin "2") (pinfunction "2_2") (pintype "passive"))
      (node (ref "C73") (pin "2") (pinfunction "2_2") (pintype "passive"))
      (node (ref "C74") (pin "2") (pinfunction "2_2") (pintype "passive"))
      (node (ref "C76") (pin "2") (pinfunction "2_2") (pintype "passive"))
      (node (ref "C77") (pin "2") (pinfunction "2_2") (pintype "passive"))
      (node (ref "C78") (pin "2") (pinfunction "2_2") (pintype "passive"))
      (node (ref "C79") (pin "2") (pinfunction "-_2") (pintype "passive"))
      (node (ref "C8") (pin "2") (pinfunction "2_2") (pintype "passive"))
      (node (ref "C80") (pin "2") (pinfunction "2_2") (pintype "passive"))
      (node (ref "C82") (pin "1") (pinfunction "1_1") (pintype "passive"))
      (node (ref "C83") (pin "2") (pinfunction "-_2") (pintype "passive"))
      (node (ref "C84") (pin "2") (pinfunction "2_2") (pintype "passive"))
      (node (ref "C85") (pin "2") (pinfunction "2_2") (pintype "passive"))
      (node (ref "C9") (pin "2") (pinfunction "2_2") (pintype "passive"))
      (node (ref "C95") (pin "2") (pinfunction "2_2") (pintype "passive"))
      (node (ref "C96") (pin "2") (pinfunction "2_2") (pintype "passive"))
      (node (ref "C97") (pin "2") (pinfunction "2_2") (pintype "passive"))
      (node (ref "C98") (pin "2") (pinfunction "2_2") (pintype "passive"))
      (node (ref "D11") (pin "A") (pinfunction "A_A") (pintype "passive"))
      (node (ref "D12") (pin "2") (pinfunction "2_2") (pintype "power_in"))
      (node (ref "D13") (pin "2") (pinfunction "2_2") (pintype "power_in"))
      (node (ref "D2") (pin "C") (pinfunction "C_C") (pintype "passive"))
      (node (ref "D4") (pin "C") (pinfunction "C_C") (pintype "passive"))
      (node (ref "D9") (pin "A") (pinfunction "A_A") (pintype "passive"))
      (node (ref "DISP") (pin "5") (pinfunction "5_5") (pintype "bidirectional"))
      (node (ref "DISP") (pin "8") (pinfunction "8_8") (pintype "bidirectional"))
      (node (ref "DISP") (pin "Z0") (pinfunction "Z1_Z0") (pintype "bidirectional"))
      (node (ref "DISP") (pin "Z1") (pinfunction "Z1_Z1") (pintype "bidirectional"))
      (node (ref "DISP") (pin "Z2") (pinfunction "Z2_Z2") (pintype "bidirectional"))
      (node (ref "DISP") (pin "Z3") (pinfunction "Z3_Z3") (pintype "bidirectional"))
      (node (ref "DISP") (pin "Z4") (pinfunction "Z3_Z4") (pintype "bidirectional"))
      (node (ref "DISP") (pin "Z5") (pinfunction "Z4_Z5") (pintype "bidirectional"))
      (node (ref "ESD1") (pin "1") (pinfunction "A_1") (pintype "bidirectional"))
      (node (ref "ETH2") (pin "8") (pinfunction "GND_8") (pintype "power_in"))
      (node (ref "IC1") (pin "2") (pinfunction "GND_2") (pintype "bidirectional"))
      (node (ref "IC12") (pin "10") (pinfunction "AGND_10") (pintype "power_in"))
      (node (ref "IC12") (pin "24") (pinfunction "PGND_24") (pintype "power_in"))
      (node (ref "IC12") (pin "9") (pinfunction "PGND_9") (pintype "power_in"))
      (node (ref "IC13") (pin "3") (pinfunction "GND_3") (pintype "bidirectional"))
      (node (ref "IC13") (pin "7") (pinfunction "A0_7") (pintype "bidirectional"))
      (node (ref "IC13") (pin "8") (pinfunction "A1_8") (pintype "bidirectional"))
      (node (ref "IC17") (pin "14") (pinfunction "AGND_14") (pintype "power_in"))
      (node (ref "IC17") (pin "16") (pinfunction "AGND_16") (pintype "power_in"))
      (node (ref "IC17") (pin "19") (pinfunction "AGND_19") (pintype "power_in"))
      (node (ref "IC17") (pin "29") (pinfunction "GND_29") (pintype "passive"))
      (node (ref "IC17") (pin "3") (pinfunction "AGND_3") (pintype "power_in"))
      (node (ref "IC17") (pin "48") (pinfunction "AGND_48") (pintype "power_in"))
      (node (ref "IC17") (pin "9") (pinfunction "AGND_9") (pintype "power_in"))
      (node (ref "IC2") (pin "4") (pinfunction "GND_4") (pintype "bidirectional"))
      (node (ref "IC26") (pin "62") (pinfunction "VREG_PGND_62") (pintype "power_in"))
      (node (ref "IC26") (pin "81") (pinfunction "GND_81") (pintype "power_in"))
      (node (ref "IC27") (pin "4") (pinfunction "GND_4") (pintype "power_in"))
      (node (ref "IC27") (pin "PAD") (pinfunction "GND_PAD") (pintype "power_in"))
      (node (ref "IC28") (pin "5") (pinfunction "V-_5") (pintype "power_in"))
      (node (ref "IC29") (pin "2") (pinfunction "A1_2") (pintype "bidirectional"))
      (node (ref "IC29") (pin "3") (pinfunction "A2_3") (pintype "bidirectional"))
      (node (ref "IC29") (pin "4") (pinfunction "GND_4") (pintype "power_in"))
      (node (ref "IC29") (pin "7") (pinfunction "WP_7") (pintype "bidirectional"))
      (node (ref "IC29") (pin "9") (pinfunction "GND_9") (pintype "power_in"))
      (node (ref "IC38") (pin "18") (pinfunction "A2_18") (pintype "input"))
      (node (ref "IC38") (pin "22") (pinfunction "A0_22") (pintype "input"))
      (node (ref "IC38") (pin "23") (pinfunction "A1_23") (pintype "input"))
      (node (ref "IC38") (pin "25") (pinfunction "GND_25") (pintype "power_in"))
      (node (ref "IC38") (pin "9") (pinfunction "GND_9") (pintype "power_in"))
      (node (ref "IC39") (pin "4") (pinfunction "GND_4") (pintype "power_in"))
      (node (ref "IC39") (pin "PAD") (pinfunction "GND_PAD") (pintype "power_in"))
      (node (ref "IC4") (pin "3") (pinfunction "V-_3") (pintype "bidirectional"))
      (node (ref "IC40") (pin "4") (pinfunction "GND_4") (pintype "bidirectional"))
      (node (ref "IC5") (pin "3") (pinfunction "V-_3") (pintype "bidirectional"))
      (node (ref "IC8") (pin "2") (pinfunction "GND_2") (pintype "bidirectional"))
      (node (ref "IC9") (pin "6") (pinfunction "GND_6") (pintype "power_in"))
      (node (ref "J8") (pin "4") (pinfunction "4_4") (pintype "passive"))
      (node (ref "J8") (pin "5") (pinfunction "5_5") (pintype "passive"))
      (node (ref "J8") (pin "6") (pinfunction "6_6") (pintype "passive"))
      (node (ref "JTAG") (pin "3") (pinfunction "3_3") (pintype "passive"))
      (node (ref "JTAG") (pin "5") (pinfunction "5_5") (pintype "passive"))
      (node (ref "JTAG") (pin "9") (pinfunction "9_9") (pintype "passive"))
      (node (ref "PORT1") (pin "A12") (pinfunction "GND1_A12") (pintype "passive"))
      (node (ref "PORT1") (pin "B12") (pinfunction "GND2_B12") (pintype "passive"))
      (node (ref "R1") (pin "2") (pinfunction "2_2") (pintype "passive"))
      (node (ref "R10") (pin "2") (pinfunction "2_2") (pintype "passive"))
      (node (ref "R136") (pin "2") (pinfunction "2_2") (pintype "passive"))
      (node (ref "R141") (pin "1") (pinfunction "1_1") (pintype "passive"))
      (node (ref "R18") (pin "2") (pinfunction "2_2") (pintype "passive"))
      (node (ref "R19") (pin "2") (pinfunction "2_2") (pintype "passive"))
      (node (ref "R2") (pin "1") (pinfunction "1_1") (pintype "passive"))
      (node (ref "R20") (pin "2") (pinfunction "2_2") (pintype "passive"))
      (node (ref "R3") (pin "2") (pinfunction "2_2") (pintype "passive"))
      (node (ref "R32") (pin "2") (pinfunction "2_2") (pintype "passive"))
      (node (ref "R33") (pin "2") (pinfunction "2_2") (pintype "passive"))
      (node (ref "R36") (pin "2") (pinfunction "2_2") (pintype "passive"))
      (node (ref "R40") (pin "2") (pinfunction "2_2") (pintype "passive"))
      (node (ref "R43") (pin "2") (pinfunction "2_2") (pintype "passive"))
      (node (ref "R49") (pin "2") (pinfunction "2_2") (pintype "passive"))
      (node (ref "R50") (pin "1") (pinfunction "1_1") (pintype "passive"))
      (node (ref "R51") (pin "2") (pinfunction "2_2") (pintype "passive"))
      (node (ref "R52") (pin "2") (pinfunction "2_2") (pintype "passive"))
      (node (ref "R56") (pin "2") (pinfunction "2_2") (pintype "passive"))
      (node (ref "R58") (pin "2") (pinfunction "2_2") (pintype "passive"))
      (node (ref "R59") (pin "2") (pinfunction "2_2") (pintype "passive"))
      (node (ref "R61") (pin "2") (pinfunction "2_2") (pintype "passive"))
      (node (ref "R67") (pin "2") (pinfunction "2_2") (pintype "passive"))
      (node (ref "R68") (pin "2") (pinfunction "2_2") (pintype "passive"))
      (node (ref "R69") (pin "2") (pinfunction "2_2") (pintype "passive"))
      (node (ref "R71") (pin "2") (pinfunction "2_2") (pintype "passive"))
      (node (ref "R73") (pin "2") (pinfunction "2_2") (pintype "passive"))
      (node (ref "R75") (pin "2") (pinfunction "2_2") (pintype "passive"))
      (node (ref "R9") (pin "2") (pinfunction "2_2") (pintype "passive"))
      (node (ref "REF1") (pin "2") (pinfunction "A_2") (pintype "passive"))
      (node (ref "REF1") (pin "3") (pinfunction "A_3") (pintype "passive"))
      (node (ref "SW1") (pin "1") (pinfunction "P$1_1") (pintype "bidirectional"))
      (node (ref "SW2") (pin "2") (pinfunction "P$2_2") (pintype "bidirectional"))
      (node (ref "T9") (pin "1") (pinfunction "S_1") (pintype "passive"))
      (node (ref "T9") (pin "2") (pinfunction "S_2") (pintype "passive"))
      (node (ref "T9") (pin "3") (pinfunction "S_3") (pintype "passive"))
      (node (ref "USB9") (pin "GND") (pinfunction "GND_GND") (pintype "power_in"))
      (node (ref "USB9") (pin "GND2") (pinfunction "GND_GND2") (pintype "power_in"))
      (node (ref "USBA_1-2") (pin "4") (pinfunction "GND_4") (pintype "passive"))
      (node (ref "USBA_1-2") (pin "8") (pinfunction "GND_8") (pintype "passive"))
      (node (ref "X1") (pin "2") (pinfunction "GND_2") (pintype "passive"))
      (node (ref "X1") (pin "4") (pinfunction "GND_4") (pintype "passive"))
      (node (ref "X3") (pin "2") (pinfunction "GND_2") (pintype "passive"))
      (node (ref "X3") (pin "4") (pinfunction "GND_4") (pintype "passive"))
    )
    (net (code "26") (name "I2C0_SCL") (class "Default")
      (node (ref "D12") (pin "3") (pinfunction "3_3") (pintype "bidirectional"))
      (node (ref "IC26") (pin "2") (pinfunction "GPIO5_2") (pintype "bidirectional"))
      (node (ref "IC38") (pin "19") (pinfunction "SCL_19") (pintype "bidirectional"))
      (node (ref "RN1") (pin "B1") (pinfunction "2_B1") (pintype "passive"))
    )
    (net (code "27") (name "I2C0_SDA") (class "Default")
      (node (ref "D12") (pin "1") (pinfunction "1_1") (pintype "bidirectional"))
      (node (ref "IC26") (pin "1") (pinfunction "GPIO4_1") (pintype "bidirectional"))
      (node (ref "IC38") (pin "20") (pinfunction "SDA_20") (pintype "bidirectional"))
      (node (ref "RN1") (pin "D1") (pinfunction "4_D1") (pintype "passive"))
    )
    (net (code "28") (name "I2C1_SCL") (class "Default")
      (node (ref "D12") (pin "6") (pinfunction "6_6") (pintype "bidirectional"))
      (node (ref "DISP") (pin "7") (pinfunction "7_7") (pintype "bidirectional"))
      (node (ref "IC26") (pin "4") (pinfunction "GPIO7_4") (pintype "bidirectional"))
      (node (ref "IC29") (pin "6") (pinfunction "SCL_6") (pintype "bidirectional"))
      (node (ref "RN1") (pin "C1") (pinfunction "3_C1") (pintype "passive"))
    )
    (net (code "29") (name "I2C1_SDA") (class "Default")
      (node (ref "D12") (pin "4") (pinfunction "4_4") (pintype "bidirectional"))
      (node (ref "DISP") (pin "6") (pinfunction "6_6") (pintype "bidirectional"))
      (node (ref "IC26") (pin "3") (pinfunction "GPIO6_3") (pintype "bidirectional"))
      (node (ref "IC29") (pin "5") (pinfunction "SDA_5") (pintype "bidirectional"))
      (node (ref "RN1") (pin "A1") (pinfunction "1_A1") (pintype "passive"))
    )
    (net (code "30") (name "IN1_PORT1") (class "Default")
      (node (ref "CPDO1") (pin "TP") (pinfunction "P$1_TP") (pintype "bidirectional"))
      (node (ref "IC13") (pin "1") (pinfunction "IN+_1") (pintype "bidirectional"))
      (node (ref "IC9") (pin "12") (pinfunction "VBUS_SENSE_12") (pintype "input"))
      (node (ref "R57") (pin "2") (pinfunction "2_2") (pintype "passive"))
      (node (ref "T8") (pin "5") (pinfunction "D_5") (pintype "passive"))
      (node (ref "T8") (pin "6") (pinfunction "D_6") (pintype "passive"))
      (node (ref "T8") (pin "7") (pinfunction "D_7") (pintype "passive"))
      (node (ref "T8") (pin "8") (pinfunction "D_8") (pintype "passive"))
      (node (ref "T8") (pin "9") (pinfunction "D_9") (pintype "passive"))
    )
    (net (code "31") (name "IN2_PORT1") (class "Default")
      (node (ref "CPDO2") (pin "TP") (pinfunction "P$1_TP") (pintype "bidirectional"))
      (node (ref "IC13") (pin "2") (pinfunction "IN-_2") (pintype "bidirectional"))
      (node (ref "PORT1") (pin "A9") (pinfunction "VBUS1_A9") (pintype "passive"))
      (node (ref "PORT1") (pin "B9") (pinfunction "VBUS2_B9") (pintype "passive"))
      (node (ref "R57") (pin "1") (pinfunction "1_1") (pintype "passive"))
    )
    (net (code "32") (name "KEY_0") (class "Default")
      (node (ref "D13") (pin "6") (pinfunction "6_6") (pintype "bidirectional"))
      (node (ref "DISP") (pin "12") (pinfunction "12_12") (pintype "bidirectional"))
      (node (ref "IC26") (pin "11") (pinfunction "GPIO12_11") (pintype "bidirectional"))
    )
    (net (code "33") (name "KEY_1") (class "Default")
      (node (ref "D13") (pin "4") (pinfunction "4_4") (pintype "bidirectional"))
      (node (ref "DISP") (pin "11") (pinfunction "11_11") (pintype "bidirectional"))
      (node (ref "IC26") (pin "12") (pinfunction "GPIO13_12") (pintype "bidirectional"))
    )
    (net (code "34") (name "KEY_2") (class "Default")
      (node (ref "D13") (pin "3") (pinfunction "3_3") (pintype "bidirectional"))
      (node (ref "DISP") (pin "10") (pinfunction "10_10") (pintype "bidirectional"))
      (node (ref "IC26") (pin "13") (pinfunction "GPIO14_13") (pintype "bidirectional"))
    )
    (net (code "35") (name "KEY_3") (class "Default")
      (node (ref "D13") (pin "1") (pinfunction "1_1") (pintype "bidirectional"))
      (node (ref "DISP") (pin "9") (pinfunction "9_9") (pintype "bidirectional"))
      (node (ref "IC26") (pin "14") (pinfunction "GPIO15_14") (pintype "bidirectional"))
    )
    (net (code "36") (name "MCP_DSP_RST") (class "Default")
      (node (ref "DISP") (pin "20") (pinfunction "20_20") (pintype "bidirectional"))
      (node (ref "R21") (pin "2") (pinfunction "2_2") (pintype "passive"))
    )
    (net (code "37") (name "Net-(3VFB-P$1)") (class "Default")
      (node (ref "3VFB") (pin "TP") (pinfunction "P$1_TP") (pintype "bidirectional"))
      (node (ref "C36") (pin "2") (pinfunction "2_2") (pintype "passive"))
      (node (ref "R22") (pin "2") (pinfunction "2_2") (pintype "passive"))
      (node (ref "R23") (pin "2") (pinfunction "2_2") (pintype "passive"))
      (node (ref "R33") (pin "1") (pinfunction "1_1") (pintype "passive"))
    )
    (net (code "38") (name "Net-(5VFB-P$1)") (class "Default")
      (node (ref "5VFB") (pin "TP") (pinfunction "P$1_TP") (pintype "bidirectional"))
      (node (ref "C75") (pin "2") (pinfunction "2_2") (pintype "passive"))
      (node (ref "R39") (pin "2") (pinfunction "2_2") (pintype "passive"))
      (node (ref "R40") (pin "1") (pinfunction "1_1") (pintype "passive"))
      (node (ref "R45") (pin "2") (pinfunction "2_2") (pintype "passive"))
    )
    (net (code "39") (name "Net-(C30-Pad1)") (class "Default")
      (node (ref "C30") (pin "1") (pinfunction "1_1") (pintype "passive"))
      (node (ref "R34") (pin "2") (pinfunction "2_2") (pintype "passive"))
    )
    (net (code "40") (name "Net-(C37-Pad1)") (class "Default")
      (node (ref "C37") (pin "1") (pinfunction "1_1") (pintype "passive"))
      (node (ref "R41") (pin "2") (pinfunction "2_2") (pintype "passive"))
    )
    (net (code "41") (name "Net-(C44-Pad1)") (class "Default")
      (node (ref "C44") (pin "1") (pinfunction "1_1") (pintype "passive"))
      (node (ref "R62") (pin "2") (pinfunction "2_2") (pintype "passive"))
    )
    (net (code "42") (name "Net-(C215-Pad1)") (class "Default")
      (node (ref "C215") (pin "1") (pinfunction "1_1") (pintype "passive"))
      (node (ref "R231") (pin "2") (pinfunction "2_2") (pintype "passive"))
    )
    (net (code "43") (name "Net-(C216-Pad1)") (class "Default")
      (node (ref "C216") (pin "1") (pinfunction "1_1") (pintype "passive"))
      (node (ref "R232") (pin "2") (pinfunction "2_2") (pintype "passive"))
    )
    (net (code "44") (name "Net-(D1-PadC)") (class "Default")
      (node (ref "D1") (pin "C") (pinfunction "C_C") (pintype "passive"))
      (node (ref "R14") (pin "2") (pinfunction "2_2") (pintype "passive"))
    )
    (net (code "45") (name "Net-(D2-PadA)") (class "Default")
      (node (ref "D2") (pin "A") (pinfunction "A_A") (pintype "passive"))
      (node (ref "R12") (pin "2") (pinfunction "2_2") (pintype "passive"))
    )
    (net (code "46") (name "Net-(D3-PadC)") (class "Default")
      (node (ref "D3") (pin "C") (pinfunction "C_C") (pintype "passive"))
      (node (ref "R17") (pin "2") (pinfunction "2_2") (pintype "passive"))
    )
    (net (code "47") (name "Net-(D4-PadA)") (class "Default")
      (node (ref "D4") (pin "A") (pinfunction "A_A") (pintype "passive"))
      (node (ref "R15") (pin "1") (pinfunction "1_1") (pintype "passive"))
    )
    (net (code "48") (name "Net-(ETH2-GREEN-)") (class "Default")
      (node (ref "ETH2") (pin "9") (pinfunction "GREEN-_9") (pintype "passive"))
      (node (ref "R138") (pin "2") (pinfunction "2_2") (pintype "passive"))
    )
    (net (code "49") (name "Net-(ETH2-YELLOW-)") (class "Default")
      (node (ref "ETH2") (pin "11") (pinfunction "YELLOW-_11") (pintype "passive"))
      (node (ref "R139") (pin "2") (pinfunction "2_2") (pintype "passive"))
    )
    (net (code "50") (name "Net-(F1-1-Pad1_1)") (class "Default")
      (node (ref "F1") (pin "1_1") (pinfunction "1_1_1") (pintype "passive"))
      (node (ref "F1") (pin "1_2") (pinfunction "1_1_2") (pintype "passive"))
      (node (ref "J8") (pin "1") (pinfunction "1_1") (pintype "passive"))
    )
    (net (code "51") (name "Net-(F2-1-Pad1_1)") (class "Default")
      (node (ref "F2") (pin "1_1") (pinfunction "1_1_1") (pintype "passive"))
      (node (ref "F2") (pin "1_2") (pinfunction "1_1_2") (pintype "passive"))
      (node (ref "J8") (pin "2") (pinfunction "2_2") (pintype "passive"))
    )
    (net (code "52") (name "Net-(F3-1-Pad1_1)") (class "Default")
      (node (ref "F3") (pin "1_1") (pinfunction "1_1_1") (pintype "passive"))
      (node (ref "F3") (pin "1_2") (pinfunction "1_1_2") (pintype "passive"))
      (node (ref "J8") (pin "3") (pinfunction "3_3") (pintype "passive"))
    )
    (net (code "53") (name "Net-(IC1-ILIM)") (class "Default")
      (node (ref "IC1") (pin "5") (pinfunction "ILIM_5") (pintype "bidirectional"))
      (node (ref "R66") (pin "1") (pinfunction "1_1") (pintype "passive"))
    )
    (net (code "54") (name "Net-(IC2-AAM)") (class "Default")
      (node (ref "C85") (pin "1") (pinfunction "1_1") (pintype "passive"))
      (node (ref "IC2") (pin "1") (pinfunction "AAM_1") (pintype "bidirectional"))
      (node (ref "R43") (pin "1") (pinfunction "1_1") (pintype "passive"))
    )
    (net (code "55") (name "Net-(IC2-BST)") (class "Default")
      (node (ref "IC2") (pin "5") (pinfunction "BST_5") (pintype "bidirectional"))
      (node (ref "R41") (pin "1") (pinfunction "1_1") (pintype "passive"))
    )
    (net (code "56") (name "Net-(IC2-EN)") (class "Default")
      (node (ref "IC2") (pin "6") (pinfunction "EN_6") (pintype "bidirectional"))
      (node (ref "R44") (pin "2") (pinfunction "2_2") (pintype "passive"))
    )
    (net (code "57") (name "Net-(IC2-FB)") (class "Default")
      (node (ref "IC2") (pin "8") (pinfunction "FB_8") (pintype "bidirectional"))
      (node (ref "R38") (pin "1") (pinfunction "1_1") (pintype "passive"))
    )
    (net (code "58") (name "Net-(IC2-SW)") (class "Default")
      (node (ref "C37") (pin "2") (pinfunction "2_2") (pintype "passive"))
      (node (ref "IC2") (pin "3") (pinfunction "SW_3") (pintype "bidirectional"))
      (node (ref "L3") (pin "1") (pinfunction "1_1") (pintype "passive"))
    )
    (net (code "59") (name "Net-(IC2-VCC)") (class "Default")
      (node (ref "C38") (pin "1") (pinfunction "1_1") (pintype "passive"))
      (node (ref "IC2") (pin "7") (pinfunction "VCC_7") (pintype "bidirectional"))
    )
    (net (code "60") (name "Net-(IC4-OUT)") (class "Default")
      (node (ref "IC4") (pin "4") (pinfunction "OUT_4") (pintype "bidirectional"))
      (node (ref "R12") (pin "1") (pinfunction "1_1") (pintype "passive"))
      (node (ref "R14") (pin "1") (pinfunction "1_1") (pintype "passive"))
    )
    (net (code "61") (name "Net-(IC5-OUT)") (class "Default")
      (node (ref "IC5") (pin "4") (pinfunction "OUT_4") (pintype "bidirectional"))
      (node (ref "R15") (pin "2") (pinfunction "2_2") (pintype "passive"))
      (node (ref "R17") (pin "1") (pinfunction "1_1") (pintype "passive"))
    )
    (net (code "62") (name "Net-(IC8-ILIM)") (class "Default")
      (node (ref "IC8") (pin "5") (pinfunction "ILIM_5") (pintype "bidirectional"))
      (node (ref "R16") (pin "1") (pinfunction "1_1") (pintype "passive"))
    )
    (net (code "63") (name "Net-(IC9-ADDR0)") (class "Default")
      (node (ref "IC9") (pin "9") (pinfunction "ADDR0_9") (pintype "input"))
      (node (ref "R51") (pin "1") (pinfunction "1_1") (pintype "passive"))
    )
    (net (code "64") (name "Net-(IC9-SEL_PDO2)") (class "Default")
      (node (ref "IC9") (pin "8") (pinfunction "SEL_PDO2_8") (pintype "open_collector"))
      (node (ref "PDO2") (pin "TP") (pinfunction "P$1_TP") (pintype "bidirectional"))
      (node (ref "R48") (pin "2") (pinfunction "2_2") (pintype "passive"))
      (node (ref "R49") (pin "1") (pinfunction "1_1") (pintype "passive"))
    )
    (net (code "65") (name "Net-(IC9-SEL_PDO3)") (class "Default")
      (node (ref "IC9") (pin "7") (pinfunction "SEL_PDO3_7") (pintype "open_collector"))
      (node (ref "PDO3") (pin "TP") (pinfunction "P$1_TP") (pintype "bidirectional"))
      (node (ref "R47") (pin "2") (pinfunction "2_2") (pintype "passive"))
      (node (ref "R48") (pin "1") (pinfunction "1_1") (pintype "passive"))
    )
    (net (code "66") (name "Net-(IC9-SEL_PDO4)") (class "Default")
      (node (ref "IC9") (pin "10") (pinfunction "SEL_PDO4_10") (pintype "open_collector"))
      (node (ref "PDO4") (pin "TP") (pinfunction "P$1_TP") (pintype "bidirectional"))
      (node (ref "R46") (pin "2") (pinfunction "2_2") (pintype "passive"))
      (node (ref "R47") (pin "1") (pinfunction "1_1") (pintype "passive"))
    )
    (net (code "67") (name "Net-(IC9-SEL_PDO5)") (class "Default")
      (node (ref "IC9") (pin "11") (pinfunction "SEL_PDO5_11") (pintype "open_collector"))
      (node (ref "PDO5") (pin "TP") (pinfunction "P$1_TP") (pintype "bidirectional"))
      (node (ref "R11") (pin "2") (pinfunction "2_2") (pintype "passive"))
      (node (ref "R46") (pin "1") (pinfunction "1_1") (pintype "passive"))
    )
    (net (code "68") (name "Net-(IC9-VBUS_DISCH)") (class "Default")
      (node (ref "IC9") (pin "13") (pinfunction "VBUS_DISCH_13") (pintype "output"))
      (node (ref "R55") (pin "2") (pinfunction "2_2") (pintype "passive"))
      (node (ref "T6") (pin "4") (pinfunction "G_4") (pintype "passive"))
    )
    (net (code "69") (name "Net-(IC9-VBUS_EN_SRC)") (class "Default")
      (node (ref "IC9") (pin "14") (pinfunction "VBUS_EN_SRC_14") (pintype "open_collector"))
      (node (ref "R54") (pin "2") (pinfunction "2_2") (pintype "passive"))
    )
    (net (code "70") (name "Net-(IC9-VREG1V2)") (class "Default")
      (node (ref "C6") (pin "1") (pinfunction "1_1") (pintype "passive"))
      (node (ref "IC9") (pin "15") (pinfunction "VREG1V2_15") (pintype "input"))
    )
    (net (code "71") (name "Net-(IC9-VREG2V7)") (class "Default")
      (node (ref "C16") (pin "1") (pinfunction "1_1") (pintype "passive"))
      (node (ref "IC9") (pin "16") (pinfunction "VREG2V7_16") (pintype "input"))
    )
    (net (code "72") (name "Net-(IC12-BOOT1)") (class "Default")
      (node (ref "C45") (pin "2") (pinfunction "2_2") (pintype "passive"))
      (node (ref "IC12") (pin "22") (pinfunction "BOOT1_22") (pintype "power_in"))
    )
    (net (code "73") (name "Net-(IC12-BOOT2)") (class "Default")
      (node (ref "C46") (pin "2") (pinfunction "2_2") (pintype "passive"))
      (node (ref "IC12") (pin "20") (pinfunction "BOOT2_20") (pintype "power_in"))
    )
    (net (code "74") (name "Net-(IC12-CDC)") (class "Default")
      (node (ref "IC12") (pin "16") (pinfunction "CDC_16") (pintype "output"))
      (node (ref "R61") (pin "1") (pinfunction "1_1") (pintype "passive"))
    )
    (net (code "75") (name "Net-(IC12-COMP)") (class "Default")
      (node (ref "C43") (pin "1") (pinfunction "1_1") (pintype "passive"))
      (node (ref "IC12") (pin "18") (pinfunction "COMP_18") (pintype "input"))
      (node (ref "R62") (pin "1") (pinfunction "1_1") (pintype "passive"))
    )
    (net (code "76") (name "Net-(IC12-DITH_SYNC)") (class "Default")
      (node (ref "C42") (pin "1") (pinfunction "1_1") (pintype "passive"))
      (node (ref "IC12") (pin "7") (pinfunction "DITH_SYNC_7") (pintype "input"))
    )
    (net (code "77") (name "Net-(IC12-DR1H)") (class "Default")
      (node (ref "IC12") (pin "2") (pinfunction "DR1H_2") (pintype "output"))
      (node (ref "R65") (pin "2") (pinfunction "2_2") (pintype "passive"))
    )
    (net (code "78") (name "Net-(IC12-DR1L)") (class "Default")
      (node (ref "IC12") (pin "1") (pinfunction "DR1L_1") (pintype "output"))
      (node (ref "R64") (pin "2") (pinfunction "2_2") (pintype "passive"))
    )
    (net (code "79") (name "Net-(IC12-FB)") (class "Default")
      (node (ref "IC12") (pin "14") (pinfunction "FB_14") (pintype "input"))
      (node (ref "PDOFB") (pin "TP") (pinfunction "P$1_TP") (pintype "bidirectional"))
      (node (ref "R11") (pin "1") (pinfunction "1_1") (pintype "passive"))
      (node (ref "R5") (pin "2") (pinfunction "2_2") (pintype "passive"))
    )
    (net (code "80") (name "Net-(IC12-FSW)") (class "Default")
      (node (ref "IC12") (pin "8") (pinfunction "FSW_8") (pintype "input"))
      (node (ref "R59") (pin "1") (pinfunction "1_1") (pintype "passive"))
    )
    (net (code "81") (name "Net-(IC12-ILIM)") (class "Default")
      (node (ref "IC12") (pin "17") (pinfunction "ILIM_17") (pintype "output"))
      (node (ref "R60") (pin "1") (pinfunction "1_1") (pintype "passive"))
    )
    (net (code "82") (name "Net-(IC12-MODE)") (class "Default")
      (node (ref "IC12") (pin "15") (pinfunction "MODE_15") (pintype "input"))
      (node (ref "R58") (pin "1") (pinfunction "1_1") (pintype "passive"))
    )
    (net (code "83") (name "Net-(IC12-SW1)") (class "Default")
      (node (ref "C45") (pin "1") (pinfunction "1_1") (pintype "passive"))
      (node (ref "IC12") (pin "23") (pinfunction "SW1_23") (pintype "power_in"))
      (node (ref "L2") (pin "1") (pinfunction "1_1") (pintype "passive"))
      (node (ref "R231") (pin "1") (pinfunction "1_1") (pintype "passive"))
      (node (ref "T10") (pin "1") (pinfunction "S_1") (pintype "passive"))
      (node (ref "T10") (pin "2") (pinfunction "S_2") (pintype "passive"))
      (node (ref "T10") (pin "3") (pinfunction "S_3") (pintype "passive"))
      (node (ref "T9") (pin "5") (pinfunction "D_5") (pintype "passive"))
      (node (ref "T9") (pin "6") (pinfunction "D_6") (pintype "passive"))
      (node (ref "T9") (pin "7") (pinfunction "D_7") (pintype "passive"))
      (node (ref "T9") (pin "8") (pinfunction "D_8") (pintype "passive"))
      (node (ref "T9") (pin "9") (pinfunction "D_9") (pintype "passive"))
      (node (ref "VTPS1") (pin "TP") (pinfunction "P$1_TP") (pintype "bidirectional"))
    )
    (net (code "84") (name "Net-(IC12-VCC)") (class "Default")
      (node (ref "C41") (pin "1") (pinfunction "1_1") (pintype "passive"))
      (node (ref "IC12") (pin "19") (pinfunction "VCC_19") (pintype "power_in"))
    )
    (net (code "85") (name "Net-(IC17-1V2O)") (class "Default")
      (node (ref "C96") (pin "1") (pinfunction "1_1") (pintype "passive"))
      (node (ref "IC17") (pin "22") (pinfunction "1V2O_22") (pintype "output"))
    )
    (net (code "86") (name "Net-(IC17-EXRES1)") (class "Default")
      (node (ref "IC17") (pin "10") (pinfunction "EXRES1_10") (pintype "bidirectional"))
      (node (ref "R136") (pin "1") (pinfunction "1_1") (pintype "passive"))
    )
    (net (code "87") (name "Net-(IC17-TOCAP)") (class "Default")
      (node (ref "C134") (pin "1") (pinfunction "1_1") (pintype "passive"))
      (node (ref "IC17") (pin "20") (pinfunction "TOCAP_20") (pintype "output"))
    )
    (net (code "88") (name "Net-(IC17-XI)") (class "Default")
      (node (ref "C133") (pin "1") (pinfunction "1_1") (pintype "passive"))
      (node (ref "IC17") (pin "30") (pinfunction "XI_30") (pintype "input"))
      (node (ref "R137") (pin "2") (pinfunction "2_2") (pintype "passive"))
      (node (ref "X3") (pin "3") (pinfunction "2_3") (pintype "passive"))
    )
    (net (code "89") (name "Net-(IC17-XO)") (class "Default")
      (node (ref "C132") (pin "1") (pinfunction "1_1") (pintype "passive"))
      (node (ref "IC17") (pin "31") (pinfunction "XO_31") (pintype "output"))
      (node (ref "R137") (pin "1") (pinfunction "1_1") (pintype "passive"))
      (node (ref "X3") (pin "1") (pinfunction "1_1") (pintype "passive"))
    )
    (net (code "90") (name "Net-(IC26C-ADC_AVDD)") (class "Default")
      (node (ref "C12") (pin "1") (pinfunction "1_1") (pintype "passive"))
      (node (ref "IC26") (pin "59") (pinfunction "ADC_AVDD_59") (pintype "power_in"))
      (node (ref "R28") (pin "1") (pinfunction "1_1") (pintype "passive"))
      (node (ref "R29") (pin "2") (pinfunction "2_2") (pintype "passive"))
    )
    (net (code "91") (name "Net-(IC26C-USB_DM)") (class "Default")
      (node (ref "IC26") (pin "66") (pinfunction "USB_DM_66") (pintype "bidirectional"))
      (node (ref "R25") (pin "2") (pinfunction "2_2") (pintype "passive"))
    )
    (net (code "92") (name "Net-(IC26C-USB_DP)") (class "Default")
      (node (ref "IC26") (pin "67") (pinfunction "USB_DP_67") (pintype "bidirectional"))
      (node (ref "R26") (pin "2") (pinfunction "2_2") (pintype "passive"))
    )
    (net (code "93") (name "Net-(IC26C-VREG_AVDD)") (class "Default")
      (node (ref "C21") (pin "1") (pinfunction "1_1") (pintype "passive"))
      (node (ref "IC26") (pin "61") (pinfunction "VREG_AVDD_61") (pintype "power_in"))
      (node (ref "R27") (pin "2") (pinfunction "2_2") (pintype "passive"))
    )
    (net (code "94") (name "Net-(IC26C-VREG_LX)") (class "Default")
      (node (ref "IC26") (pin "63") (pinfunction "VREG_LX_63") (pintype "power_in"))
      (node (ref "L1") (pin "1") (pinfunction "1_1") (pintype "passive"))
    )
    (net (code "95") (name "Net-(IC26C-XIN)") (class "Default")
      (node (ref "C63") (pin "1") (pinfunction "1_1") (pintype "passive"))
      (node (ref "IC26") (pin "30") (pinfunction "XIN_30") (pintype "input"))
      (node (ref "X1") (pin "1") (pinfunction "1_1") (pintype "passive"))
    )
    (net (code "96") (name "Net-(IC26C-XOUT)") (class "Default")
      (node (ref "IC26") (pin "31") (pinfunction "XOUT_31") (pintype "output"))
      (node (ref "R7") (pin "2") (pinfunction "2_2") (pintype "passive"))
    )
    (net (code "97") (name "Net-(IC28-+IN)") (class "Default")
      (node (ref "C64") (pin "1") (pinfunction "1_1") (pintype "passive"))
      (node (ref "C7") (pin "1") (pinfunction "1_1") (pintype "passive"))
      (node (ref "IC28") (pin "3") (pinfunction "+IN_3") (pintype "input"))
      (node (ref "R212") (pin "1") (pinfunction "1_1") (pintype "passive"))
      (node (ref "REF1") (pin "1") (pinfunction "C_1") (pintype "passive"))
      (node (ref "VREF") (pin "TP") (pinfunction "P$1_TP") (pintype "bidirectional"))
    )
    (net (code "98") (name "Net-(IC29-A0)") (class "Default")
      (node (ref "IC29") (pin "1") (pinfunction "A0_1") (pintype "bidirectional"))
      (node (ref "R213") (pin "1") (pinfunction "1_1") (pintype "passive"))
      (node (ref "R9") (pin "1") (pinfunction "1_1") (pintype "passive"))
    )
    (net (code "99") (name "Net-(IC40-AAM)") (class "Default")
      (node (ref "C84") (pin "1") (pinfunction "1_1") (pintype "passive"))
      (node (ref "IC40") (pin "1") (pinfunction "AAM_1") (pintype "bidirectional"))
      (node (ref "R36") (pin "1") (pinfunction "1_1") (pintype "passive"))
    )
    (net (code "100") (name "Net-(IC40-BST)") (class "Default")
      (node (ref "IC40") (pin "5") (pinfunction "BST_5") (pintype "bidirectional"))
      (node (ref "R34") (pin "1") (pinfunction "1_1") (pintype "passive"))
    )
    (net (code "101") (name "Net-(IC40-EN)") (class "Default")
      (node (ref "IC40") (pin "6") (pinfunction "EN_6") (pintype "bidirectional"))
      (node (ref "R37") (pin "2") (pinfunction "2_2") (pintype "passive"))
    )
    (net (code "102") (name "Net-(IC40-FB)") (class "Default")
      (node (ref "IC40") (pin "8") (pinfunction "FB_8") (pintype "bidirectional"))
      (node (ref "R22") (pin "1") (pinfunction "1_1") (pintype "passive"))
    )
    (net (code "103") (name "Net-(IC40-SW)") (class "Default")
      (node (ref "C30") (pin "2") (pinfunction "2_2") (pintype "passive"))
      (node (ref "IC40") (pin "3") (pinfunction "SW_3") (pintype "bidirectional"))
      (node (ref "L11") (pin "1") (pinfunction "1_1") (pintype "passive"))
    )
    (net (code "104") (name "Net-(IC40-VCC)") (class "Default")
      (node (ref "C32") (pin "1") (pinfunction "1_1") (pintype "passive"))
      (node (ref "IC40") (pin "7") (pinfunction "VCC_7") (pintype "bidirectional"))
    )
    (net (code "105") (name "Net-(R16-Pad2)") (class "Default")
      (node (ref "R16") (pin "2") (pinfunction "2_2") (pintype "passive"))
      (node (ref "R56") (pin "1") (pinfunction "1_1") (pintype "passive"))
    )
    (net (code "106") (name "Net-(R38-Pad2)") (class "Default")
      (node (ref "R38") (pin "2") (pinfunction "2_2") (pintype "passive"))
      (node (ref "R45") (pin "1") (pinfunction "1_1") (pintype "passive"))
    )
    (net (code "107") (name "Net-(R52-Pad1)") (class "Default")
      (node (ref "R52") (pin "1") (pinfunction "1_1") (pintype "passive"))
      (node (ref "T6") (pin "5") (pinfunction "D_5") (pintype "passive"))
      (node (ref "T6") (pin "6") (pinfunction "D_6") (pintype "passive"))
      (node (ref "T6") (pin "7") (pinfunction "D_7") (pintype "passive"))
      (node (ref "T6") (pin "8") (pinfunction "D_8") (pintype "passive"))
      (node (ref "T6") (pin "9") (pinfunction "D_9") (pintype "passive"))
    )
    (net (code "108") (name "Net-(R60-Pad2)") (class "Default")
      (node (ref "R60") (pin "2") (pinfunction "2_2") (pintype "passive"))
      (node (ref "R68") (pin "1") (pinfunction "1_1") (pintype "passive"))
    )
    (net (code "109") (name "Net-(R66-Pad2)") (class "Default")
      (node (ref "R66") (pin "2") (pinfunction "2_2") (pintype "passive"))
      (node (ref "R67") (pin "1") (pinfunction "1_1") (pintype "passive"))
    )
    (net (code "110") (name "Net-(T7-G)") (class "Default")
      (node (ref "R53") (pin "2") (pinfunction "2_2") (pintype "passive"))
      (node (ref "R54") (pin "1") (pinfunction "1_1") (pintype "passive"))
      (node (ref "T7") (pin "4") (pinfunction "G_4") (pintype "passive"))
      (node (ref "T8") (pin "4") (pinfunction "G_4") (pintype "passive"))
    )
    (net (code "111") (name "Net-(T9-G)") (class "Default")
      (node (ref "R64") (pin "1") (pinfunction "1_1") (pintype "passive"))
      (node (ref "T9") (pin "4") (pinfunction "G_4") (pintype "passive"))
    )
    (net (code "112") (name "Net-(T10-G)") (class "Default")
      (node (ref "R65") (pin "1") (pinfunction "1_1") (pintype "passive"))
      (node (ref "T10") (pin "4") (pinfunction "G_4") (pintype "passive"))
    )
    (net (code "113") (name "Net-(USB9-CC1)") (class "Default")
      (node (ref "R19") (pin "1") (pinfunction "1_1") (pintype "passive"))
      (node (ref "USB9") (pin "A5") (pinfunction "CC1_A5") (pintype "bidirectional"))
    )
    (net (code "114") (name "Net-(USB9-CC2)") (class "Default")
      (node (ref "R18") (pin "1") (pinfunction "1_1") (pintype "passive"))
      (node (ref "USB9") (pin "B5") (pinfunction "CC2_B5") (pintype "bidirectional"))
    )
    (net (code "115") (name "Net-(VREL1-P$1)") (class "Default")
      (node (ref "R53") (pin "1") (pinfunction "1_1") (pintype "passive"))
      (node (ref "T7") (pin "1") (pinfunction "S_1") (pintype "passive"))
      (node (ref "T7") (pin "2") (pinfunction "S_2") (pintype "passive"))
      (node (ref "T7") (pin "3") (pinfunction "S_3") (pintype "passive"))
      (node (ref "T8") (pin "1") (pinfunction "S_1") (pintype "passive"))
      (node (ref "T8") (pin "2") (pinfunction "S_2") (pintype "passive"))
      (node (ref "T8") (pin "3") (pinfunction "S_3") (pintype "passive"))
      (node (ref "VREL1") (pin "TP") (pinfunction "P$1_TP") (pintype "bidirectional"))
    )
    (net (code "116") (name "Net-(VTPS2-P$1)") (class "Default")
      (node (ref "C46") (pin "1") (pinfunction "1_1") (pintype "passive"))
      (node (ref "IC12") (pin "21") (pinfunction "SW2_21") (pintype "power_in"))
      (node (ref "IC12") (pin "25") (pinfunction "SW2_25") (pintype "power_in"))
      (node (ref "L2") (pin "2") (pinfunction "2_2") (pintype "passive"))
      (node (ref "R232") (pin "1") (pinfunction "1_1") (pintype "passive"))
      (node (ref "VTPS2") (pin "TP") (pinfunction "P$1_TP") (pintype "bidirectional"))
    )
    (net (code "117") (name "Net-(X1-2)") (class "Default")
      (node (ref "C62") (pin "1") (pinfunction "1_1") (pintype "passive"))
      (node (ref "R7") (pin "1") (pinfunction "1_1") (pintype "passive"))
      (node (ref "X1") (pin "3") (pinfunction "2_3") (pintype "passive"))
    )
    (net (code "118") (name "OCP1") (class "Default")
      (node (ref "IC26") (pin "45") (pinfunction "GPIO36_45") (pintype "bidirectional"))
      (node (ref "IC4") (pin "2") (pinfunction "IN_2") (pintype "bidirectional"))
      (node (ref "IC8") (pin "4") (pinfunction "~{FAULT}_4") (pintype "bidirectional"))
      (node (ref "R4") (pin "2") (pinfunction "2_2") (pintype "passive"))
    )
    (net (code "119") (name "OCP2") (class "Default")
      (node (ref "IC1") (pin "4") (pinfunction "~{FAULT}_4") (pintype "bidirectional"))
      (node (ref "IC26") (pin "46") (pinfunction "GPIO37_46") (pintype "bidirectional"))
      (node (ref "IC5") (pin "2") (pinfunction "IN_2") (pintype "bidirectional"))
      (node (ref "R13") (pin "2") (pinfunction "2_2") (pintype "passive"))
    )
    (net (code "120") (name "OCP3") (class "Default")
      (node (ref "IC26") (pin "47") (pinfunction "GPIO38_47") (pintype "bidirectional"))
    )
    (net (code "121") (name "OCP4") (class "Default")
      (node (ref "IC26") (pin "48") (pinfunction "GPIO39_48") (pintype "bidirectional"))
    )
    (net (code "122") (name "P1_IS_N") (class "Default")
      (node (ref "C81") (pin "2") (pinfunction "2_2") (pintype "passive"))
      (node (ref "IC12") (pin "13") (pinfunction "ISN_13") (pintype "input"))
      (node (ref "R229") (pin "1") (pinfunction "1_1") (pintype "passive"))
    )
    (net (code "123") (name "P1_IS_P") (class "Default")
      (node (ref "C81") (pin "1") (pinfunction "1_1") (pintype "passive"))
      (node (ref "IC12") (pin "12") (pinfunction "ISP_12") (pintype "input"))
      (node (ref "R228") (pin "1") (pinfunction "1_1") (pintype "passive"))
    )
    (net (code "124") (name "QMI_CS1") (class "Default")
      (node (ref "IC26") (pin "6") (pinfunction "GPIO8_6") (pintype "bidirectional"))
      (node (ref "IC39") (pin "1") (pinfunction "~{CS}_1") (pintype "bidirectional"))
      (node (ref "R278") (pin "1") (pinfunction "1_1") (pintype "passive"))
    )
    (net (code "125") (name "QSPI_SCLK") (class "Default")
      (node (ref "IC26") (pin "71") (pinfunction "QSPI_SCLK_71") (pintype "output"))
      (node (ref "IC27") (pin "6") (pinfunction "CLK_6") (pintype "bidirectional"))
      (node (ref "IC39") (pin "6") (pinfunction "CLK_6") (pintype "bidirectional"))
    )
    (net (code "126") (name "QSPI_SD0") (class "Default")
      (node (ref "IC26") (pin "72") (pinfunction "QSPI_SD0_72") (pintype "bidirectional"))
      (node (ref "IC27") (pin "5") (pinfunction "DI/IO0_5") (pintype "bidirectional"))
      (node (ref "IC39") (pin "5") (pinfunction "DI/IO0_5") (pintype "bidirectional"))
    )
    (net (code "127") (name "QSPI_SD1") (class "Default")
      (node (ref "IC26") (pin "74") (pinfunction "QSPI_SD1_74") (pintype "bidirectional"))
      (node (ref "IC27") (pin "2") (pinfunction "DO/IO1_2") (pintype "bidirectional"))
      (node (ref "IC39") (pin "2") (pinfunction "DO/IO1_2") (pintype "bidirectional"))
    )
    (net (code "128") (name "QSPI_SD2") (class "Default")
      (node (ref "IC26") (pin "73") (pinfunction "QSPI_SD2_73") (pintype "bidirectional"))
      (node (ref "IC27") (pin "3") (pinfunction "~{WP}/IO2_3") (pintype "bidirectional"))
      (node (ref "IC39") (pin "3") (pinfunction "~{WP}/IO2_3") (pintype "bidirectional"))
    )
    (net (code "129") (name "QSPI_SD3") (class "Default")
      (node (ref "IC26") (pin "70") (pinfunction "QSPI_SD3_70") (pintype "bidirectional"))
      (node (ref "IC27") (pin "7") (pinfunction "~{HOLD}/IO3_7") (pintype "bidirectional"))
      (node (ref "IC39") (pin "7") (pinfunction "~{HOLD}/IO3_7") (pintype "bidirectional"))
    )
    (net (code "130") (name "RCT") (class "Default")
      (node (ref "C95") (pin "1") (pinfunction "1_1") (pintype "passive"))
      (node (ref "ETH2") (pin "5") (pinfunction "P5/RCT_5") (pintype "passive"))
      (node (ref "R127") (pin "2") (pinfunction "2_2") (pintype "passive"))
      (node (ref "R128") (pin "2") (pinfunction "2_2") (pintype "passive"))
    )
    (net (code "131") (name "RDC_RD_N") (class "Default")
      (node (ref "C128") (pin "1") (pinfunction "1_1") (pintype "passive"))
      (node (ref "R128") (pin "1") (pinfunction "1_1") (pintype "passive"))
      (node (ref "R133") (pin "2") (pinfunction "2_2") (pintype "passive"))
    )
    (net (code "132") (name "RDC_RD_P") (class "Default")
      (node (ref "C129") (pin "1") (pinfunction "1_1") (pintype "passive"))
      (node (ref "R127") (pin "1") (pinfunction "1_1") (pintype "passive"))
      (node (ref "R134") (pin "2") (pinfunction "2_2") (pintype "passive"))
    )
    (net (code "133") (name "RD_N") (class "Default")
      (node (ref "C128") (pin "2") (pinfunction "2_2") (pintype "passive"))
      (node (ref "ETH2") (pin "6") (pinfunction "RD-_6") (pintype "passive"))
    )
    (net (code "134") (name "RD_P") (class "Default")
      (node (ref "C129") (pin "2") (pinfunction "2_2") (pintype "passive"))
      (node (ref "ETH2") (pin "4") (pinfunction "RD+_4") (pintype "passive"))
    )
    (net (code "135") (name "RUN") (class "Default")
      (node (ref "IC26") (pin "35") (pinfunction "RUN_35") (pintype "input"))
      (node (ref "JTAG") (pin "10") (pinfunction "10_10") (pintype "passive"))
      (node (ref "R24") (pin "2") (pinfunction "2_2") (pintype "passive"))
      (node (ref "SW1") (pin "2") (pinfunction "P$2_2") (pintype "bidirectional"))
    )
    (net (code "136") (name "RX_RD_N") (class "Default")
      (node (ref "IC17") (pin "5") (pinfunction "RXN_5") (pintype "input"))
      (node (ref "R133") (pin "1") (pinfunction "1_1") (pintype "passive"))
    )
    (net (code "137") (name "RX_RD_P") (class "Default")
      (node (ref "IC17") (pin "6") (pinfunction "RXP_6") (pintype "input"))
      (node (ref "R134") (pin "1") (pinfunction "1_1") (pintype "passive"))
    )
    (net (code "138") (name "SHIELD") (class "Default")
      (node (ref "C11") (pin "1") (pinfunction "1_1") (pintype "passive"))
      (node (ref "C131") (pin "1") (pinfunction "1_1") (pintype "passive"))
      (node (ref "C28") (pin "1") (pinfunction "1_1") (pintype "passive"))
      (node (ref "C40") (pin "2") (pinfunction "2_2") (pintype "passive"))
      (node (ref "ETH2") (pin "13") (pinfunction "SHIELD_13") (pintype "passive"))
      (node (ref "ETH2") (pin "14") (pinfunction "SHIELD_14") (pintype "passive"))
      (node (ref "H1") (pin "B3,3") (pinfunction "MOUNT_B3,3") (pintype "passive"))
      (node (ref "H2") (pin "B3,3") (pinfunction "MOUNT_B3,3") (pintype "passive"))
      (node (ref "H3") (pin "B3,3") (pinfunction "MOUNT_B3,3") (pintype "passive"))
      (node (ref "H4") (pin "B3,3") (pinfunction "MOUNT_B3,3") (pintype "passive"))
      (node (ref "PORT1") (pin "S1") (pinfunction "SHIELD1_S1") (pintype "passive"))
      (node (ref "PORT1") (pin "S2") (pinfunction "SHIELD1_S2") (pintype "passive"))
      (node (ref "PORT1") (pin "S3") (pinfunction "SHIELD1_S3") (pintype "passive"))
      (node (ref "PORT1") (pin "S4") (pinfunction "SHIELD1_S4") (pintype "passive"))
      (node (ref "R10") (pin "1") (pinfunction "1_1") (pintype "passive"))
      (node (ref "R141") (pin "2") (pinfunction "2_2") (pintype "passive"))
      (node (ref "R2") (pin "2") (pinfunction "2_2") (pintype "passive"))
      (node (ref "R50") (pin "2") (pinfunction "2_2") (pintype "passive"))
      (node (ref "USB9") (pin "SHLD1") (pinfunction "SHILED_SHLD1") (pintype "power_in"))
      (node (ref "USB9") (pin "SHLD2") (pinfunction "SHILED_SHLD2") (pintype "power_in"))
      (node (ref "USB9") (pin "SHLD3") (pinfunction "SHILED_SHLD3") (pintype "power_in"))
      (node (ref "USB9") (pin "SHLD4") (pinfunction "SHILED_SHLD4") (pintype "power_in"))
      (node (ref "USBA_1-2") (pin "S1") (pinfunction "SHIELD_S1") (pintype "passive"))
      (node (ref "USBA_1-2") (pin "S2") (pinfunction "SHIELD_S2") (pintype "passive"))
      (node (ref "USBA_1-2") (pin "S3") (pinfunction "SHIELD_S3") (pintype "passive"))
      (node (ref "USBA_1-2") (pin "S4") (pinfunction "SHIELD_S4") (pintype "passive"))
    )
    (net (code "139") (name "SWCLK") (class "Default")
      (node (ref "IC26") (pin "33") (pinfunction "SWCLK_33") (pintype "output"))
      (node (ref "JTAG") (pin "4") (pinfunction "4_4") (pintype "passive"))
    )
    (net (code "140") (name "SWDIO") (class "Default")
      (node (ref "IC26") (pin "34") (pinfunction "SWDIO_34") (pintype "bidirectional"))
      (node (ref "JTAG") (pin "2") (pinfunction "2_2") (pintype "passive"))
    )
    (net (code "141") (name "TCA0_I2C_SCL") (class "Default")
      (node (ref "IC38") (pin "2") (pinfunction "SC0_2") (pintype "bidirectional"))
      (node (ref "IC9") (pin "4") (pinfunction "SCL_4") (pintype "input"))
      (node (ref "R215") (pin "C1") (pinfunction "3_C1") (pintype "passive"))
      (node (ref "TCC0") (pin "TP") (pinfunction "P$1_TP") (pintype "bidirectional"))
    )
    (net (code "142") (name "TCA0_I2C_SDA") (class "Default")
      (node (ref "IC38") (pin "1") (pinfunction "SD0_1") (pintype "bidirectional"))
      (node (ref "IC9") (pin "5") (pinfunction "SDA_5") (pintype "bidirectional"))
      (node (ref "R215") (pin "D1") (pinfunction "4_D1") (pintype "passive"))
      (node (ref "TCD0") (pin "TP") (pinfunction "P$1_TP") (pintype "bidirectional"))
    )
    (net (code "143") (name "TCA1_I2C_SCL") (class "Default")
      (node (ref "IC38") (pin "4") (pinfunction "SC1_4") (pintype "bidirectional"))
      (node (ref "R215") (pin "A1") (pinfunction "1_A1") (pintype "passive"))
      (node (ref "TCC1") (pin "TP") (pinfunction "P$1_TP") (pintype "bidirectional"))
    )
    (net (code "144") (name "TCA1_I2C_SDA") (class "Default")
      (node (ref "IC38") (pin "3") (pinfunction "SD1_3") (pintype "bidirectional"))
      (node (ref "R215") (pin "B1") (pinfunction "2_B1") (pintype "passive"))
      (node (ref "TCD1") (pin "TP") (pinfunction "P$1_TP") (pintype "bidirectional"))
    )
    (net (code "145") (name "TCA2_I2C_SCL") (class "Default")
      (node (ref "IC38") (pin "6") (pinfunction "SC2_6") (pintype "bidirectional"))
      (node (ref "R216") (pin "C1") (pinfunction "3_C1") (pintype "passive"))
      (node (ref "TCC2") (pin "TP") (pinfunction "P$1_TP") (pintype "bidirectional"))
    )
    (net (code "146") (name "TCA2_I2C_SDA") (class "Default")
      (node (ref "IC38") (pin "5") (pinfunction "SD2_5") (pintype "bidirectional"))
      (node (ref "R216") (pin "D1") (pinfunction "4_D1") (pintype "passive"))
      (node (ref "TCD2") (pin "TP") (pinfunction "P$1_TP") (pintype "bidirectional"))
    )
    (net (code "147") (name "TCA3_I2C_SCL") (class "Default")
      (node (ref "IC38") (pin "8") (pinfunction "SC3_8") (pintype "bidirectional"))
      (node (ref "R216") (pin "A1") (pinfunction "1_A1") (pintype "passive"))
      (node (ref "TCC3") (pin "TP") (pinfunction "P$1_TP") (pintype "bidirectional"))
    )
    (net (code "148") (name "TCA3_I2C_SDA") (class "Default")
      (node (ref "IC38") (pin "7") (pinfunction "SD3_7") (pintype "bidirectional"))
      (node (ref "R216") (pin "B1") (pinfunction "2_B1") (pintype "passive"))
      (node (ref "TCD3") (pin "TP") (pinfunction "P$1_TP") (pintype "bidirectional"))
    )
    (net (code "149") (name "TCA4_I2C_SCL") (class "Default")
      (node (ref "IC13") (pin "5") (pinfunction "SCL_5") (pintype "bidirectional"))
      (node (ref "IC38") (pin "11") (pinfunction "SC4_11") (pintype "bidirectional"))
      (node (ref "R217") (pin "C1") (pinfunction "3_C1") (pintype "passive"))
      (node (ref "TCC4") (pin "TP") (pinfunction "P$1_TP") (pintype "bidirectional"))
    )
    (net (code "150") (name "TCA4_I2C_SDA") (class "Default")
      (node (ref "IC13") (pin "6") (pinfunction "SDA_6") (pintype "bidirectional"))
      (node (ref "IC38") (pin "10") (pinfunction "SD4_10") (pintype "bidirectional"))
      (node (ref "R217") (pin "D1") (pinfunction "4_D1") (pintype "passive"))
      (node (ref "TCD4") (pin "TP") (pinfunction "P$1_TP") (pintype "bidirectional"))
    )
    (net (code "151") (name "TCA5_I2C_SCL") (class "Default")
      (node (ref "IC38") (pin "13") (pinfunction "SC5_13") (pintype "bidirectional"))
      (node (ref "R217") (pin "A1") (pinfunction "1_A1") (pintype "passive"))
      (node (ref "TCC5") (pin "TP") (pinfunction "P$1_TP") (pintype "bidirectional"))
    )
    (net (code "152") (name "TCA5_I2C_SDA") (class "Default")
      (node (ref "IC38") (pin "12") (pinfunction "SD5_12") (pintype "bidirectional"))
      (node (ref "R217") (pin "B1") (pinfunction "2_B1") (pintype "passive"))
      (node (ref "TCD5") (pin "TP") (pinfunction "P$1_TP") (pintype "bidirectional"))
    )
    (net (code "153") (name "TCA6_I2C_SCL") (class "Default")
      (node (ref "IC38") (pin "15") (pinfunction "SC6_15") (pintype "bidirectional"))
      (node (ref "R35") (pin "C1") (pinfunction "3_C1") (pintype "passive"))
      (node (ref "TCC6") (pin "TP") (pinfunction "P$1_TP") (pintype "bidirectional"))
    )
    (net (code "154") (name "TCA6_I2C_SDA") (class "Default")
      (node (ref "IC38") (pin "14") (pinfunction "SD6_14") (pintype "bidirectional"))
      (node (ref "R35") (pin "D1") (pinfunction "4_D1") (pintype "passive"))
      (node (ref "TCD6") (pin "TP") (pinfunction "P$1_TP") (pintype "bidirectional"))
    )
    (net (code "155") (name "TCA7_I2C_SCL") (class "Default")
      (node (ref "IC38") (pin "17") (pinfunction "SC7_17") (pintype "bidirectional"))
      (node (ref "R35") (pin "A1") (pinfunction "1_A1") (pintype "passive"))
      (node (ref "TCC7") (pin "TP") (pinfunction "P$1_TP") (pintype "bidirectional"))
    )
    (net (code "156") (name "TCA7_I2C_SDA") (class "Default")
      (node (ref "IC38") (pin "16") (pinfunction "SD7_16") (pintype "bidirectional"))
      (node (ref "R35") (pin "B1") (pinfunction "2_B1") (pintype "passive"))
      (node (ref "TCD7") (pin "TP") (pinfunction "P$1_TP") (pintype "bidirectional"))
    )
    (net (code "157") (name "TCT") (class "Default")
      (node (ref "C130") (pin "1") (pinfunction "1_1") (pintype "passive"))
      (node (ref "ETH2") (pin "2") (pinfunction "P4/TCT_2") (pintype "passive"))
      (node (ref "R140") (pin "2") (pinfunction "2_2") (pintype "passive"))
    )
    (net (code "158") (name "TDR_N") (class "Default")
      (node (ref "R125") (pin "1") (pinfunction "1_1") (pintype "passive"))
      (node (ref "R130") (pin "2") (pinfunction "2_2") (pintype "passive"))
      (node (ref "R131") (pin "2") (pinfunction "2_2") (pintype "passive"))
    )
    (net (code "159") (name "TDR_P") (class "Default")
      (node (ref "R126") (pin "1") (pinfunction "1_1") (pintype "passive"))
      (node (ref "R129") (pin "2") (pinfunction "2_2") (pintype "passive"))
      (node (ref "R132") (pin "2") (pinfunction "2_2") (pintype "passive"))
    )
    (net (code "160") (name "TD_N") (class "Default")
      (node (ref "ETH2") (pin "3") (pinfunction "TD-_3") (pintype "passive"))
      (node (ref "R125") (pin "2") (pinfunction "2_2") (pintype "passive"))
    )
    (net (code "161") (name "TD_P") (class "Default")
      (node (ref "ETH2") (pin "1") (pinfunction "TD+_1") (pintype "passive"))
      (node (ref "R126") (pin "2") (pinfunction "2_2") (pintype "passive"))
    )
    (net (code "162") (name "TX_TD_N") (class "Default")
      (node (ref "IC17") (pin "1") (pinfunction "TXN_1") (pintype "output"))
      (node (ref "R131") (pin "1") (pinfunction "1_1") (pintype "passive"))
    )
    (net (code "163") (name "TX_TD_P") (class "Default")
      (node (ref "IC17") (pin "2") (pinfunction "TXP_2") (pintype "output"))
      (node (ref "R132") (pin "1") (pinfunction "1_1") (pintype "passive"))
    )
    (net (code "164") (name "UART0_RX") (class "Default")
      (node (ref "IC26") (pin "78") (pinfunction "GPIO1_78") (pintype "bidirectional"))
      (node (ref "JTAG") (pin "6") (pinfunction "6_6") (pintype "passive"))
    )
    (net (code "165") (name "UART0_TX") (class "Default")
      (node (ref "IC26") (pin "77") (pinfunction "GPIO0_77") (pintype "bidirectional"))
      (node (ref "JTAG") (pin "8") (pinfunction "8_8") (pintype "passive"))
    )
    (net (code "166") (name "USBA1_EN") (class "Default")
      (node (ref "IC26") (pin "40") (pinfunction "GPIO32_40") (pintype "bidirectional"))
      (node (ref "IC8") (pin "3") (pinfunction "EN_3") (pintype "bidirectional"))
      (node (ref "R1") (pin "1") (pinfunction "1_1") (pintype "passive"))
    )
    (net (code "167") (name "USBA2_EN") (class "Default")
      (node (ref "IC1") (pin "3") (pinfunction "EN_3") (pintype "bidirectional"))
      (node (ref "IC26") (pin "42") (pinfunction "GPIO33_42") (pintype "bidirectional"))
      (node (ref "R3") (pin "1") (pinfunction "1_1") (pintype "passive"))
    )
    (net (code "168") (name "USBA3_EN") (class "Default")
      (node (ref "IC26") (pin "43") (pinfunction "GPIO34_43") (pintype "bidirectional"))
    )
    (net (code "169") (name "USBA4_EN") (class "Default")
      (node (ref "IC26") (pin "44") (pinfunction "GPIO35_44") (pintype "bidirectional"))
    )
    (net (code "170") (name "USB_BOOT") (class "Default")
      (node (ref "JTAG") (pin "7") (pinfunction "7_7") (pintype "passive"))
      (node (ref "R6") (pin "1") (pinfunction "1_1") (pintype "passive"))
      (node (ref "SW2") (pin "1") (pinfunction "P$1_1") (pintype "bidirectional"))
    )
    (net (code "171") (name "USB_RP_DP_N") (class "Default")
      (node (ref "ESD1") (pin "3") (pinfunction "C2_3") (pintype "bidirectional"))
      (node (ref "R25") (pin "1") (pinfunction "1_1") (pintype "passive"))
      (node (ref "USB9") (pin "A7") (pinfunction "D-_A7") (pintype "bidirectional"))
      (node (ref "USB9") (pin "B7") (pinfunction "D-_B7") (pintype "bidirectional"))
    )
    (net (code "172") (name "USB_RP_DP_P") (class "Default")
      (node (ref "ESD1") (pin "2") (pinfunction "C1_2") (pintype "bidirectional"))
      (node (ref "R26") (pin "1") (pinfunction "1_1") (pintype "passive"))
      (node (ref "USB9") (pin "A6") (pinfunction "D+_A6") (pintype "bidirectional"))
      (node (ref "USB9") (pin "B6") (pinfunction "D+_B6") (pintype "bidirectional"))
    )
    (net (code "173") (name "VBUS") (class "Default")
      (node (ref "C66") (pin "1") (pinfunction "1_1") (pintype "passive"))
      (node (ref "C67") (pin "1") (pinfunction "1_1") (pintype "passive"))
      (node (ref "C68") (pin "1") (pinfunction "1_1") (pintype "passive"))
      (node (ref "ESD1") (pin "4") (pinfunction "C3_4") (pintype "bidirectional"))
      (node (ref "R20") (pin "1") (pinfunction "1_1") (pintype "passive"))
      (node (ref "R30") (pin "1") (pinfunction "1_1") (pintype "passive"))
      (node (ref "R31") (pin "1") (pinfunction "1_1") (pintype "passive"))
      (node (ref "TP2") (pin "TP") (pinfunction "P$1_TP") (pintype "bidirectional"))
      (node (ref "USB9") (pin "VBUS1") (pinfunction "VBUS_VBUS1") (pintype "power_in"))
      (node (ref "USB9") (pin "VBUS2") (pinfunction "VBUS_VBUS2") (pintype "power_in"))
    )
    (net (code "174") (name "VBUS_USBA1") (class "Default")
      (node (ref "C3") (pin "1") (pinfunction "1_1") (pintype "passive"))
      (node (ref "C4") (pin "1") (pinfunction "1_1") (pintype "passive"))
      (node (ref "C5") (pin "1") (pinfunction "+_1") (pintype "passive"))
      (node (ref "IC8") (pin "6") (pinfunction "OUT_6") (pintype "bidirectional"))
      (node (ref "USBA_1-2") (pin "1") (pinfunction "VBUS_1") (pintype "passive"))
      (node (ref "USBA_VB1") (pin "TP") (pinfunction "P$1_TP") (pintype "bidirectional"))
    )
    (net (code "175") (name "VBUS_USBA2") (class "Default")
      (node (ref "C77") (pin "1") (pinfunction "1_1") (pintype "passive"))
      (node (ref "C78") (pin "1") (pinfunction "1_1") (pintype "passive"))
      (node (ref "C79") (pin "1") (pinfunction "+_1") (pintype "passive"))
      (node (ref "IC1") (pin "6") (pinfunction "OUT_6") (pintype "bidirectional"))
      (node (ref "USBA_1-2") (pin "5") (pinfunction "VBUS_5") (pintype "passive"))
      (node (ref "USBA_VB2") (pin "TP") (pinfunction "P$1_TP") (pintype "bidirectional"))
    )
    (net (code "176") (name "VOUT_PORT1") (class "Default")
      (node (ref "C51") (pin "2") (pinfunction "2_2") (pintype "passive"))
      (node (ref "C52") (pin "2") (pinfunction "2_2") (pintype "passive"))
      (node (ref "C53") (pin "2") (pinfunction "2_2") (pintype "passive"))
      (node (ref "C54") (pin "2") (pinfunction "2_2") (pintype "passive"))
      (node (ref "C82") (pin "2") (pinfunction "2_2") (pintype "passive"))
      (node (ref "C83") (pin "1") (pinfunction "+_1") (pintype "passive"))
      (node (ref "IC12") (pin "11") (pinfunction "VOUT_11") (pintype "power_in"))
      (node (ref "IC12") (pin "26") (pinfunction "VOUT_26") (pintype "power_in"))
      (node (ref "R228") (pin "2") (pinfunction "2_2") (pintype "passive"))
      (node (ref "R63") (pin "2") (pinfunction "2_2") (pintype "passive"))
      (node (ref "VOP1") (pin "TP") (pinfunction "P$1_TP") (pintype "bidirectional"))
    )
    (net (code "177") (name "VSRC1") (class "Default")
      (node (ref "C39") (pin "1") (pinfunction "1_1") (pintype "passive"))
      (node (ref "IC9") (pin "1") (pinfunction "VDD_1") (pintype "power_in"))
      (node (ref "R229") (pin "2") (pinfunction "2_2") (pintype "passive"))
      (node (ref "R5") (pin "1") (pinfunction "1_1") (pintype "passive"))
      (node (ref "R55") (pin "1") (pinfunction "1_1") (pintype "passive"))
      (node (ref "R63") (pin "1") (pinfunction "1_1") (pintype "passive"))
      (node (ref "T6") (pin "1") (pinfunction "S_1") (pintype "passive"))
      (node (ref "T6") (pin "2") (pinfunction "S_2") (pintype "passive"))
      (node (ref "T6") (pin "3") (pinfunction "S_3") (pintype "passive"))
      (node (ref "T7") (pin "5") (pinfunction "D_5") (pintype "passive"))
      (node (ref "T7") (pin "6") (pinfunction "D_6") (pintype "passive"))
      (node (ref "T7") (pin "7") (pinfunction "D_7") (pintype "passive"))
      (node (ref "T7") (pin "8") (pinfunction "D_8") (pintype "passive"))
      (node (ref "T7") (pin "9") (pinfunction "D_9") (pintype "passive"))
      (node (ref "VSRC1") (pin "TP") (pinfunction "P$1_TP") (pintype "bidirectional"))
    )
    (net (code "178") (name "VUSB") (class "Default")
      (node (ref "R30") (pin "2") (pinfunction "2_2") (pintype "passive"))
    )
    (net (code "179") (name "W5500_MISO") (class "Default")
      (node (ref "IC17") (pin "34") (pinfunction "MISO_34") (pintype "output"))
      (node (ref "IC26") (pin "16") (pinfunction "GPIO16_16") (pintype "bidirectional"))
    )
    (net (code "180") (name "W5500_MOSI") (class "Default")
      (node (ref "IC17") (pin "35") (pinfunction "MOSI_35") (pintype "input"))
      (node (ref "IC26") (pin "19") (pinfunction "GPIO19_19") (pintype "bidirectional"))
    )
    (net (code "181") (name "W5500_SCK") (class "Default")
      (node (ref "IC17") (pin "33") (pinfunction "SCLK_33") (pintype "input"))
      (node (ref "IC26") (pin "18") (pinfunction "GPIO18_18") (pintype "bidirectional"))
    )
    (net (code "182") (name "unconnected-(DISP-Pad13)") (class "Default")
      (node (ref "DISP") (pin "13") (pinfunction "13_13") (pintype "bidirectional"))
    )
    (net (code "183") (name "unconnected-(DISP-Pad14)") (class "Default")
      (node (ref "DISP") (pin "14") (pinfunction "14_14") (pintype "bidirectional"))
    )
    (net (code "184") (name "unconnected-(DISP-Pad15)") (class "Default")
      (node (ref "DISP") (pin "15") (pinfunction "15_15") (pintype "bidirectional"))
    )
    (net (code "185") (name "unconnected-(DISP-Pad16)") (class "Default")
      (node (ref "DISP") (pin "16") (pinfunction "16_16") (pintype "bidirectional"))
    )
    (net (code "186") (name "unconnected-(DISP-Pad17)") (class "Default")
      (node (ref "DISP") (pin "17") (pinfunction "17_17") (pintype "bidirectional"))
    )
    (net (code "187") (name "unconnected-(DISP-Pad18)") (class "Default")
      (node (ref "DISP") (pin "18") (pinfunction "18_18") (pintype "bidirectional"))
    )
    (net (code "188") (name "unconnected-(DISP-Pad19)") (class "Default")
      (node (ref "DISP") (pin "19") (pinfunction "19_19") (pintype "bidirectional"))
    )
    (net (code "189") (name "unconnected-(IC12-CC_N-Pad6)") (class "Default")
      (node (ref "IC12") (pin "6") (pinfunction "CC_N_6") (pintype "output"))
    )
    (net (code "190") (name "unconnected-(IC12-PG-Pad5)") (class "Default")
      (node (ref "IC12") (pin "5") (pinfunction "PG_5") (pintype "output"))
    )
    (net (code "191") (name "unconnected-(IC17-DNC-Pad7)") (class "Default")
      (node (ref "IC17") (pin "7") (pinfunction "DNC_7") (pintype "bidirectional"))
    )
    (net (code "192") (name "unconnected-(IC17-RSVD1-Pad23)") (class "Default")
      (node (ref "IC17") (pin "23") (pinfunction "RSVD1_23") (pintype "input"))
    )
    (net (code "193") (name "unconnected-(IC17-RSVD2-Pad38)") (class "Default")
      (node (ref "IC17") (pin "38") (pinfunction "RSVD2_38") (pintype "input"))
    )
    (net (code "194") (name "unconnected-(IC17-RSVD3-Pad39)") (class "Default")
      (node (ref "IC17") (pin "39") (pinfunction "RSVD3_39") (pintype "input"))
    )
    (net (code "195") (name "unconnected-(IC17-RSVD4-Pad40)") (class "Default")
      (node (ref "IC17") (pin "40") (pinfunction "RSVD4_40") (pintype "input"))
    )
    (net (code "196") (name "unconnected-(IC17-RSVD5-Pad41)") (class "Default")
      (node (ref "IC17") (pin "41") (pinfunction "RSVD5_41") (pintype "input"))
    )
    (net (code "197") (name "unconnected-(IC17-RSVD6-Pad42)") (class "Default")
      (node (ref "IC17") (pin "42") (pinfunction "RSVD6_42") (pintype "input"))
    )
    (net (code "198") (name "unconnected-(IC17-VBG-Pad18)") (class "Default")
      (node (ref "IC17") (pin "18") (pinfunction "VBG_18") (pintype "output"))
    )
    (net (code "199") (name "unconnected-(IC26A-GPIO2-Pad79)") (class "Default")
      (node (ref "IC26") (pin "79") (pinfunction "GPIO2_79") (pintype "bidirectional"))
    )
    (net (code "200") (name "unconnected-(IC26A-GPIO9-Pad7)") (class "Default")
      (node (ref "IC26") (pin "7") (pinfunction "GPIO9_7") (pintype "bidirectional"))
    )
    (net (code "201") (name "unconnected-(IC26A-GPIO10-Pad8)") (class "Default")
      (node (ref "IC26") (pin "8") (pinfunction "GPIO10_8") (pintype "bidirectional"))
    )
    (net (code "202") (name "unconnected-(IC26A-GPIO11-Pad9)") (class "Default")
      (node (ref "IC26") (pin "9") (pinfunction "GPIO11_9") (pintype "bidirectional"))
    )
    (net (code "203") (name "unconnected-(IC26B-GPIO45_ADC5-Pad56)") (class "Default")
      (node (ref "IC26") (pin "56") (pinfunction "GPIO45_ADC5_56") (pintype "bidirectional"))
    )
    (net (code "204") (name "unconnected-(IC26B-GPIO46_ADC6-Pad57)") (class "Default")
      (node (ref "IC26") (pin "57") (pinfunction "GPIO46_ADC6_57") (pintype "bidirectional"))
    )
    (net (code "205") (name "unconnected-(IC26B-GPIO47_ADC7-Pad58)") (class "Default")
      (node (ref "IC26") (pin "58") (pinfunction "GPIO47_ADC7_58") (pintype "bidirectional"))
    )
    (net (code "206") (name "unconnected-(USB9-SBU1-PadA8)") (class "Default")
      (node (ref "USB9") (pin "A8") (pinfunction "SBU1_A8") (pintype "bidirectional"))
    )
    (net (code "207") (name "unconnected-(USB9-SBU2-PadB8)") (class "Default")
      (node (ref "USB9") (pin "B8") (pinfunction "SBU2_B8") (pintype "bidirectional"))
    )
    (net (code "208") (name "unconnected-(USBA_1-2A-D+-Pad3)") (class "Default")
      (node (ref "USBA_1-2") (pin "3") (pinfunction "D+_3") (pintype "passive"))
    )
    (net (code "209") (name "unconnected-(USBA_1-2A-D--Pad2)") (class "Default")
      (node (ref "USBA_1-2") (pin "2") (pinfunction "D-_2") (pintype "passive"))
    )
    (net (code "210") (name "unconnected-(USBA_1-2B-D+-Pad7)") (class "Default")
      (node (ref "USBA_1-2") (pin "7") (pinfunction "D+_7") (pintype "passive"))
    )
    (net (code "211") (name "unconnected-(USBA_1-2B-D--Pad6)") (class "Default")
      (node (ref "USBA_1-2") (pin "6") (pinfunction "D-_6") (pintype "passive"))
    )
    (net (code "212") (name "~{ACT}") (class "Default")
      (node (ref "IC17") (pin "27") (pinfunction "ACTLED_27") (pintype "output"))
      (node (ref "R138") (pin "1") (pinfunction "1_1") (pintype "passive"))
    )
    (net (code "213") (name "~{DUP}") (class "Default")
      (node (ref "IC17") (pin "26") (pinfunction "DUPLED_26") (pintype "output"))
      (node (ref "IC26") (pin "22") (pinfunction "GPIO22_22") (pintype "bidirectional"))
      (node (ref "R227") (pin "1") (pinfunction "1_1") (pintype "passive"))
    )
    (net (code "214") (name "~{LINK}") (class "Default")
      (node (ref "IC17") (pin "25") (pinfunction "LINKLED_25") (pintype "output"))
      (node (ref "R139") (pin "1") (pinfunction "1_1") (pintype "passive"))
    )
    (net (code "215") (name "~{QSPI_SS}") (class "Default")
      (node (ref "IC26") (pin "75") (pinfunction "QSPI_SS_75") (pintype "output"))
      (node (ref "IC27") (pin "1") (pinfunction "~{CS}_1") (pintype "bidirectional"))
      (node (ref "R209") (pin "1") (pinfunction "1_1") (pintype "passive"))
      (node (ref "R6") (pin "2") (pinfunction "2_2") (pintype "passive"))
    )
    (net (code "216") (name "~{SPD}") (class "Default")
      (node (ref "IC17") (pin "24") (pinfunction "SPDLED_24") (pintype "output"))
      (node (ref "IC26") (pin "23") (pinfunction "GPIO23_23") (pintype "bidirectional"))
      (node (ref "R226") (pin "1") (pinfunction "1_1") (pintype "passive"))
    )
    (net (code "217") (name "~{TCA_RST}") (class "Default")
      (node (ref "IC26") (pin "80") (pinfunction "GPIO3_80") (pintype "bidirectional"))
      (node (ref "IC38") (pin "24") (pinfunction "RESET_24") (pintype "input"))
    )
    (net (code "218") (name "~{W5500_CS}") (class "Default")
      (node (ref "IC17") (pin "32") (pinfunction "~{SCSN}_32") (pintype "input"))
      (node (ref "IC26") (pin "17") (pinfunction "GPIO17_17") (pintype "bidirectional"))
    )
    (net (code "219") (name "~{W5500_INT}") (class "Default")
      (node (ref "IC17") (pin "36") (pinfunction "~{INTN}_36") (pintype "input"))
      (node (ref "IC26") (pin "21") (pinfunction "GPIO21_21") (pintype "bidirectional"))
    )
    (net (code "220") (name "~{W5500_RST}") (class "Default")
      (node (ref "IC17") (pin "37") (pinfunction "~{RSTN}_37") (pintype "input"))
      (node (ref "IC26") (pin "20") (pinfunction "GPIO20_20") (pintype "bidirectional"))
      (node (ref "R135") (pin "2") (pinfunction "2_2") (pintype "passive"))
    )
  )
)
